# dsp_ice_rev1.net
KiCad netlist of a schematic drawn in EAGLE
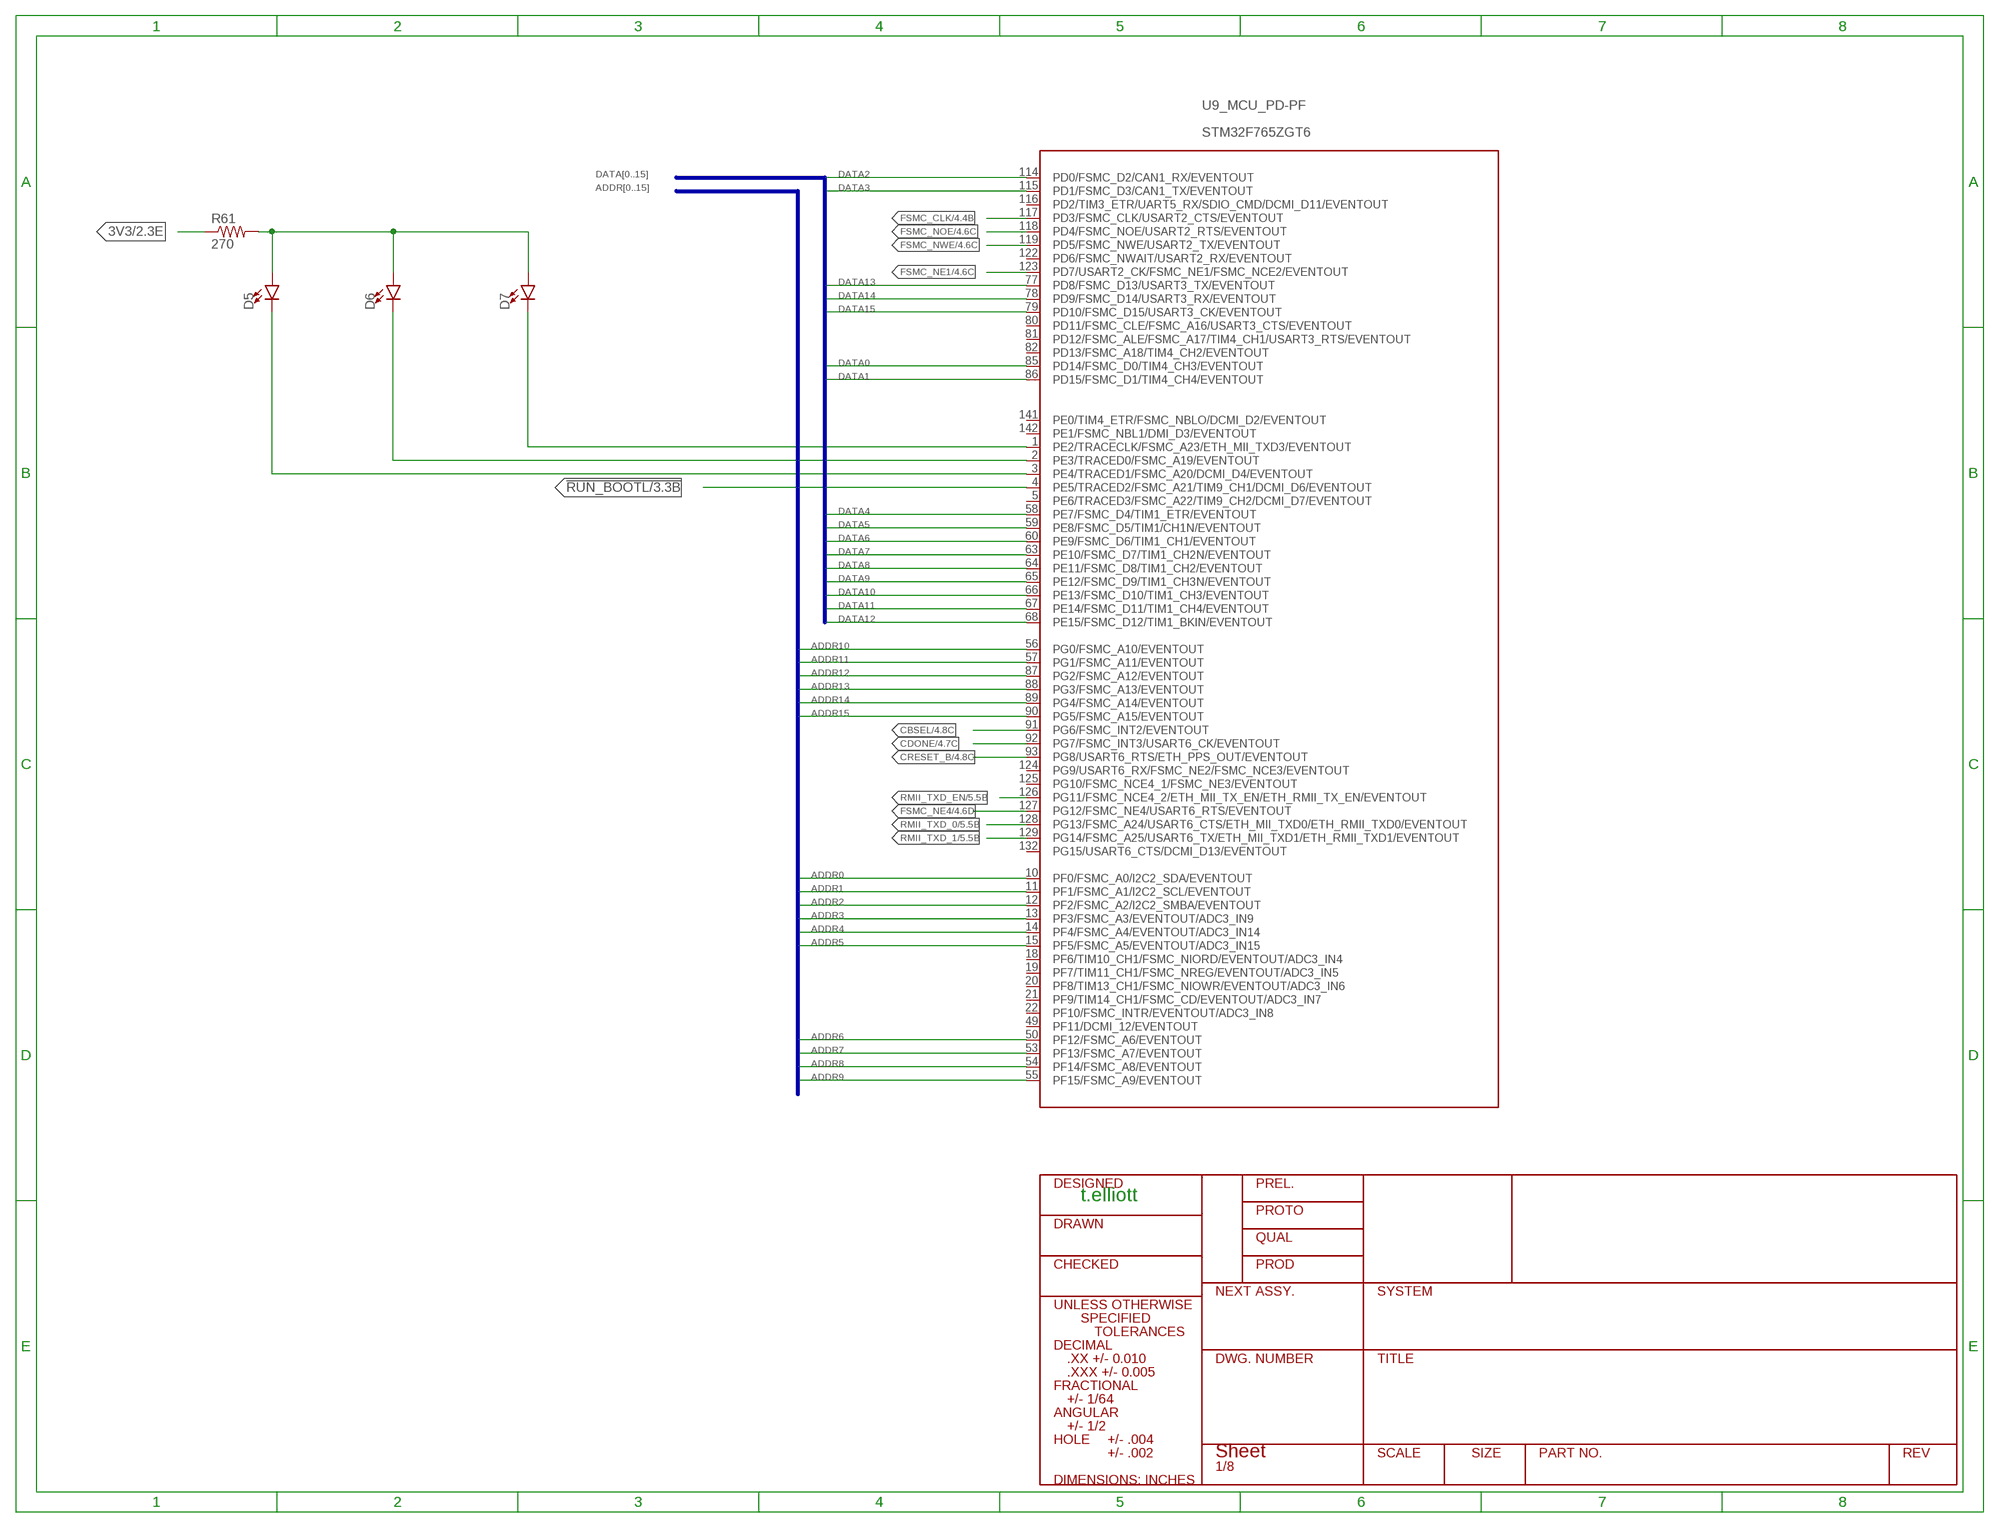
[diagram p0: schematic, sheet 1]
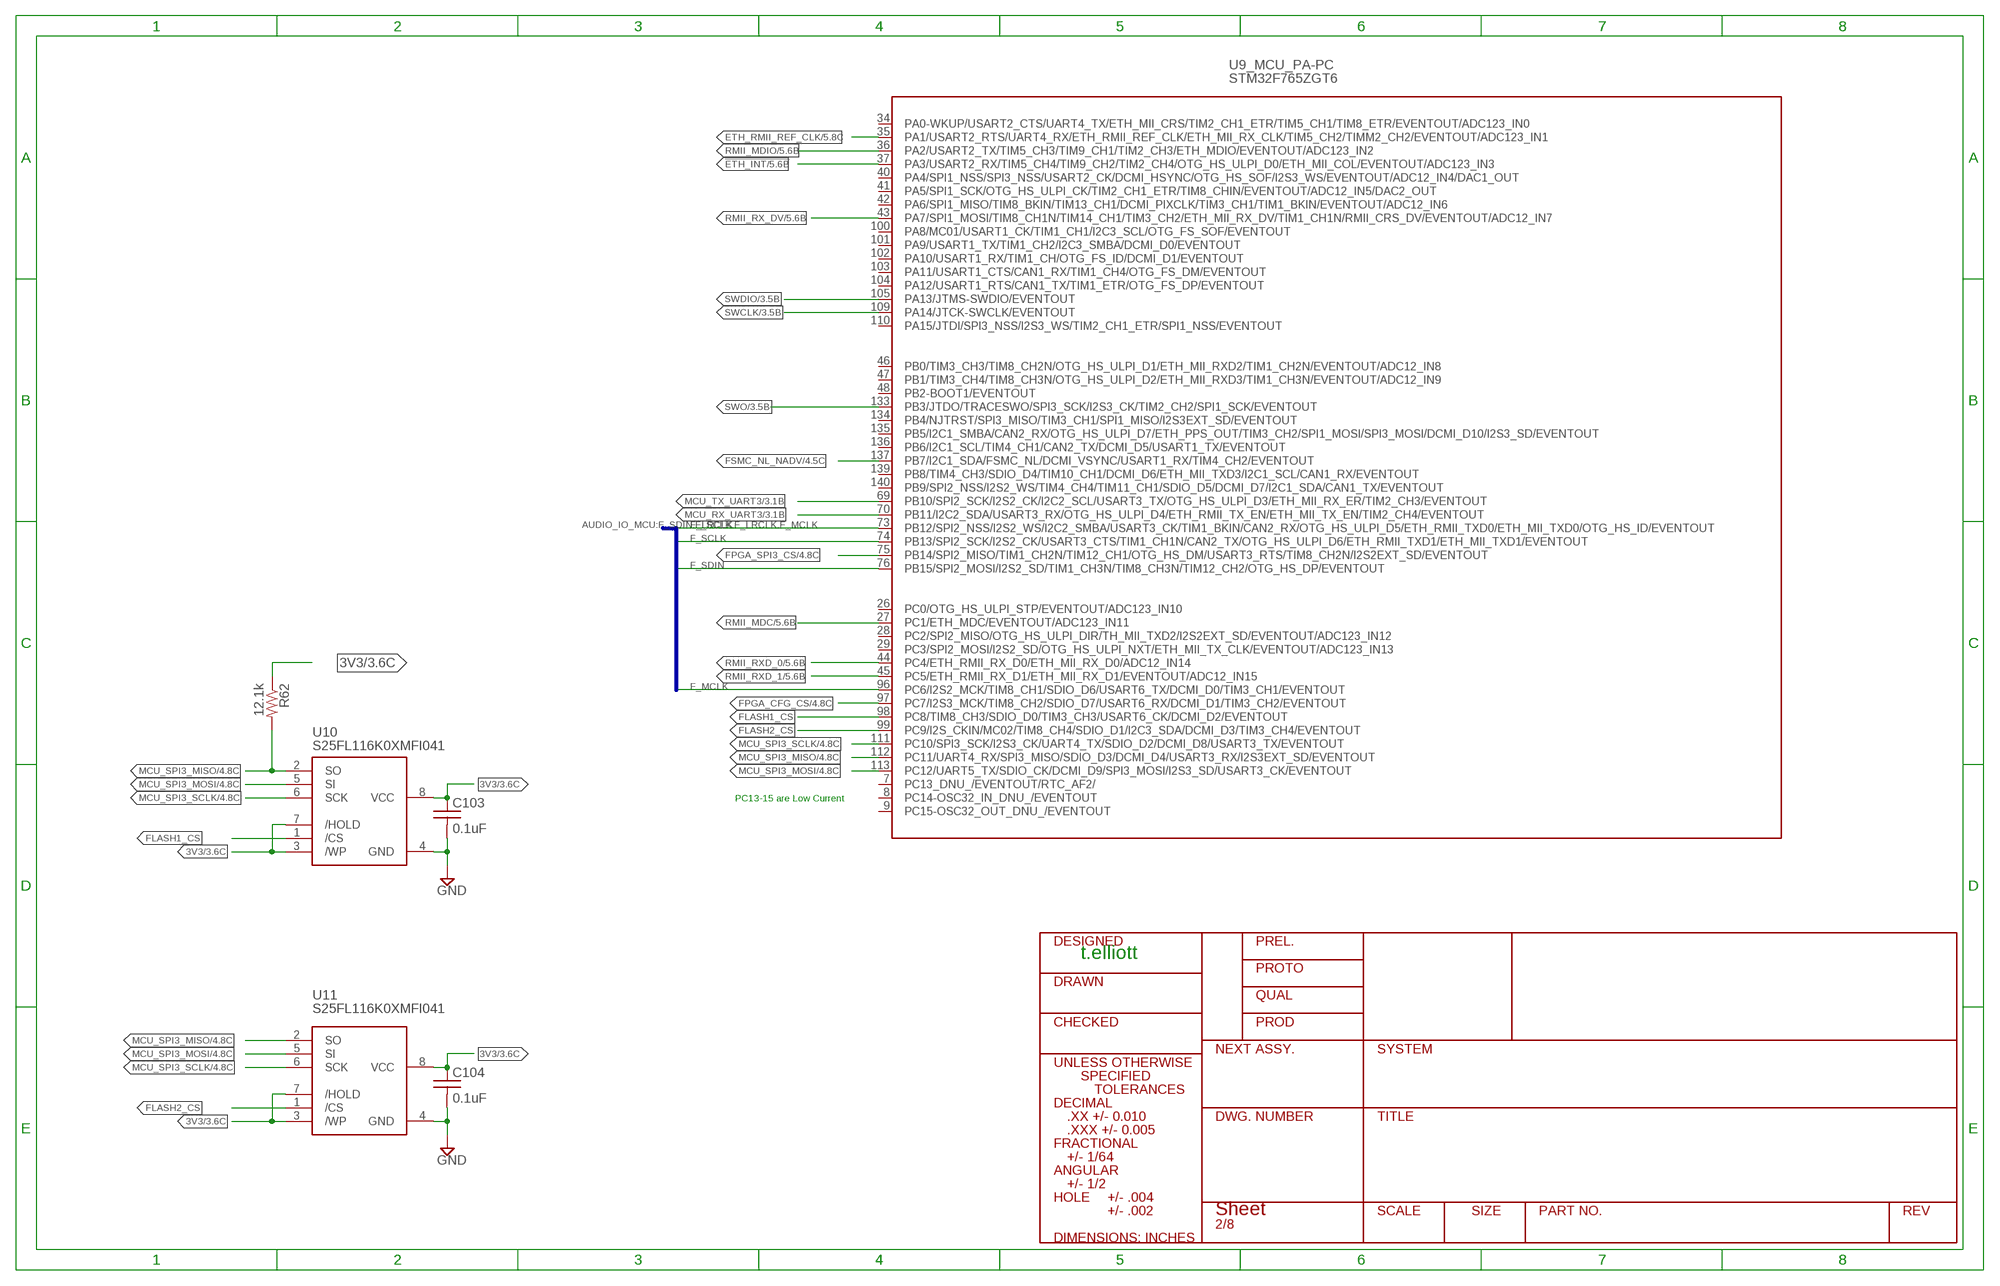
[diagram p1: schematic, sheet 2]
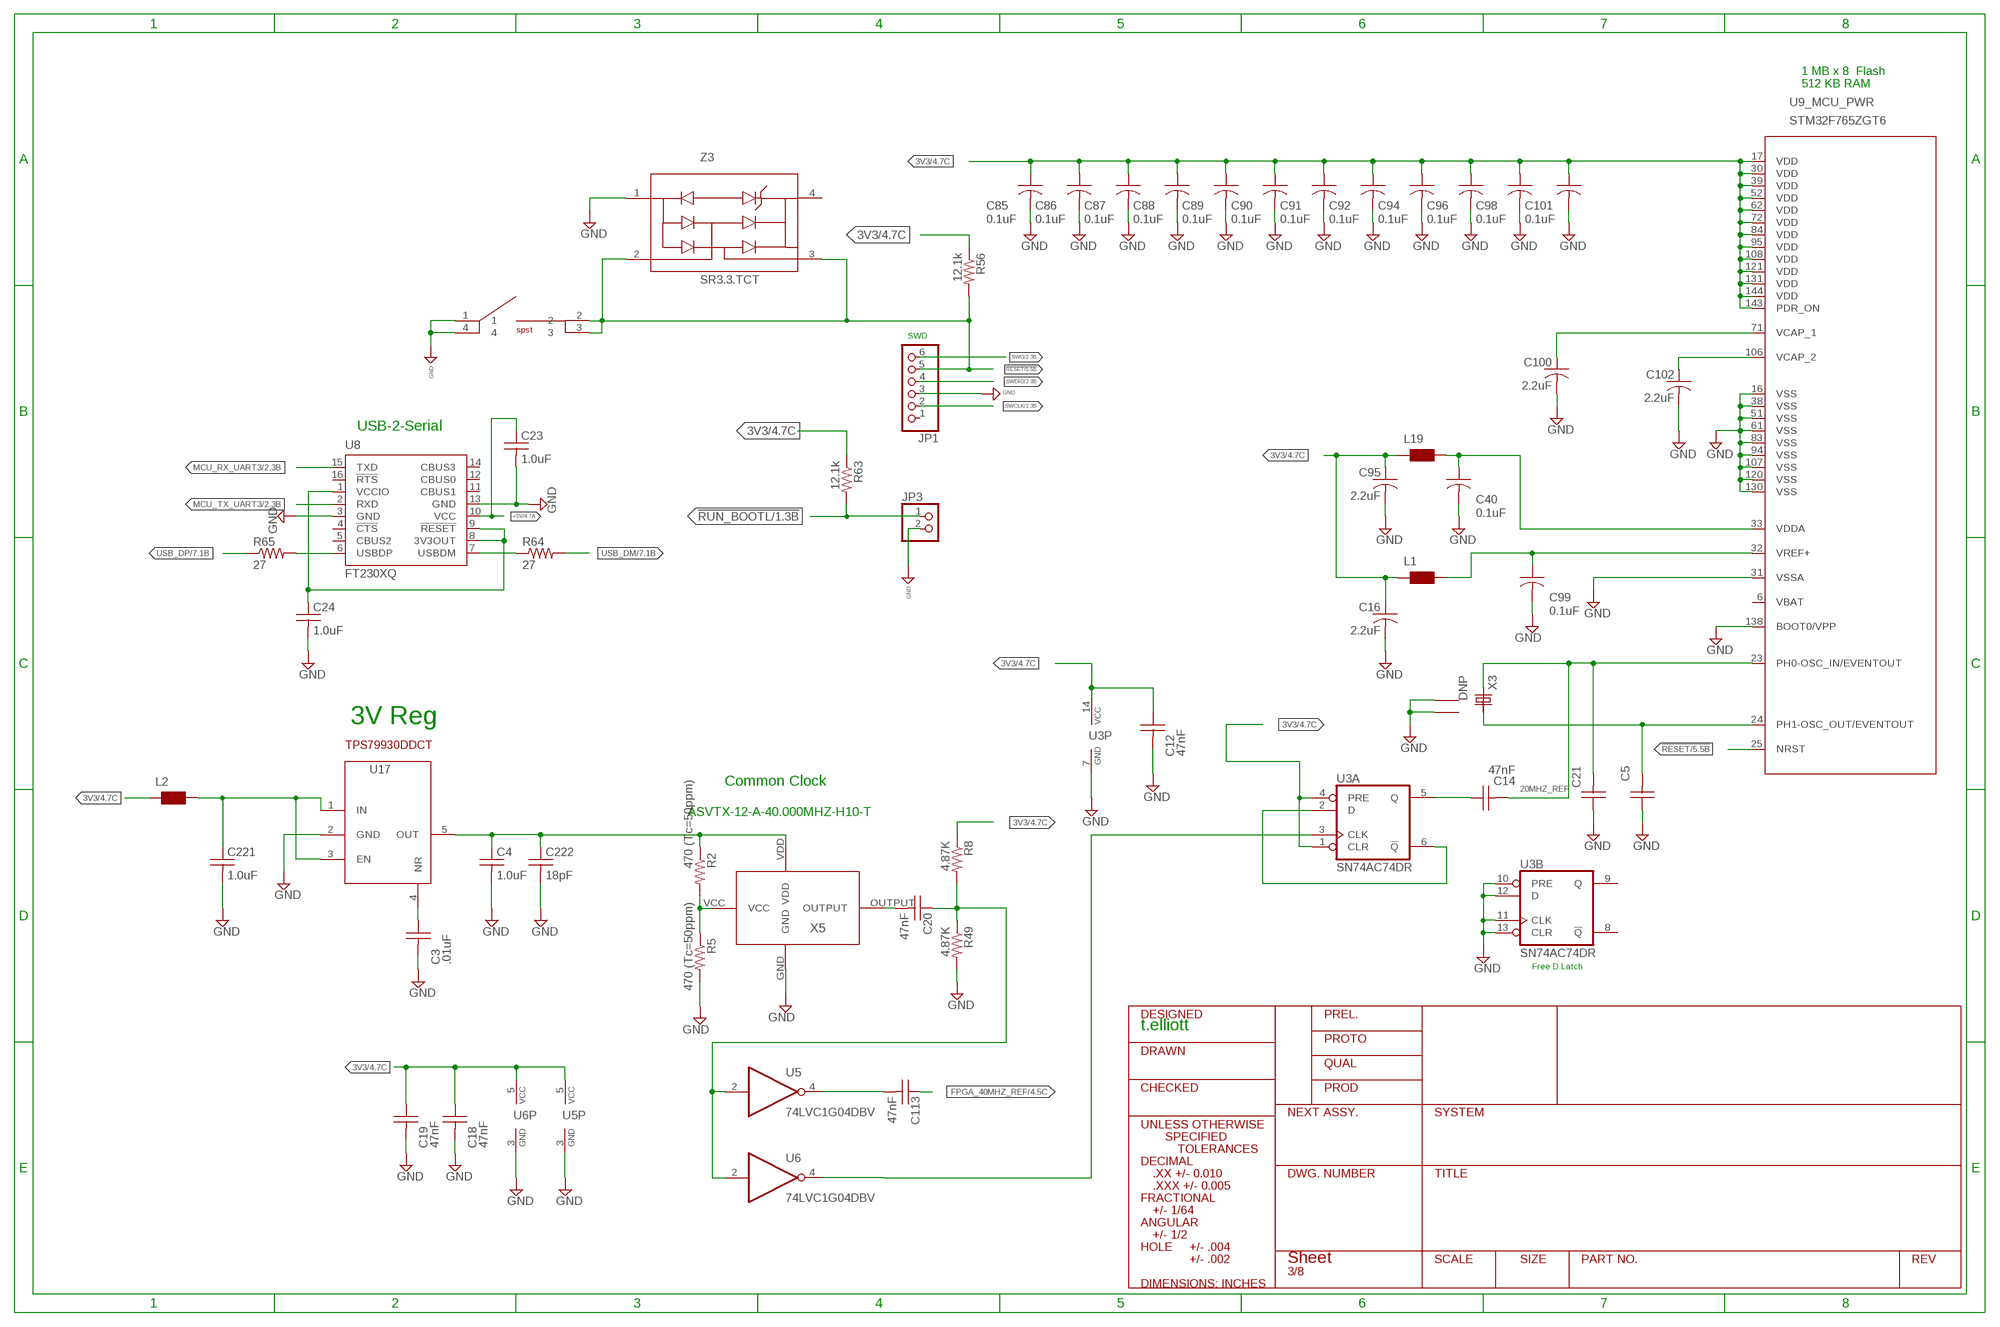
[diagram p2: schematic, sheet 3]
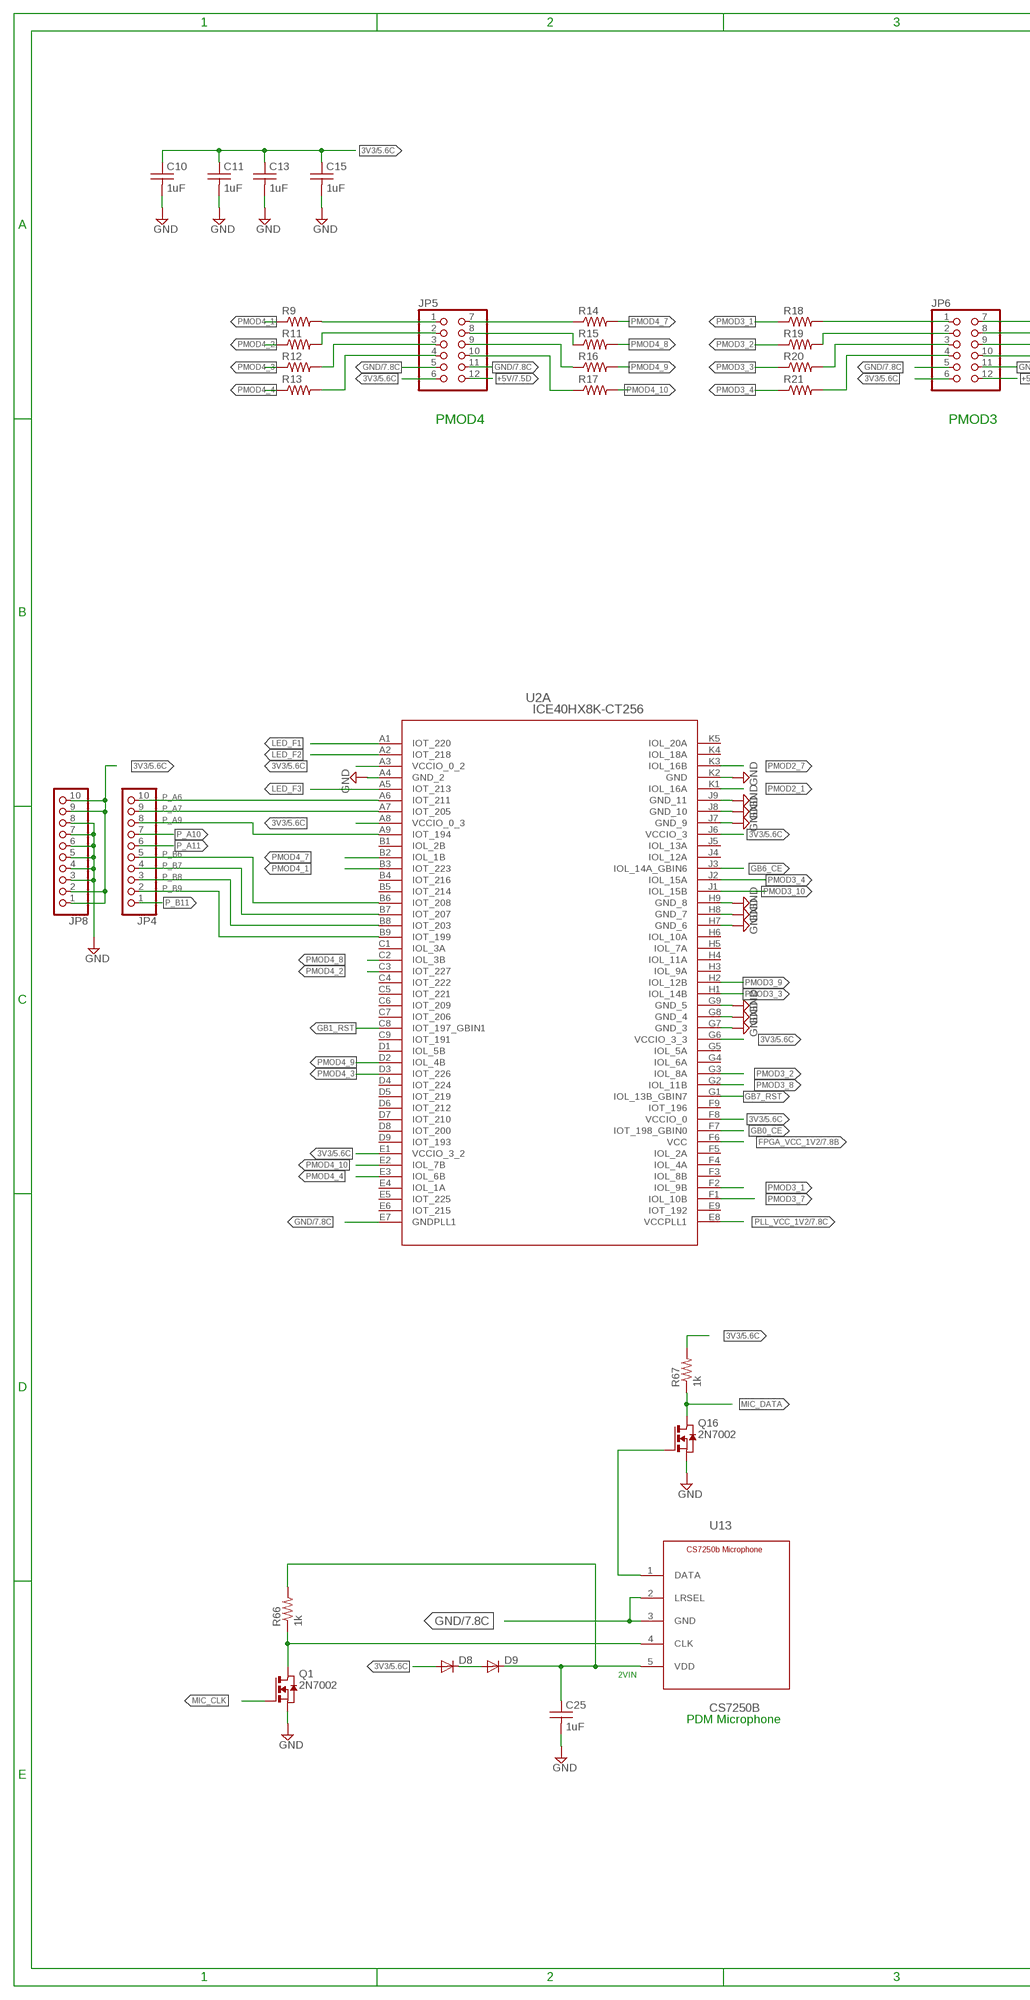
[diagram p3: schematic, sheet 4, part 1 of 2]
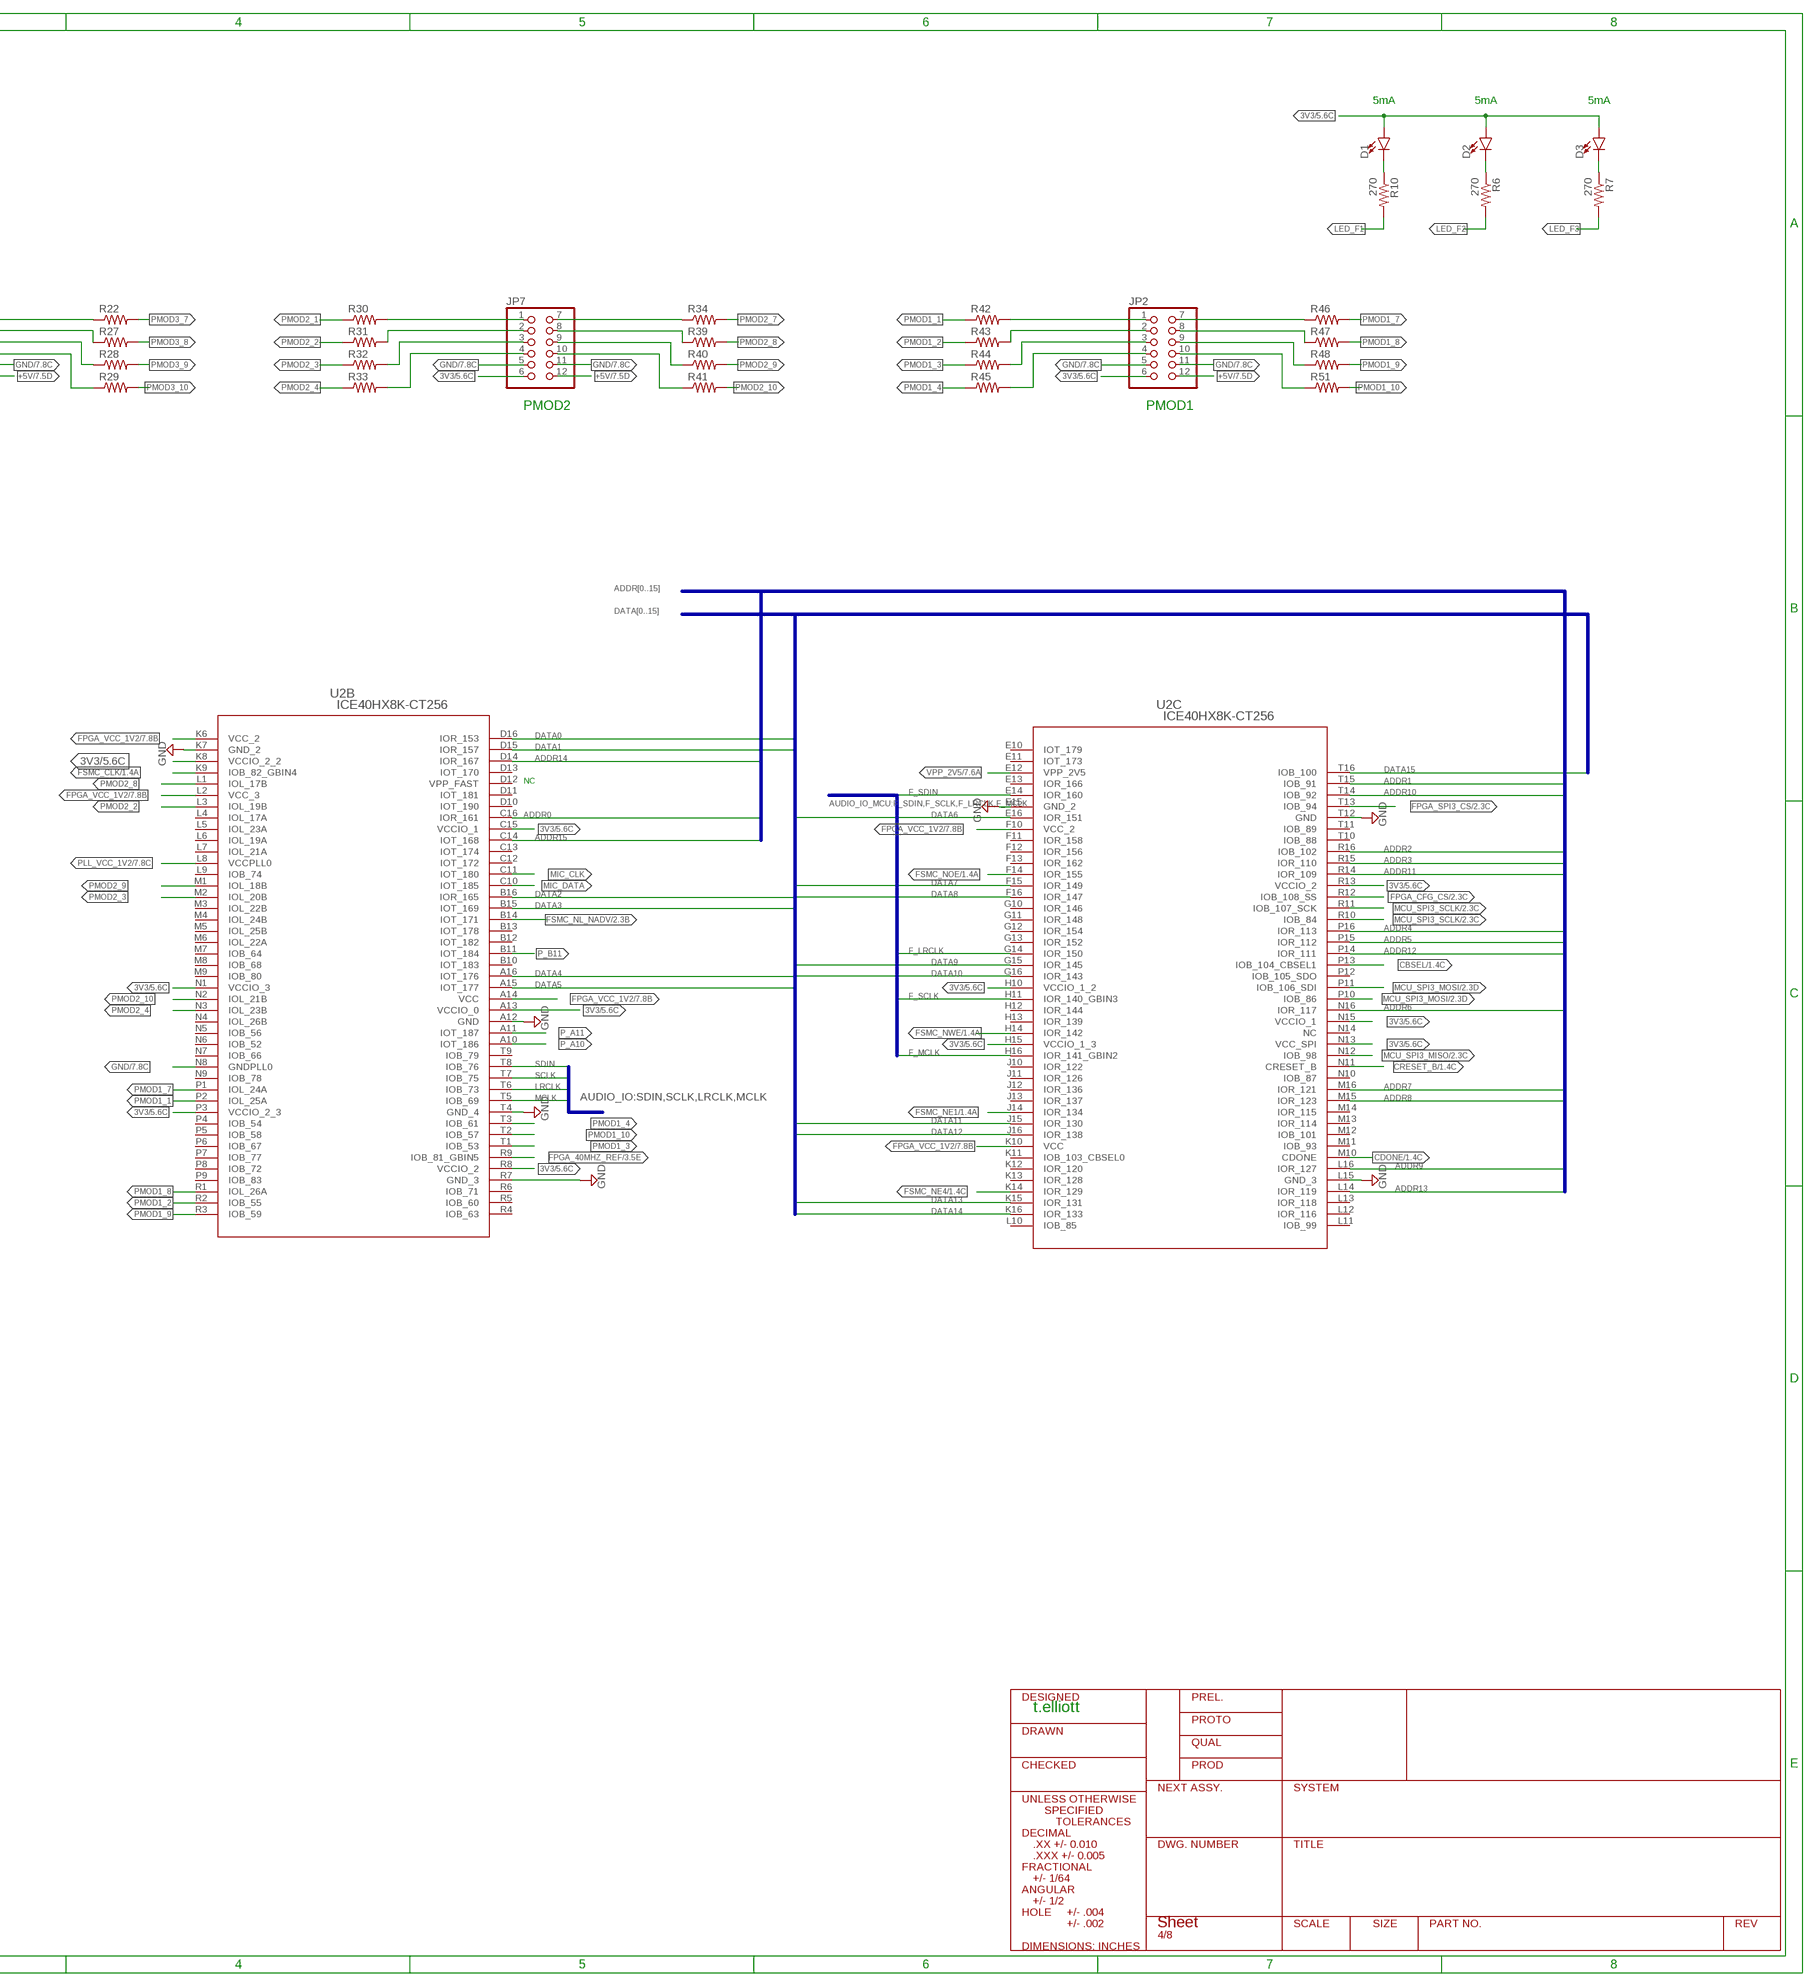
[diagram p4: schematic, sheet 4, part 2 of 2]
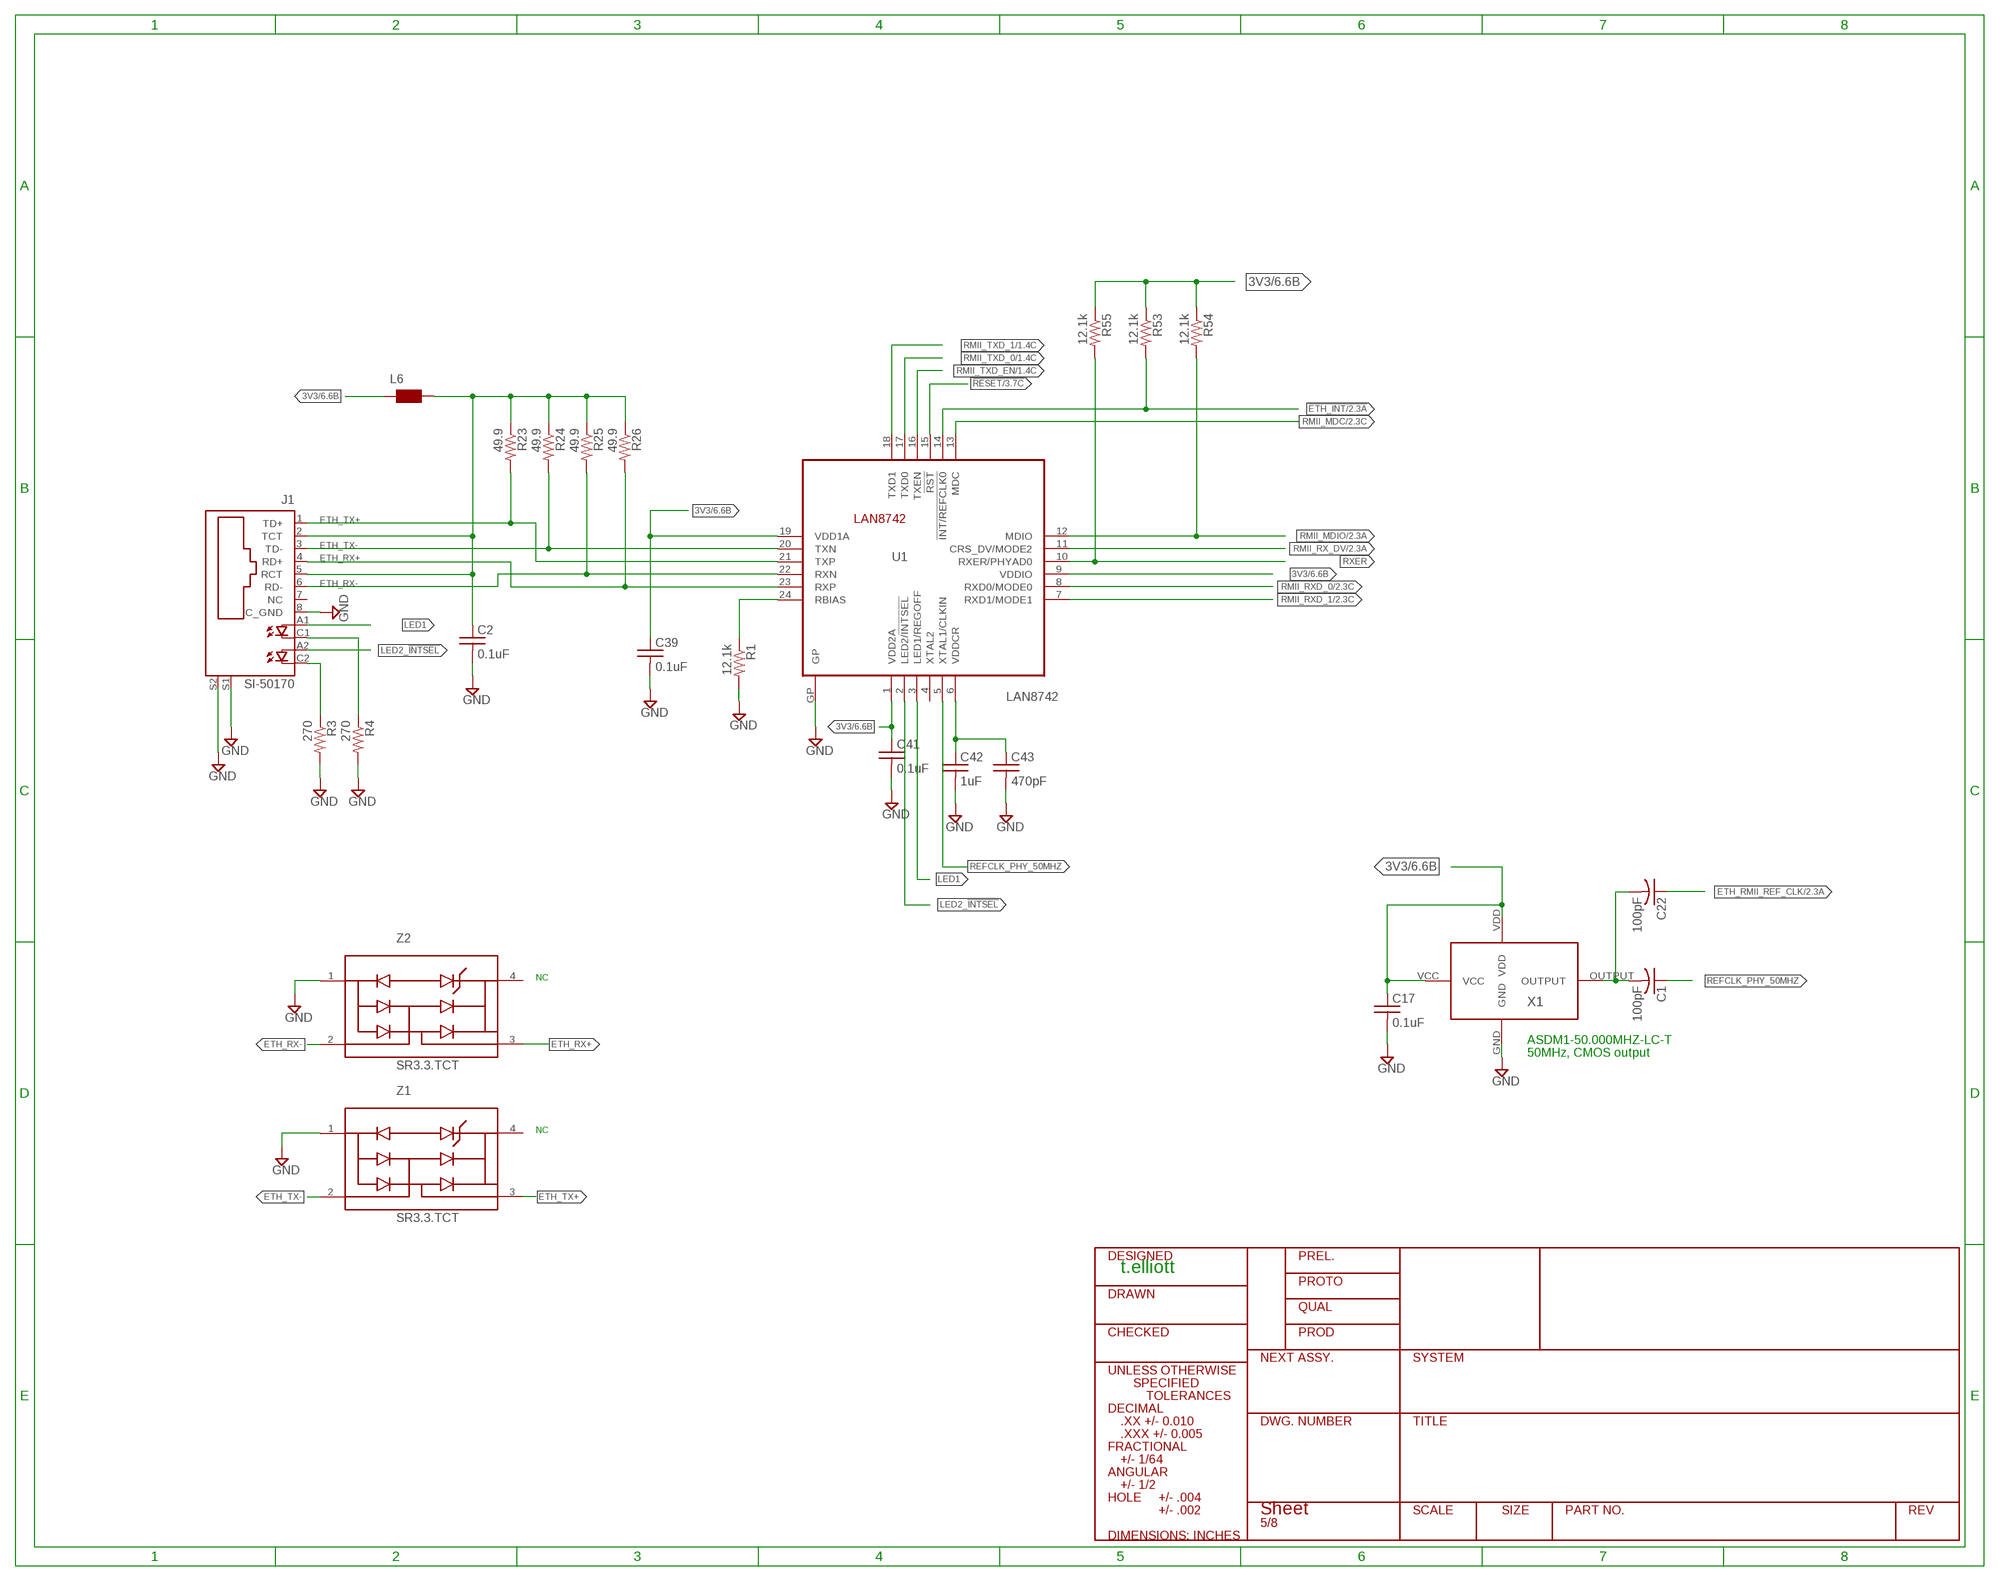
[diagram p5: schematic, sheet 5]
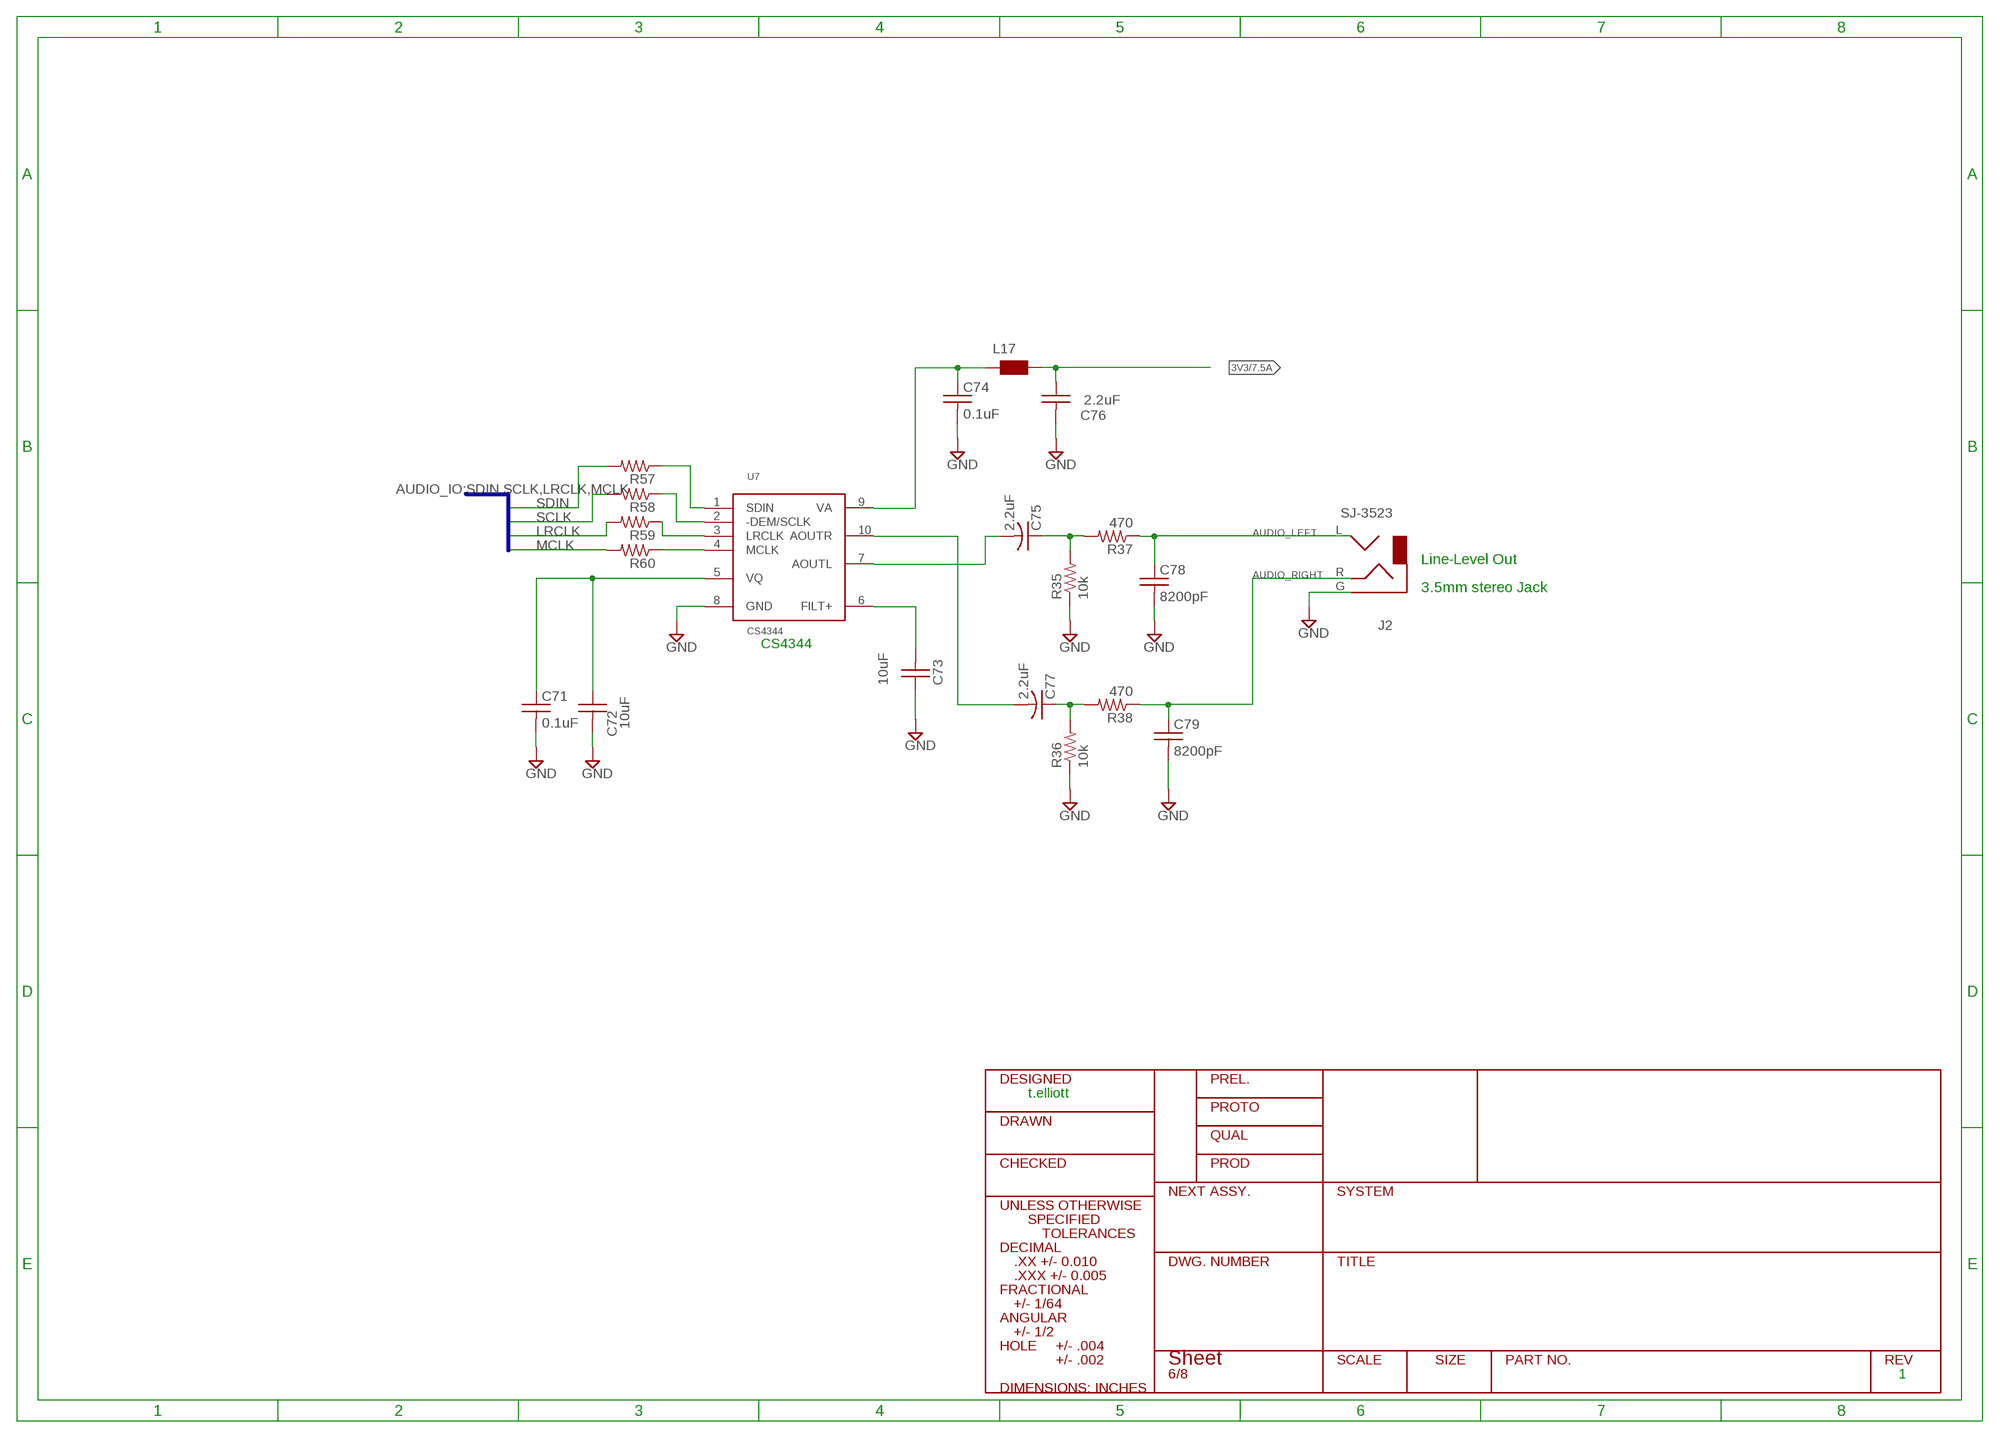
[diagram p6: schematic, sheet 6]
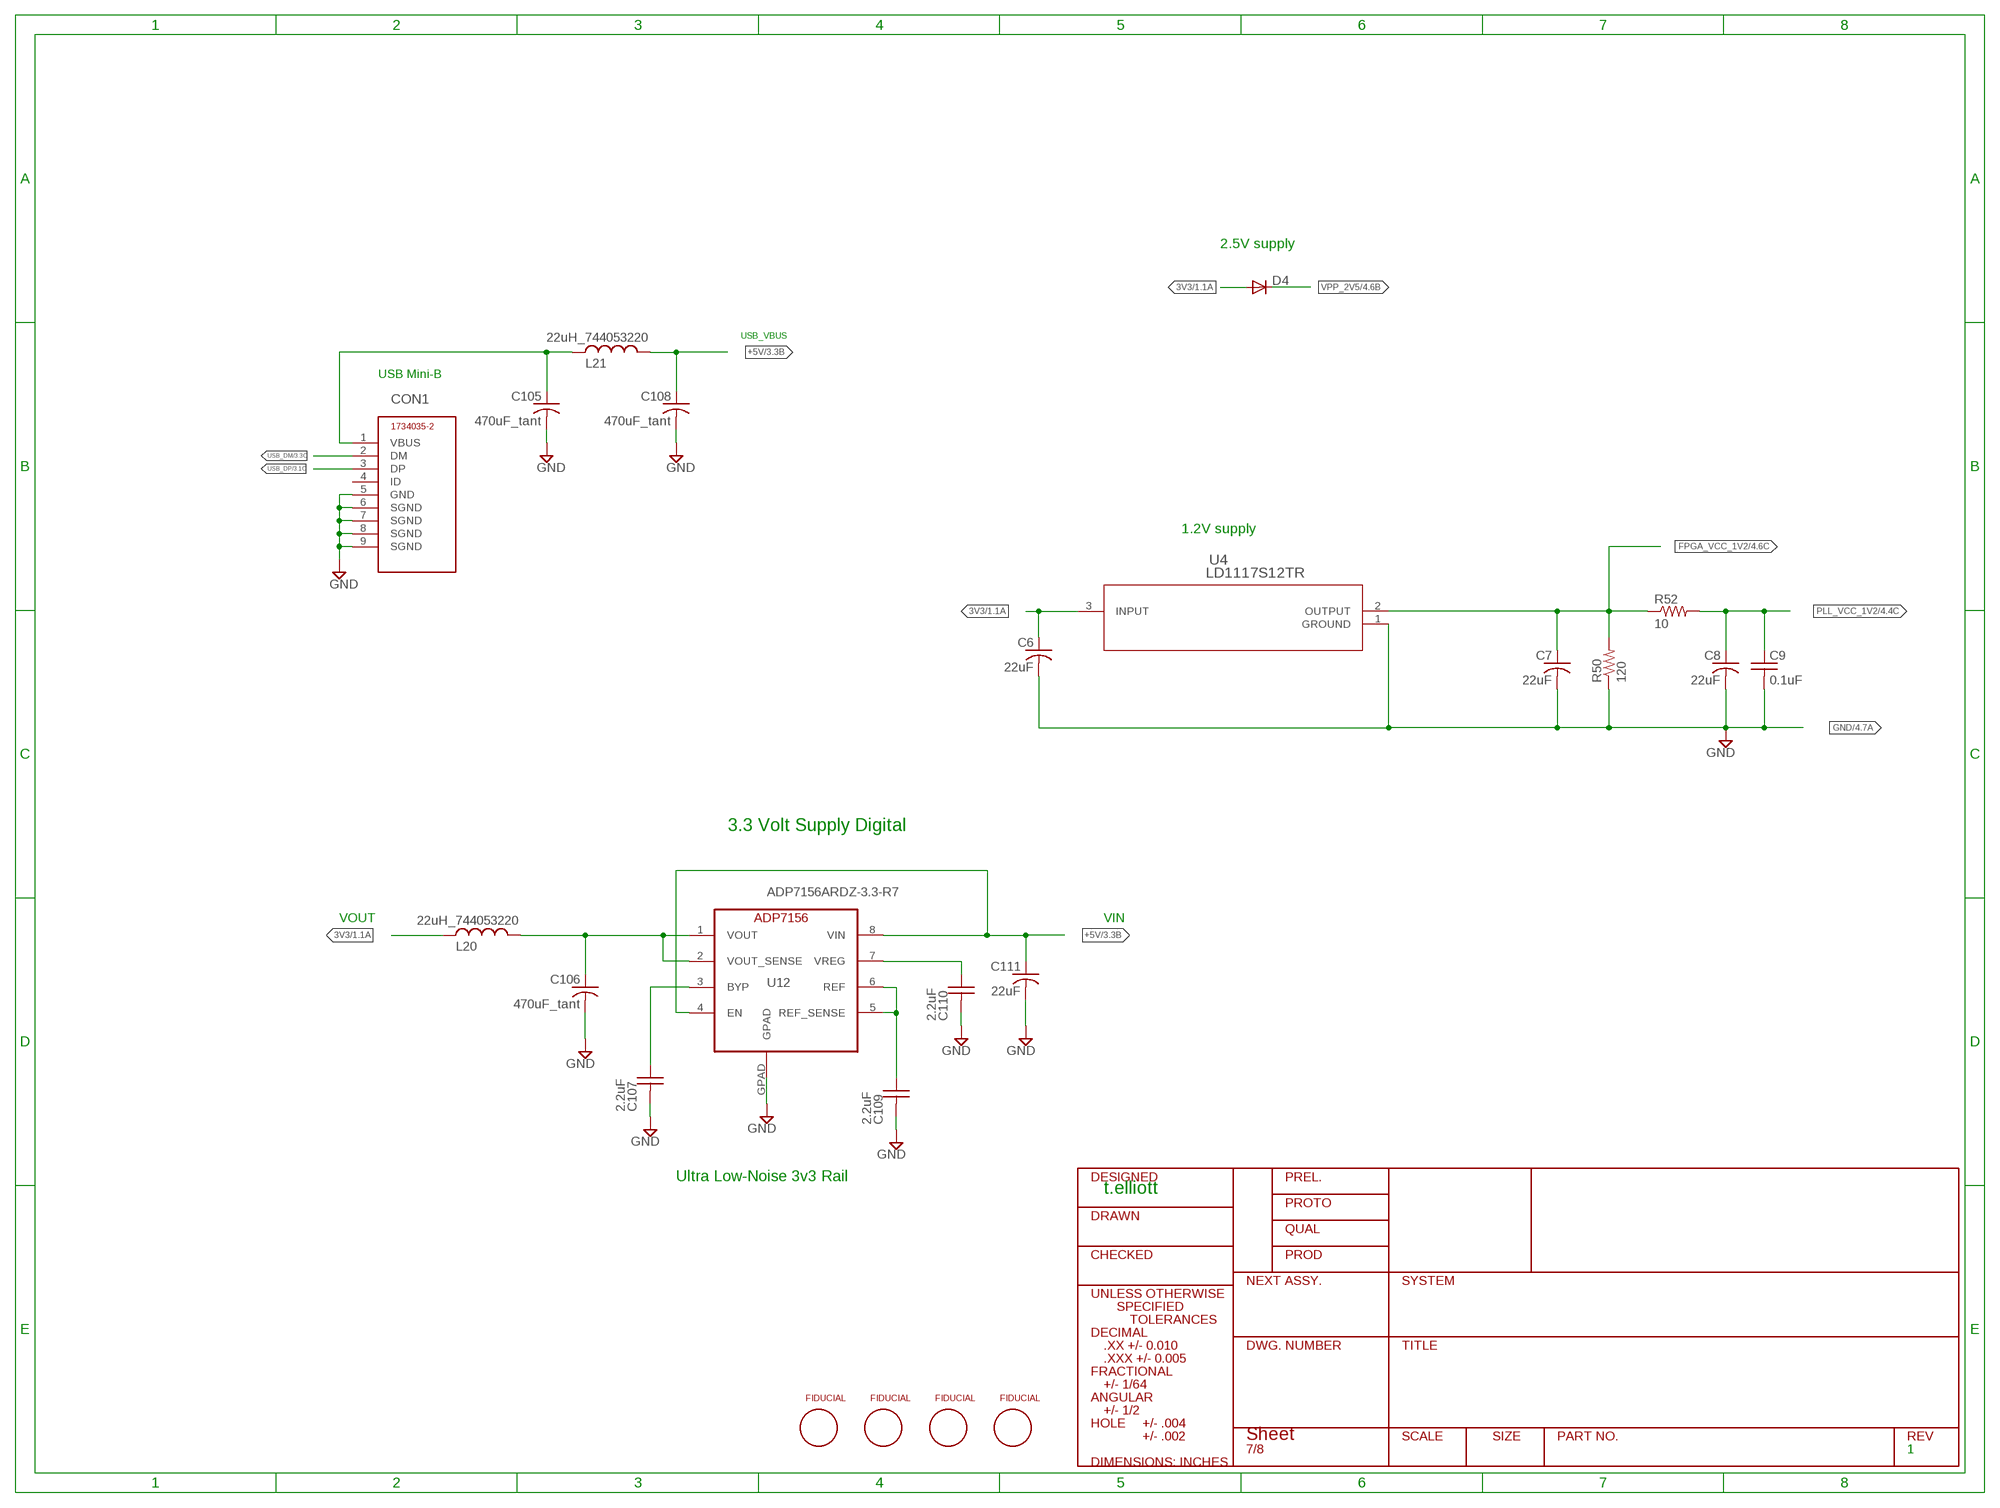
[diagram p7: schematic, sheet 7]
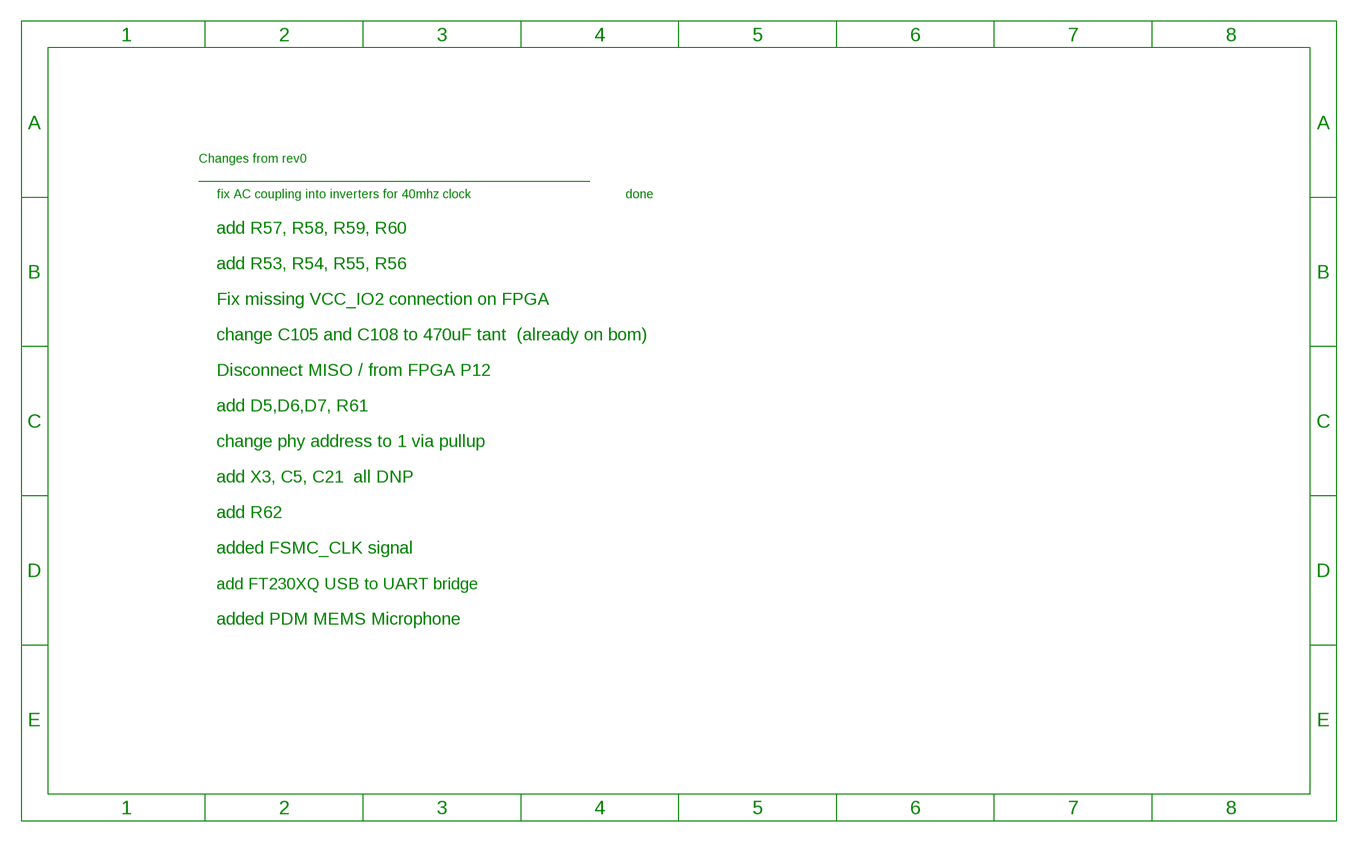
[diagram p8: schematic, sheet 8]

(export (version "E")
  (design (tool "Eeschema 10.0.6"))
  (components
    (comp (ref "C103")
      (value "0.1uF")
      (footprint "eagle-import:C0603")
      (libsource (lib "eagle-import") (part "misclib3_C-USC0603"))
    )
    (comp (ref "C104")
      (value "0.1uF")
      (footprint "eagle-import:C0603")
      (libsource (lib "eagle-import") (part "misclib3_C-USC0603"))
    )
    (comp (ref "R62")
      (value "12.1k")
      (footprint "eagle-import:R0603")
      (libsource (lib "eagle-import") (part "R-US_R0603"))
    )
    (comp (ref "U9")
      (value "STM32F765ZGT6")
      (footprint "eagle-import:STM32F407_144")
      (libsource (lib "eagle-import") (part "STM32F407_144_MG144"))
    )
    (comp (ref "U10")
      (value "S25FL116K0XMFI041")
      (footprint "eagle-import:SO8")
      (libsource (lib "eagle-import") (part "AT25F512ASOIC"))
    )
    (comp (ref "U11")
      (value "S25FL116K0XMFI041")
      (footprint "eagle-import:SO8")
      (libsource (lib "eagle-import") (part "AT25F512ASOIC"))
    )
    (comp (ref "C10")
      (value "1uF")
      (footprint "eagle-import:C0603")
      (libsource (lib "eagle-import") (part "C-USC0603"))
    )
    (comp (ref "C11")
      (value "1uF")
      (footprint "eagle-import:C0603")
      (libsource (lib "eagle-import") (part "C-USC0603"))
    )
    (comp (ref "C13")
      (value "1uF")
      (footprint "eagle-import:C0603")
      (libsource (lib "eagle-import") (part "C-USC0603"))
    )
    (comp (ref "C15")
      (value "1uF")
      (footprint "eagle-import:C0603")
      (libsource (lib "eagle-import") (part "C-USC0603"))
    )
    (comp (ref "C25")
      (value "1uF")
      (footprint "eagle-import:C0603")
      (libsource (lib "eagle-import") (part "C-USC0603"))
    )
    (comp (ref "D1")
      (value "LED1206")
      (footprint "eagle-import:LED-1206")
      (libsource (lib "eagle-import") (part "LED1206"))
    )
    (comp (ref "D2")
      (value "LED1206")
      (footprint "eagle-import:LED-1206")
      (libsource (lib "eagle-import") (part "LED1206"))
    )
    (comp (ref "D3")
      (value "LED1206")
      (footprint "eagle-import:LED-1206")
      (libsource (lib "eagle-import") (part "LED1206"))
    )
    (comp (ref "D8")
      (value "DIODE-MINIMELF")
      (footprint "eagle-import:MINIMELF")
      (libsource (lib "eagle-import") (part "DIODE-MINIMELF"))
    )
    (comp (ref "D9")
      (value "DIODE-MINIMELF")
      (footprint "eagle-import:MINIMELF")
      (libsource (lib "eagle-import") (part "DIODE-MINIMELF"))
    )
    (comp (ref "JP2")
      (value "PINHD-2X6")
      (footprint "eagle-import:2X06")
      (libsource (lib "eagle-import") (part "PINHD-2X6"))
    )
    (comp (ref "JP4")
      (value "PINHD-1X10")
      (footprint "eagle-import:1X10")
      (libsource (lib "eagle-import") (part "PINHD-1X10"))
    )
    (comp (ref "JP5")
      (value "PINHD-2X6")
      (footprint "eagle-import:2X06")
      (libsource (lib "eagle-import") (part "PINHD-2X6"))
    )
    (comp (ref "JP6")
      (value "PINHD-2X6")
      (footprint "eagle-import:2X06")
      (libsource (lib "eagle-import") (part "PINHD-2X6"))
    )
    (comp (ref "JP7")
      (value "PINHD-2X6")
      (footprint "eagle-import:2X06")
      (libsource (lib "eagle-import") (part "PINHD-2X6"))
    )
    (comp (ref "JP8")
      (value "PINHD-1X10")
      (footprint "eagle-import:1X10")
      (libsource (lib "eagle-import") (part "PINHD-1X10"))
    )
    (comp (ref "Q1")
      (value "2N7002")
      (footprint "eagle-import:SOT23_2N7002_PACKAGE")
      (libsource (lib "eagle-import") (part "2N7002"))
    )
    (comp (ref "Q16")
      (value "2N7002")
      (footprint "eagle-import:SOT23_2N7002_PACKAGE")
      (libsource (lib "eagle-import") (part "2N7002"))
    )
    (comp (ref "R6")
      (value "270")
      (footprint "eagle-import:R0603")
      (libsource (lib "eagle-import") (part "R-US_R0603"))
    )
    (comp (ref "R7")
      (value "270")
      (footprint "eagle-import:R0603")
      (libsource (lib "eagle-import") (part "R-US_R0603"))
    )
    (comp (ref "R9")
      (value "10")
      (footprint "eagle-import:R0603")
      (libsource (lib "eagle-import") (part "R-US_R0603"))
    )
    (comp (ref "R10")
      (value "270")
      (footprint "eagle-import:R0603")
      (libsource (lib "eagle-import") (part "R-US_R0603"))
    )
    (comp (ref "R11")
      (value "10")
      (footprint "eagle-import:R0603")
      (libsource (lib "eagle-import") (part "R-US_R0603"))
    )
    (comp (ref "R12")
      (value "10")
      (footprint "eagle-import:R0603")
      (libsource (lib "eagle-import") (part "R-US_R0603"))
    )
    (comp (ref "R13")
      (value "10")
      (footprint "eagle-import:R0603")
      (libsource (lib "eagle-import") (part "R-US_R0603"))
    )
    (comp (ref "R14")
      (value "10")
      (footprint "eagle-import:R0603")
      (libsource (lib "eagle-import") (part "R-US_R0603"))
    )
    (comp (ref "R15")
      (value "10")
      (footprint "eagle-import:R0603")
      (libsource (lib "eagle-import") (part "R-US_R0603"))
    )
    (comp (ref "R16")
      (value "10")
      (footprint "eagle-import:R0603")
      (libsource (lib "eagle-import") (part "R-US_R0603"))
    )
    (comp (ref "R17")
      (value "10")
      (footprint "eagle-import:R0603")
      (libsource (lib "eagle-import") (part "R-US_R0603"))
    )
    (comp (ref "R18")
      (value "10")
      (footprint "eagle-import:R0603")
      (libsource (lib "eagle-import") (part "R-US_R0603"))
    )
    (comp (ref "R19")
      (value "10")
      (footprint "eagle-import:R0603")
      (libsource (lib "eagle-import") (part "R-US_R0603"))
    )
    (comp (ref "R20")
      (value "10")
      (footprint "eagle-import:R0603")
      (libsource (lib "eagle-import") (part "R-US_R0603"))
    )
    (comp (ref "R21")
      (value "10")
      (footprint "eagle-import:R0603")
      (libsource (lib "eagle-import") (part "R-US_R0603"))
    )
    (comp (ref "R22")
      (value "10")
      (footprint "eagle-import:R0603")
      (libsource (lib "eagle-import") (part "R-US_R0603"))
    )
    (comp (ref "R27")
      (value "10")
      (footprint "eagle-import:R0603")
      (libsource (lib "eagle-import") (part "R-US_R0603"))
    )
    (comp (ref "R28")
      (value "10")
      (footprint "eagle-import:R0603")
      (libsource (lib "eagle-import") (part "R-US_R0603"))
    )
    (comp (ref "R29")
      (value "10")
      (footprint "eagle-import:R0603")
      (libsource (lib "eagle-import") (part "R-US_R0603"))
    )
    (comp (ref "R30")
      (value "10")
      (footprint "eagle-import:R0603")
      (libsource (lib "eagle-import") (part "R-US_R0603"))
    )
    (comp (ref "R31")
      (value "10")
      (footprint "eagle-import:R0603")
      (libsource (lib "eagle-import") (part "R-US_R0603"))
    )
    (comp (ref "R32")
      (value "10")
      (footprint "eagle-import:R0603")
      (libsource (lib "eagle-import") (part "R-US_R0603"))
    )
    (comp (ref "R33")
      (value "10")
      (footprint "eagle-import:R0603")
      (libsource (lib "eagle-import") (part "R-US_R0603"))
    )
    (comp (ref "R34")
      (value "10")
      (footprint "eagle-import:R0603")
      (libsource (lib "eagle-import") (part "R-US_R0603"))
    )
    (comp (ref "R39")
      (value "10")
      (footprint "eagle-import:R0603")
      (libsource (lib "eagle-import") (part "R-US_R0603"))
    )
    (comp (ref "R40")
      (value "10")
      (footprint "eagle-import:R0603")
      (libsource (lib "eagle-import") (part "R-US_R0603"))
    )
    (comp (ref "R41")
      (value "10")
      (footprint "eagle-import:R0603")
      (libsource (lib "eagle-import") (part "R-US_R0603"))
    )
    (comp (ref "R42")
      (value "10")
      (footprint "eagle-import:R0603")
      (libsource (lib "eagle-import") (part "R-US_R0603"))
    )
    (comp (ref "R43")
      (value "10")
      (footprint "eagle-import:R0603")
      (libsource (lib "eagle-import") (part "R-US_R0603"))
    )
    (comp (ref "R44")
      (value "10")
      (footprint "eagle-import:R0603")
      (libsource (lib "eagle-import") (part "R-US_R0603"))
    )
    (comp (ref "R45")
      (value "10")
      (footprint "eagle-import:R0603")
      (libsource (lib "eagle-import") (part "R-US_R0603"))
    )
    (comp (ref "R46")
      (value "10")
      (footprint "eagle-import:R0603")
      (libsource (lib "eagle-import") (part "R-US_R0603"))
    )
    (comp (ref "R47")
      (value "10")
      (footprint "eagle-import:R0603")
      (libsource (lib "eagle-import") (part "R-US_R0603"))
    )
    (comp (ref "R48")
      (value "10")
      (footprint "eagle-import:R0603")
      (libsource (lib "eagle-import") (part "R-US_R0603"))
    )
    (comp (ref "R51")
      (value "10")
      (footprint "eagle-import:R0603")
      (libsource (lib "eagle-import") (part "R-US_R0603"))
    )
    (comp (ref "R66")
      (value "1k")
      (footprint "eagle-import:R0603")
      (libsource (lib "eagle-import") (part "R-US_R0603"))
    )
    (comp (ref "R67")
      (value "1k")
      (footprint "eagle-import:R0603")
      (libsource (lib "eagle-import") (part "R-US_R0603"))
    )
    (comp (ref "U2")
      (value "ICE40HX8K-CT256")
      (footprint "eagle-import:CABGA256")
      (fields (field (name "MANUFACTURER_PART_NUMBER") "ICE40HX8KCT256"))
      (libsource (lib "eagle-import") (part "ICE40HX8K-CT256"))
    )
    (comp (ref "U13")
      (value "CS7250B")
      (footprint "eagle-import:CS7250B-CAZR")
      (libsource (lib "eagle-import") (part "CS7250B"))
    )
    (comp (ref "D5")
      (value "LED1206")
      (footprint "eagle-import:LED-1206")
      (libsource (lib "eagle-import") (part "LED1206"))
    )
    (comp (ref "D6")
      (value "LED1206")
      (footprint "eagle-import:LED-1206")
      (libsource (lib "eagle-import") (part "LED1206"))
    )
    (comp (ref "D7")
      (value "LED1206")
      (footprint "eagle-import:LED-1206")
      (libsource (lib "eagle-import") (part "LED1206"))
    )
    (comp (ref "R61")
      (value "270")
      (footprint "eagle-import:R0603")
      (libsource (lib "eagle-import") (part "R-US_R0603"))
    )
    (comp (ref "C71")
      (value "0.1uF")
      (footprint "eagle-import:C0603")
      (libsource (lib "eagle-import") (part "misclib3_C-USC0603"))
    )
    (comp (ref "C72")
      (value "10uF")
      (footprint "eagle-import:C0805")
      (libsource (lib "eagle-import") (part "misclib3_C-USC0805"))
    )
    (comp (ref "C73")
      (value "10uF")
      (footprint "eagle-import:C0805")
      (libsource (lib "eagle-import") (part "misclib3_C-USC0805"))
    )
    (comp (ref "C74")
      (value "0.1uF")
      (footprint "eagle-import:C0603")
      (libsource (lib "eagle-import") (part "misclib3_C-USC0603"))
    )
    (comp (ref "C75")
      (value "2.2uF")
      (footprint "eagle-import:C0805")
      (libsource (lib "eagle-import") (part "resistor_C-USC0805"))
    )
    (comp (ref "C76")
      (value "2.2uF")
      (footprint "eagle-import:C0805")
      (libsource (lib "eagle-import") (part "misclib3_C-USC0805"))
    )
    (comp (ref "C77")
      (value "2.2uF")
      (footprint "eagle-import:C0805")
      (libsource (lib "eagle-import") (part "resistor_C-USC0805"))
    )
    (comp (ref "C78")
      (value "8200pF")
      (footprint "eagle-import:C0603")
      (libsource (lib "eagle-import") (part "misclib3_C-USC0603"))
    )
    (comp (ref "C79")
      (value "8200pF")
      (footprint "eagle-import:C0603")
      (libsource (lib "eagle-import") (part "misclib3_C-USC0603"))
    )
    (comp (ref "J2")
      (value "SJ-3523")
      (footprint "eagle-import:SJ-3523")
      (libsource (lib "eagle-import") (part "CUI_SJ-3523SMT"))
    )
    (comp (ref "L17")
      (value "WE-CBF_0603")
      (footprint "eagle-import:0603")
      (libsource (lib "eagle-import") (part "WE-CBF_0603"))
    )
    (comp (ref "R35")
      (value "10k")
      (footprint "eagle-import:R0402")
      (libsource (lib "eagle-import") (part "misclib3_R-US_R0402"))
    )
    (comp (ref "R36")
      (value "10k")
      (footprint "eagle-import:R0402")
      (libsource (lib "eagle-import") (part "misclib3_R-US_R0402"))
    )
    (comp (ref "R37")
      (value "470")
      (footprint "eagle-import:R0402")
      (libsource (lib "eagle-import") (part "misclib3_R-US_R0402"))
    )
    (comp (ref "R38")
      (value "470")
      (footprint "eagle-import:R0402")
      (libsource (lib "eagle-import") (part "misclib3_R-US_R0402"))
    )
    (comp (ref "R57")
      (value "470")
      (footprint "eagle-import:R0402")
      (libsource (lib "eagle-import") (part "misclib3_R-US_R0402"))
    )
    (comp (ref "R58")
      (value "470")
      (footprint "eagle-import:R0402")
      (libsource (lib "eagle-import") (part "misclib3_R-US_R0402"))
    )
    (comp (ref "R59")
      (value "470")
      (footprint "eagle-import:R0402")
      (libsource (lib "eagle-import") (part "misclib3_R-US_R0402"))
    )
    (comp (ref "R60")
      (value "470")
      (footprint "eagle-import:R0402")
      (libsource (lib "eagle-import") (part "misclib3_R-US_R0402"))
    )
    (comp (ref "U7")
      (value "CS4344")
      (footprint "eagle-import:MSOP10")
      (libsource (lib "eagle-import") (part "CS4344"))
    )
    (comp (ref "C1")
      (value "100pF")
      (footprint "eagle-import:C0603")
      (libsource (lib "eagle-import") (part "rcl_C-USC0603"))
    )
    (comp (ref "C2")
      (value "0.1uF")
      (footprint "eagle-import:C0603")
      (libsource (lib "eagle-import") (part "C-USC0603"))
    )
    (comp (ref "C17")
      (value "0.1uF")
      (footprint "eagle-import:C0603")
      (libsource (lib "eagle-import") (part "C-USC0603"))
    )
    (comp (ref "C22")
      (value "100pF")
      (footprint "eagle-import:C0603")
      (libsource (lib "eagle-import") (part "rcl_C-USC0603"))
    )
    (comp (ref "C39")
      (value "0.1uF")
      (footprint "eagle-import:C0603")
      (libsource (lib "eagle-import") (part "C-USC0603"))
    )
    (comp (ref "C41")
      (value "0.1uF")
      (footprint "eagle-import:C0603")
      (libsource (lib "eagle-import") (part "C-USC0603"))
    )
    (comp (ref "C42")
      (value "1uF")
      (footprint "eagle-import:C0603")
      (libsource (lib "eagle-import") (part "C-USC0603"))
    )
    (comp (ref "C43")
      (value "470pF")
      (footprint "eagle-import:C0603")
      (libsource (lib "eagle-import") (part "C-USC0603"))
    )
    (comp (ref "J1")
      (value "SI-50170")
      (footprint "eagle-import:SI-50170")
      (libsource (lib "eagle-import") (part "SI-50170"))
    )
    (comp (ref "L6")
      (value "WE-CBF_0603")
      (footprint "eagle-import:0603")
      (libsource (lib "eagle-import") (part "WE-CBF_0603"))
    )
    (comp (ref "R1")
      (value "12.1k")
      (footprint "eagle-import:R0603")
      (libsource (lib "eagle-import") (part "R-US_R0603"))
    )
    (comp (ref "R3")
      (value "270")
      (footprint "eagle-import:R0603")
      (libsource (lib "eagle-import") (part "R-US_R0603"))
    )
    (comp (ref "R4")
      (value "270")
      (footprint "eagle-import:R0603")
      (libsource (lib "eagle-import") (part "R-US_R0603"))
    )
    (comp (ref "R23")
      (value "49.9")
      (footprint "eagle-import:R0603")
      (libsource (lib "eagle-import") (part "R-US_R0603"))
    )
    (comp (ref "R24")
      (value "49.9")
      (footprint "eagle-import:R0603")
      (libsource (lib "eagle-import") (part "R-US_R0603"))
    )
    (comp (ref "R25")
      (value "49.9")
      (footprint "eagle-import:R0603")
      (libsource (lib "eagle-import") (part "R-US_R0603"))
    )
    (comp (ref "R26")
      (value "49.9")
      (footprint "eagle-import:R0603")
      (libsource (lib "eagle-import") (part "R-US_R0603"))
    )
    (comp (ref "R53")
      (value "12.1k")
      (footprint "eagle-import:R0603")
      (libsource (lib "eagle-import") (part "R-US_R0603"))
    )
    (comp (ref "R54")
      (value "12.1k")
      (footprint "eagle-import:R0603")
      (libsource (lib "eagle-import") (part "R-US_R0603"))
    )
    (comp (ref "R55")
      (value "12.1k")
      (footprint "eagle-import:R0603")
      (libsource (lib "eagle-import") (part "R-US_R0603"))
    )
    (comp (ref "U1")
      (value "LAN8742")
      (footprint "eagle-import:QFN-24")
      (libsource (lib "eagle-import") (part "LAN8742"))
    )
    (comp (ref "X1")
      (value "ASDM1-50.000MHZ-LC-T")
      (footprint "eagle-import:CRYSTAL_2.5_2MM")
      (libsource (lib "eagle-import") (part "CRYSTAL40MHZ2.5_2MM"))
    )
    (comp (ref "Z1")
      (value "SR3.3.TCT")
      (footprint "eagle-import:SR2.8.TCT_1PRIMARY")
      (libsource (lib "eagle-import") (part "SR2.8_TVS"))
    )
    (comp (ref "Z2")
      (value "SR3.3.TCT")
      (footprint "eagle-import:SR2.8.TCT_1PRIMARY")
      (libsource (lib "eagle-import") (part "SR2.8_TVS"))
    )
    (comp (ref "C6")
      (value "22uF")
      (footprint "eagle-import:1210K")
      (libsource (lib "eagle-import") (part "CAPACITOR1210K"))
    )
    (comp (ref "C7")
      (value "22uF")
      (footprint "eagle-import:1210K")
      (libsource (lib "eagle-import") (part "CAPACITOR1210K"))
    )
    (comp (ref "C8")
      (value "22uF")
      (footprint "eagle-import:1210K")
      (libsource (lib "eagle-import") (part "CAPACITOR1210K"))
    )
    (comp (ref "C9")
      (value "0.1uF")
      (footprint "eagle-import:C0603")
      (libsource (lib "eagle-import") (part "misclib3_C-USC0603"))
    )
    (comp (ref "C105")
      (value "470uF_tant")
      (footprint "eagle-import:1210K")
      (libsource (lib "eagle-import") (part "CAPACITOR1210K"))
    )
    (comp (ref "C106")
      (value "470uF_tant")
      (footprint "eagle-import:1210K")
      (libsource (lib "eagle-import") (part "CAPACITOR1210K"))
    )
    (comp (ref "C107")
      (value "2.2uF")
      (footprint "eagle-import:C0805")
      (libsource (lib "eagle-import") (part "misclib3_C-USC0805"))
    )
    (comp (ref "C108")
      (value "470uF_tant")
      (footprint "eagle-import:1210K")
      (libsource (lib "eagle-import") (part "CAPACITOR1210K"))
    )
    (comp (ref "C109")
      (value "2.2uF")
      (footprint "eagle-import:C0805")
      (libsource (lib "eagle-import") (part "misclib3_C-USC0805"))
    )
    (comp (ref "C110")
      (value "2.2uF")
      (footprint "eagle-import:C0805")
      (libsource (lib "eagle-import") (part "misclib3_C-USC0805"))
    )
    (comp (ref "C111")
      (value "22uF")
      (footprint "eagle-import:1210K")
      (libsource (lib "eagle-import") (part "CAPACITOR1210K"))
    )
    (comp (ref "CON1")
      (value "1734035-2")
      (footprint "eagle-import:1734035-2")
      (libsource (lib "eagle-import") (part "1734035-2"))
    )
    (comp (ref "D4")
      (value "DIODE-MINIMELF")
      (footprint "eagle-import:MINIMELF")
      (libsource (lib "eagle-import") (part "DIODE-MINIMELF"))
    )
    (comp (ref "FID1")
      (value "FIDUCIALSMD")
      (footprint "eagle-import:FIDUCIAL")
      (libsource (lib "eagle-import") (part "FIDUCIALSMD"))
    )
    (comp (ref "FID2")
      (value "FIDUCIALSMD")
      (footprint "eagle-import:FIDUCIAL")
      (libsource (lib "eagle-import") (part "FIDUCIALSMD"))
    )
    (comp (ref "FID3")
      (value "FIDUCIALSMD")
      (footprint "eagle-import:FIDUCIAL")
      (libsource (lib "eagle-import") (part "FIDUCIALSMD"))
    )
    (comp (ref "FID4")
      (value "FIDUCIALSMD")
      (footprint "eagle-import:FIDUCIAL")
      (libsource (lib "eagle-import") (part "FIDUCIALSMD"))
    )
    (comp (ref "L20")
      (value "22uH_744053220")
      (footprint "eagle-import:POWER-CHOKE_WE-TPC")
      (libsource (lib "eagle-import") (part "L-USWE-TPC"))
    )
    (comp (ref "L21")
      (value "22uH_744053220")
      (footprint "eagle-import:POWER-CHOKE_WE-TPC")
      (libsource (lib "eagle-import") (part "L-USWE-TPC"))
    )
    (comp (ref "R50")
      (value "120")
      (footprint "eagle-import:R0603")
      (libsource (lib "eagle-import") (part "R-US_R0603"))
    )
    (comp (ref "R52")
      (value "10")
      (footprint "eagle-import:R0603")
      (libsource (lib "eagle-import") (part "R-US_R0603"))
    )
    (comp (ref "U4")
      (value "LD1117S12TR")
      (footprint "eagle-import:SOT-223")
      (libsource (lib "eagle-import") (part "LD1117S12TR"))
    )
    (comp (ref "U12")
      (value "ADP7156ARDZ-3.3-R7")
      (footprint "eagle-import:SO8")
      (libsource (lib "eagle-import") (part "ADP7156SO8"))
    )
    (comp (ref "C3")
      (value ".01uF")
      (footprint "eagle-import:C0402")
      (libsource (lib "eagle-import") (part "C-USC0402"))
    )
    (comp (ref "C4")
      (value "1.0uF")
      (footprint "eagle-import:C0402")
      (libsource (lib "eagle-import") (part "C-USC0402"))
    )
    (comp (ref "C5")
      (value "C-USC0402")
      (footprint "eagle-import:C0402")
      (libsource (lib "eagle-import") (part "C-USC0402"))
    )
    (comp (ref "C12")
      (value "47nF")
      (footprint "eagle-import:C0402")
      (libsource (lib "eagle-import") (part "C-USC0402"))
    )
    (comp (ref "C14")
      (value "47nF")
      (footprint "eagle-import:C0402")
      (libsource (lib "eagle-import") (part "C-USC0402"))
    )
    (comp (ref "C16")
      (value "2.2uF")
      (footprint "eagle-import:C0805")
      (libsource (lib "eagle-import") (part "resistor_C-USC0805"))
    )
    (comp (ref "C18")
      (value "47nF")
      (footprint "eagle-import:C0402")
      (libsource (lib "eagle-import") (part "C-USC0402"))
    )
    (comp (ref "C19")
      (value "47nF")
      (footprint "eagle-import:C0402")
      (libsource (lib "eagle-import") (part "C-USC0402"))
    )
    (comp (ref "C20")
      (value "47nF")
      (footprint "eagle-import:C0402")
      (libsource (lib "eagle-import") (part "C-USC0402"))
    )
    (comp (ref "C21")
      (value "C-USC0402")
      (footprint "eagle-import:C0402")
      (libsource (lib "eagle-import") (part "C-USC0402"))
    )
    (comp (ref "C23")
      (value "1.0uF")
      (footprint "eagle-import:C0402")
      (libsource (lib "eagle-import") (part "C-USC0402"))
    )
    (comp (ref "C24")
      (value "1.0uF")
      (footprint "eagle-import:C0402")
      (libsource (lib "eagle-import") (part "C-USC0402"))
    )
    (comp (ref "C40")
      (value "0.1uF")
      (footprint "eagle-import:0402")
      (libsource (lib "eagle-import") (part "CAPACITOR0402"))
    )
    (comp (ref "C85")
      (value "0.1uF")
      (footprint "eagle-import:0402")
      (libsource (lib "eagle-import") (part "CAPACITOR0402"))
    )
    (comp (ref "C86")
      (value "0.1uF")
      (footprint "eagle-import:0402")
      (libsource (lib "eagle-import") (part "CAPACITOR0402"))
    )
    (comp (ref "C87")
      (value "0.1uF")
      (footprint "eagle-import:0402")
      (libsource (lib "eagle-import") (part "CAPACITOR0402"))
    )
    (comp (ref "C88")
      (value "0.1uF")
      (footprint "eagle-import:0402")
      (libsource (lib "eagle-import") (part "CAPACITOR0402"))
    )
    (comp (ref "C89")
      (value "0.1uF")
      (footprint "eagle-import:0402")
      (libsource (lib "eagle-import") (part "CAPACITOR0402"))
    )
    (comp (ref "C90")
      (value "0.1uF")
      (footprint "eagle-import:0402")
      (libsource (lib "eagle-import") (part "CAPACITOR0402"))
    )
    (comp (ref "C91")
      (value "0.1uF")
      (footprint "eagle-import:0402")
      (libsource (lib "eagle-import") (part "CAPACITOR0402"))
    )
    (comp (ref "C92")
      (value "0.1uF")
      (footprint "eagle-import:0402")
      (libsource (lib "eagle-import") (part "CAPACITOR0402"))
    )
    (comp (ref "C94")
      (value "0.1uF")
      (footprint "eagle-import:0402")
      (libsource (lib "eagle-import") (part "CAPACITOR0402"))
    )
    (comp (ref "C95")
      (value "2.2uF")
      (footprint "eagle-import:C0805")
      (libsource (lib "eagle-import") (part "resistor_C-USC0805"))
    )
    (comp (ref "C96")
      (value "0.1uF")
      (footprint "eagle-import:0402")
      (libsource (lib "eagle-import") (part "CAPACITOR0402"))
    )
    (comp (ref "C98")
      (value "0.1uF")
      (footprint "eagle-import:0402")
      (libsource (lib "eagle-import") (part "CAPACITOR0402"))
    )
    (comp (ref "C99")
      (value "0.1uF")
      (footprint "eagle-import:0402")
      (libsource (lib "eagle-import") (part "CAPACITOR0402"))
    )
    (comp (ref "C100")
      (value "2.2uF")
      (footprint "eagle-import:C0805")
      (libsource (lib "eagle-import") (part "resistor_C-USC0805"))
    )
    (comp (ref "C101")
      (value "0.1uF")
      (footprint "eagle-import:0402")
      (libsource (lib "eagle-import") (part "CAPACITOR0402"))
    )
    (comp (ref "C102")
      (value "2.2uF")
      (footprint "eagle-import:C0805")
      (libsource (lib "eagle-import") (part "resistor_C-USC0805"))
    )
    (comp (ref "C113")
      (value "47nF")
      (footprint "eagle-import:C0402")
      (libsource (lib "eagle-import") (part "C-USC0402"))
    )
    (comp (ref "C221")
      (value "1.0uF")
      (footprint "eagle-import:C0402")
      (libsource (lib "eagle-import") (part "C-USC0402"))
    )
    (comp (ref "C222")
      (value "18pF")
      (footprint "eagle-import:C0402")
      (libsource (lib "eagle-import") (part "C-USC0402"))
    )
    (comp (ref "JP1")
      (value "PINHD-1X6")
      (footprint "eagle-import:1X06")
      (libsource (lib "eagle-import") (part "PINHD-1X6"))
    )
    (comp (ref "JP3")
      (value "PINHD-1X2")
      (footprint "eagle-import:1X02")
      (libsource (lib "eagle-import") (part "PINHD-1X2"))
    )
    (comp (ref "L1")
      (value "WE-CBF_0603")
      (footprint "eagle-import:0603")
      (libsource (lib "eagle-import") (part "WE-CBF_0603"))
    )
    (comp (ref "L2")
      (value "WE-CBF_0402")
      (footprint "eagle-import:0402")
      (libsource (lib "eagle-import") (part "WE-CBF_0402"))
    )
    (comp (ref "L19")
      (value "WE-CBF_0603")
      (footprint "eagle-import:0603")
      (libsource (lib "eagle-import") (part "WE-CBF_0603"))
    )
    (comp (ref "R2")
      (value "470 (Tc=50ppm)")
      (footprint "eagle-import:R0402")
      (libsource (lib "eagle-import") (part "R-US_R0402"))
    )
    (comp (ref "R5")
      (value "470 (Tc=50ppm)")
      (footprint "eagle-import:R0402")
      (libsource (lib "eagle-import") (part "R-US_R0402"))
    )
    (comp (ref "R8")
      (value "4.87K")
      (footprint "eagle-import:R0603")
      (libsource (lib "eagle-import") (part "R-US_R0603"))
    )
    (comp (ref "R49")
      (value "4.87K")
      (footprint "eagle-import:R0603")
      (libsource (lib "eagle-import") (part "R-US_R0603"))
    )
    (comp (ref "R56")
      (value "12.1k")
      (footprint "eagle-import:R0603")
      (libsource (lib "eagle-import") (part "R-US_R0603"))
    )
    (comp (ref "R63")
      (value "12.1k")
      (footprint "eagle-import:R0603")
      (libsource (lib "eagle-import") (part "R-US_R0603"))
    )
    (comp (ref "R64")
      (value "27")
      (footprint "eagle-import:R0603")
      (libsource (lib "eagle-import") (part "R-US_R0603"))
    )
    (comp (ref "R65")
      (value "27")
      (footprint "eagle-import:R0603")
      (libsource (lib "eagle-import") (part "R-US_R0603"))
    )
    (comp (ref "SW3")
      (value "HOKURIKU_KSM06_6X6MM_SWITCH1")
      (footprint "eagle-import:TACTILE_6X6MM")
      (libsource (lib "eagle-import") (part "HOKURIKU_KSM06_6X6MM_SWITCH1"))
    )
    (comp (ref "U3")
      (value "SN74AC74DR")
      (footprint "eagle-import:SO14")
      (libsource (lib "eagle-import") (part "7474DHC"))
    )
    (comp (ref "U5")
      (value "74LVC1G04DBV")
      (footprint "eagle-import:SOT23-5")
      (libsource (lib "eagle-import") (part "741G04DBVLVC"))
    )
    (comp (ref "U6")
      (value "74LVC1G04DBV")
      (footprint "eagle-import:SOT23-5")
      (libsource (lib "eagle-import") (part "741G04DBVLVC"))
    )
    (comp (ref "U8")
      (value "FT230XQ")
      (footprint "eagle-import:QFN16")
      (libsource (lib "eagle-import") (part "FT230XQ"))
    )
    (comp (ref "U17")
      (value "TPS799X")
      (footprint "eagle-import:SOT23-6")
      (libsource (lib "eagle-import") (part "TPS799X"))
    )
    (comp (ref "X3")
      (value "DNP")
      (footprint "eagle-import:ECS-250-20-30B-DU_CRYSTAL")
      (libsource (lib "eagle-import") (part "ECS-250-20-30B-DUDU"))
    )
    (comp (ref "X5")
      (value "ASVTX-12-A-40.000MHZ-H10-T")
      (footprint "eagle-import:CRYSTAL_2.5_2MM")
      (libsource (lib "eagle-import") (part "CRYSTAL40MHZ2.5_2MM"))
    )
    (comp (ref "Z3")
      (value "SR3.3.TCT")
      (footprint "eagle-import:SR2.8.TCT_1PRIMARY")
      (libsource (lib "eagle-import") (part "SR2.8_TVS"))
    )
  )
  (nets
    (net (code "5") (name "+5V") (class "Default")
      (node (ref "C108") (pin "A") (pinfunction "A_A") (pintype "passive"))
      (node (ref "C111") (pin "A") (pinfunction "A_A") (pintype "passive"))
      (node (ref "C23") (pin "1") (pinfunction "1_1") (pintype "passive"))
      (node (ref "JP2") (pin "12") (pinfunction "12_12") (pintype "passive"))
      (node (ref "JP5") (pin "12") (pinfunction "12_12") (pintype "passive"))
      (node (ref "JP6") (pin "12") (pinfunction "12_12") (pintype "passive"))
      (node (ref "JP7") (pin "12") (pinfunction "12_12") (pintype "passive"))
      (node (ref "L21") (pin "1") (pinfunction "1_1") (pintype "passive"))
      (node (ref "U12") (pin "4") (pinfunction "EN_4") (pintype "passive"))
      (node (ref "U12") (pin "8") (pinfunction "VIN_8") (pintype "passive"))
      (node (ref "U8") (pin "10") (pinfunction "VCC_10") (pintype "power_in"))
    )
    (net (code "14") (name "3V3") (class "Default")
      (node (ref "C10") (pin "1") (pinfunction "1_1") (pintype "passive"))
      (node (ref "C101") (pin "1") (pinfunction "A_1") (pintype "passive"))
      (node (ref "C103") (pin "1") (pinfunction "1_1") (pintype "passive"))
      (node (ref "C104") (pin "1") (pinfunction "1_1") (pintype "passive"))
      (node (ref "C11") (pin "1") (pinfunction "1_1") (pintype "passive"))
      (node (ref "C12") (pin "1") (pinfunction "1_1") (pintype "passive"))
      (node (ref "C13") (pin "1") (pinfunction "1_1") (pintype "passive"))
      (node (ref "C15") (pin "1") (pinfunction "1_1") (pintype "passive"))
      (node (ref "C16") (pin "1") (pinfunction "1_1") (pintype "passive"))
      (node (ref "C17") (pin "1") (pinfunction "1_1") (pintype "passive"))
      (node (ref "C18") (pin "1") (pinfunction "1_1") (pintype "passive"))
      (node (ref "C19") (pin "1") (pinfunction "1_1") (pintype "passive"))
      (node (ref "C39") (pin "1") (pinfunction "1_1") (pintype "passive"))
      (node (ref "C41") (pin "1") (pinfunction "1_1") (pintype "passive"))
      (node (ref "C6") (pin "A") (pinfunction "A_A") (pintype "passive"))
      (node (ref "C76") (pin "1") (pinfunction "1_1") (pintype "passive"))
      (node (ref "C85") (pin "1") (pinfunction "A_1") (pintype "passive"))
      (node (ref "C86") (pin "1") (pinfunction "A_1") (pintype "passive"))
      (node (ref "C87") (pin "1") (pinfunction "A_1") (pintype "passive"))
      (node (ref "C88") (pin "1") (pinfunction "A_1") (pintype "passive"))
      (node (ref "C89") (pin "1") (pinfunction "A_1") (pintype "passive"))
      (node (ref "C90") (pin "1") (pinfunction "A_1") (pintype "passive"))
      (node (ref "C91") (pin "1") (pinfunction "A_1") (pintype "passive"))
      (node (ref "C92") (pin "1") (pinfunction "A_1") (pintype "passive"))
      (node (ref "C94") (pin "1") (pinfunction "A_1") (pintype "passive"))
      (node (ref "C95") (pin "1") (pinfunction "1_1") (pintype "passive"))
      (node (ref "C96") (pin "1") (pinfunction "A_1") (pintype "passive"))
      (node (ref "C98") (pin "1") (pinfunction "A_1") (pintype "passive"))
      (node (ref "D1") (pin "A") (pinfunction "A_A") (pintype "passive"))
      (node (ref "D2") (pin "A") (pinfunction "A_A") (pintype "passive"))
      (node (ref "D3") (pin "A") (pinfunction "A_A") (pintype "passive"))
      (node (ref "D4") (pin "A") (pinfunction "A_A") (pintype "passive"))
      (node (ref "D8") (pin "A") (pinfunction "A_A") (pintype "passive"))
      (node (ref "JP2") (pin "6") (pinfunction "11_6") (pintype "passive"))
      (node (ref "JP5") (pin "6") (pinfunction "11_6") (pintype "passive"))
      (node (ref "JP6") (pin "6") (pinfunction "11_6") (pintype "passive"))
      (node (ref "JP7") (pin "6") (pinfunction "11_6") (pintype "passive"))
      (node (ref "JP8") (pin "1") (pinfunction "1_1") (pintype "passive"))
      (node (ref "JP8") (pin "10") (pinfunction "10_10") (pintype "passive"))
      (node (ref "JP8") (pin "2") (pinfunction "2_2") (pintype "passive"))
      (node (ref "JP8") (pin "9") (pinfunction "9_9") (pintype "passive"))
      (node (ref "L1") (pin "1") (pinfunction "1_1") (pintype "passive"))
      (node (ref "L17") (pin "2") (pinfunction "2_2") (pintype "passive"))
      (node (ref "L19") (pin "1") (pinfunction "1_1") (pintype "passive"))
      (node (ref "L2") (pin "1") (pinfunction "1_1") (pintype "passive"))
      (node (ref "L20") (pin "2") (pinfunction "2_2") (pintype "passive"))
      (node (ref "L6") (pin "1") (pinfunction "1_1") (pintype "passive"))
      (node (ref "R53") (pin "1") (pinfunction "1_1") (pintype "passive"))
      (node (ref "R54") (pin "1") (pinfunction "1_1") (pintype "passive"))
      (node (ref "R55") (pin "1") (pinfunction "1_1") (pintype "passive"))
      (node (ref "R56") (pin "1") (pinfunction "1_1") (pintype "passive"))
      (node (ref "R61") (pin "1") (pinfunction "1_1") (pintype "passive"))
      (node (ref "R62") (pin "1") (pinfunction "1_1") (pintype "passive"))
      (node (ref "R63") (pin "1") (pinfunction "1_1") (pintype "passive"))
      (node (ref "R67") (pin "2") (pinfunction "2_2") (pintype "passive"))
      (node (ref "R8") (pin "1") (pinfunction "1_1") (pintype "passive"))
      (node (ref "U1") (pin "1") (pinfunction "VDD2A_1") (pintype "passive"))
      (node (ref "U1") (pin "19") (pinfunction "VDD1A_19") (pintype "passive"))
      (node (ref "U1") (pin "9") (pinfunction "VDDIO_9") (pintype "passive"))
      (node (ref "U10") (pin "3") (pinfunction "/WP_3") (pintype "input"))
      (node (ref "U10") (pin "7") (pinfunction "/HOLD_7") (pintype "input"))
      (node (ref "U10") (pin "8") (pinfunction "VCC_8") (pintype "power_in"))
      (node (ref "U11") (pin "3") (pinfunction "/WP_3") (pintype "input"))
      (node (ref "U11") (pin "7") (pinfunction "/HOLD_7") (pintype "input"))
      (node (ref "U11") (pin "8") (pinfunction "VCC_8") (pintype "power_in"))
      (node (ref "U2") (pin "A13") (pinfunction "VCCIO_0_A13") (pintype "power_in"))
      (node (ref "U2") (pin "A3") (pinfunction "VCCIO_0_2_A3") (pintype "power_in"))
      (node (ref "U2") (pin "A8") (pinfunction "VCCIO_0_3_A8") (pintype "power_in"))
      (node (ref "U2") (pin "C15") (pinfunction "VCCIO_1_C15") (pintype "power_in"))
      (node (ref "U2") (pin "E1") (pinfunction "VCCIO_3_2_E1") (pintype "power_in"))
      (node (ref "U2") (pin "F8") (pinfunction "VCCIO_0_F8") (pintype "power_in"))
      (node (ref "U2") (pin "G6") (pinfunction "VCCIO_3_3_G6") (pintype "power_in"))
      (node (ref "U2") (pin "H10") (pinfunction "VCCIO_1_2_H10") (pintype "power_in"))
      (node (ref "U2") (pin "H15") (pinfunction "VCCIO_1_3_H15") (pintype "power_in"))
      (node (ref "U2") (pin "J6") (pinfunction "VCCIO_3_J6") (pintype "power_in"))
      (node (ref "U2") (pin "K8") (pinfunction "VCCIO_2_2_K8") (pintype "power_in"))
      (node (ref "U2") (pin "N1") (pinfunction "VCCIO_3_N1") (pintype "power_in"))
      (node (ref "U2") (pin "N13") (pinfunction "VCC_SPI_N13") (pintype "power_in"))
      (node (ref "U2") (pin "N15") (pinfunction "VCCIO_1_N15") (pintype "power_in"))
      (node (ref "U2") (pin "P3") (pinfunction "VCCIO_2_3_P3") (pintype "power_in"))
      (node (ref "U2") (pin "R13") (pinfunction "VCCIO_2_R13") (pintype "power_in"))
      (node (ref "U2") (pin "R8") (pinfunction "VCCIO_2_R8") (pintype "power_in"))
      (node (ref "U3") (pin "1") (pinfunction "CLR_1") (pintype "input"))
      (node (ref "U3") (pin "14") (pinfunction "VCC_14") (pintype "power_in"))
      (node (ref "U3") (pin "4") (pinfunction "PRE_4") (pintype "input"))
      (node (ref "U4") (pin "3") (pinfunction "INPUT_3") (pintype "passive"))
      (node (ref "U5") (pin "5") (pinfunction "VCC_5") (pintype "power_in"))
      (node (ref "U6") (pin "5") (pinfunction "VCC_5") (pintype "power_in"))
      (node (ref "U9") (pin "108") (pinfunction "VDD_108") (pintype "passive"))
      (node (ref "U9") (pin "121") (pinfunction "VDD_121") (pintype "passive"))
      (node (ref "U9") (pin "131") (pinfunction "VDD_131") (pintype "passive"))
      (node (ref "U9") (pin "143") (pinfunction "PDR_ON_143") (pintype "passive"))
      (node (ref "U9") (pin "144") (pinfunction "VDD_144") (pintype "passive"))
      (node (ref "U9") (pin "17") (pinfunction "VDD_17") (pintype "passive"))
      (node (ref "U9") (pin "30") (pinfunction "VDD_30") (pintype "passive"))
      (node (ref "U9") (pin "39") (pinfunction "VDD_39") (pintype "passive"))
      (node (ref "U9") (pin "52") (pinfunction "VDD_52") (pintype "passive"))
      (node (ref "U9") (pin "62") (pinfunction "VDD_62") (pintype "passive"))
      (node (ref "U9") (pin "72") (pinfunction "VDD_72") (pintype "passive"))
      (node (ref "U9") (pin "84") (pinfunction "VDD_84") (pintype "passive"))
      (node (ref "U9") (pin "95") (pinfunction "VDD_95") (pintype "passive"))
      (node (ref "X1") (pin "VCC") (pinfunction "VCC_VCC") (pintype "passive"))
      (node (ref "X1") (pin "VDD") (pinfunction "VDD_VDD") (pintype "passive"))
    )
    (net (code "15") (name "20MHZ_REF") (class "Default")
      (node (ref "C14") (pin "2") (pinfunction "2_2") (pintype "passive"))
      (node (ref "C21") (pin "2") (pinfunction "2_2") (pintype "passive"))
      (node (ref "U9") (pin "23") (pinfunction "PH0-OSC_IN/EVENTOUT_23") (pintype "passive"))
      (node (ref "X3") (pin "1") (pinfunction "P$1_1") (pintype "passive"))
    )
    (net (code "16") (name "ADDR0") (class "Default")
      (node (ref "U2") (pin "C16") (pinfunction "IOR_161_C16") (pintype "bidirectional"))
      (node (ref "U9") (pin "10") (pinfunction "PF0/FSMC_A0/I2C2_SDA/EVENTOUT_10") (pintype "passive"))
    )
    (net (code "17") (name "ADDR1") (class "Default")
      (node (ref "U2") (pin "T15") (pinfunction "IOB_91_T15") (pintype "bidirectional"))
      (node (ref "U9") (pin "11") (pinfunction "PF1/FSMC_A1/I2C2_SCL/EVENTOUT_11") (pintype "passive"))
    )
    (net (code "18") (name "ADDR2") (class "Default")
      (node (ref "U2") (pin "R16") (pinfunction "IOB_102_R16") (pintype "bidirectional"))
      (node (ref "U9") (pin "12") (pinfunction "PF2/FSMC_A2/I2C2_SMBA/EVENTOUT_12") (pintype "passive"))
    )
    (net (code "19") (name "ADDR3") (class "Default")
      (node (ref "U2") (pin "R15") (pinfunction "IOR_110_R15") (pintype "bidirectional"))
      (node (ref "U9") (pin "13") (pinfunction "PF3/FSMC_A3/EVENTOUT/ADC3_IN9_13") (pintype "passive"))
    )
    (net (code "20") (name "ADDR4") (class "Default")
      (node (ref "U2") (pin "P16") (pinfunction "IOR_113_P16") (pintype "bidirectional"))
      (node (ref "U9") (pin "14") (pinfunction "PF4/FSMC_A4/EVENTOUT/ADC3_IN14_14") (pintype "passive"))
    )
    (net (code "21") (name "ADDR5") (class "Default")
      (node (ref "U2") (pin "P15") (pinfunction "IOR_112_P15") (pintype "bidirectional"))
      (node (ref "U9") (pin "15") (pinfunction "PF5/FSMC_A5/EVENTOUT/ADC3_IN15_15") (pintype "passive"))
    )
    (net (code "22") (name "ADDR6") (class "Default")
      (node (ref "U2") (pin "N16") (pinfunction "IOR_117_N16") (pintype "bidirectional"))
      (node (ref "U9") (pin "50") (pinfunction "PF12/FSMC_A6/EVENTOUT_50") (pintype "passive"))
    )
    (net (code "23") (name "ADDR7") (class "Default")
      (node (ref "U2") (pin "M16") (pinfunction "IOR_121_M16") (pintype "bidirectional"))
      (node (ref "U9") (pin "53") (pinfunction "PF13/FSMC_A7/EVENTOUT_53") (pintype "passive"))
    )
    (net (code "24") (name "ADDR8") (class "Default")
      (node (ref "U2") (pin "M15") (pinfunction "IOR_123_M15") (pintype "bidirectional"))
      (node (ref "U9") (pin "54") (pinfunction "PF14/FSMC_A8/EVENTOUT_54") (pintype "passive"))
    )
    (net (code "25") (name "ADDR9") (class "Default")
      (node (ref "U2") (pin "L16") (pinfunction "IOR_127_L16") (pintype "bidirectional"))
      (node (ref "U9") (pin "55") (pinfunction "PF15/FSMC_A9/EVENTOUT_55") (pintype "passive"))
    )
    (net (code "26") (name "ADDR10") (class "Default")
      (node (ref "U2") (pin "T14") (pinfunction "IOB_92_T14") (pintype "bidirectional"))
      (node (ref "U9") (pin "56") (pinfunction "PG0/FSMC_A10/EVENTOUT_56") (pintype "passive"))
    )
    (net (code "27") (name "ADDR11") (class "Default")
      (node (ref "U2") (pin "R14") (pinfunction "IOR_109_R14") (pintype "bidirectional"))
      (node (ref "U9") (pin "57") (pinfunction "PG1/FSMC_A11/EVENTOUT_57") (pintype "passive"))
    )
    (net (code "28") (name "ADDR12") (class "Default")
      (node (ref "U2") (pin "P14") (pinfunction "IOR_111_P14") (pintype "bidirectional"))
      (node (ref "U9") (pin "87") (pinfunction "PG2/FSMC_A12/EVENTOUT_87") (pintype "passive"))
    )
    (net (code "29") (name "ADDR13") (class "Default")
      (node (ref "U2") (pin "L14") (pinfunction "IOR_119_L14") (pintype "bidirectional"))
      (node (ref "U9") (pin "88") (pinfunction "PG3/FSMC_A13/EVENTOUT_88") (pintype "passive"))
    )
    (net (code "30") (name "ADDR14") (class "Default")
      (node (ref "U2") (pin "D14") (pinfunction "IOR_167_D14") (pintype "bidirectional"))
      (node (ref "U9") (pin "89") (pinfunction "PG4/FSMC_A14/EVENTOUT_89") (pintype "passive"))
    )
    (net (code "31") (name "ADDR15") (class "Default")
      (node (ref "U2") (pin "C14") (pinfunction "IOT_168_C14") (pintype "bidirectional"))
      (node (ref "U9") (pin "90") (pinfunction "PG5/FSMC_A15/EVENTOUT_90") (pintype "passive"))
    )
    (net (code "32") (name "AUDIO_LEFT") (class "Default")
      (node (ref "C79") (pin "1") (pinfunction "1_1") (pintype "passive"))
      (node (ref "J2") (pin "R") (pinfunction "R_R") (pintype "passive"))
      (node (ref "R38") (pin "1") (pinfunction "1_1") (pintype "passive"))
    )
    (net (code "33") (name "AUDIO_RIGHT") (class "Default")
      (node (ref "C78") (pin "1") (pinfunction "1_1") (pintype "passive"))
      (node (ref "J2") (pin "L") (pinfunction "L_L") (pintype "passive"))
      (node (ref "R37") (pin "1") (pinfunction "1_1") (pintype "passive"))
    )
    (net (code "34") (name "CBSEL") (class "Default")
      (node (ref "U2") (pin "P13") (pinfunction "IOB_104_CBSEL1_P13") (pintype "bidirectional"))
      (node (ref "U9") (pin "91") (pinfunction "PG6/FSMC_INT2/EVENTOUT_91") (pintype "passive"))
    )
    (net (code "35") (name "CDONE") (class "Default")
      (node (ref "U2") (pin "M10") (pinfunction "CDONE_M10") (pintype "passive"))
      (node (ref "U9") (pin "92") (pinfunction "PG7/FSMC_INT3/USART6_CK/EVENTOUT_92") (pintype "passive"))
    )
    (net (code "36") (name "CRESET_B") (class "Default")
      (node (ref "U2") (pin "N11") (pinfunction "CRESET_B_N11") (pintype "passive"))
      (node (ref "U9") (pin "93") (pinfunction "PG8/USART6_RTS/ETH_PPS_OUT/EVENTOUT_93") (pintype "passive"))
    )
    (net (code "37") (name "DATA0") (class "Default")
      (node (ref "U2") (pin "D16") (pinfunction "IOR_153_D16") (pintype "bidirectional"))
      (node (ref "U9") (pin "85") (pinfunction "PD14/FSMC_D0/TIM4_CH3/EVENTOUT_85") (pintype "passive"))
    )
    (net (code "38") (name "DATA1") (class "Default")
      (node (ref "U2") (pin "D15") (pinfunction "IOR_157_D15") (pintype "bidirectional"))
      (node (ref "U9") (pin "86") (pinfunction "PD15/FSMC_D1/TIM4_CH4/EVENTOUT_86") (pintype "passive"))
    )
    (net (code "39") (name "DATA2") (class "Default")
      (node (ref "U2") (pin "B16") (pinfunction "IOR_165_B16") (pintype "bidirectional"))
      (node (ref "U9") (pin "114") (pinfunction "PD0/FSMC_D2/CAN1_RX/EVENTOUT_114") (pintype "passive"))
    )
    (net (code "40") (name "DATA3") (class "Default")
      (node (ref "U2") (pin "B15") (pinfunction "IOT_169_B15") (pintype "bidirectional"))
      (node (ref "U9") (pin "115") (pinfunction "PD1/FSMC_D3/CAN1_TX/EVENTOUT_115") (pintype "passive"))
    )
    (net (code "41") (name "DATA4") (class "Default")
      (node (ref "U2") (pin "A16") (pinfunction "IOT_176_A16") (pintype "bidirectional"))
      (node (ref "U9") (pin "58") (pinfunction "PE7/FSMC_D4/TIM1_ETR/EVENTOUT_58") (pintype "passive"))
    )
    (net (code "42") (name "DATA5") (class "Default")
      (node (ref "U2") (pin "A15") (pinfunction "IOT_177_A15") (pintype "bidirectional"))
      (node (ref "U9") (pin "59") (pinfunction "PE8/FSMC_D5/TIM1/CH1N/EVENTOUT_59") (pintype "passive"))
    )
    (net (code "43") (name "DATA6") (class "Default")
      (node (ref "U2") (pin "E16") (pinfunction "IOR_151_E16") (pintype "bidirectional"))
      (node (ref "U9") (pin "60") (pinfunction "PE9/FSMC_D6/TIM1_CH1/EVENTOUT_60") (pintype "passive"))
    )
    (net (code "44") (name "DATA7") (class "Default")
      (node (ref "U2") (pin "F15") (pinfunction "IOR_149_F15") (pintype "bidirectional"))
      (node (ref "U9") (pin "63") (pinfunction "PE10/FSMC_D7/TIM1_CH2N/EVENTOUT_63") (pintype "passive"))
    )
    (net (code "45") (name "DATA8") (class "Default")
      (node (ref "U2") (pin "F16") (pinfunction "IOR_147_F16") (pintype "bidirectional"))
      (node (ref "U9") (pin "64") (pinfunction "PE11/FSMC_D8/TIM1_CH2/EVENTOUT_64") (pintype "passive"))
    )
    (net (code "46") (name "DATA9") (class "Default")
      (node (ref "U2") (pin "G15") (pinfunction "IOR_145_G15") (pintype "bidirectional"))
      (node (ref "U9") (pin "65") (pinfunction "PE12/FSMC_D9/TIM1_CH3N/EVENTOUT_65") (pintype "passive"))
    )
    (net (code "47") (name "DATA10") (class "Default")
      (node (ref "U2") (pin "G16") (pinfunction "IOR_143_G16") (pintype "bidirectional"))
      (node (ref "U9") (pin "66") (pinfunction "PE13/FSMC_D10/TIM1_CH3/EVENTOUT_66") (pintype "passive"))
    )
    (net (code "48") (name "DATA11") (class "Default")
      (node (ref "U2") (pin "J15") (pinfunction "IOR_130_J15") (pintype "bidirectional"))
      (node (ref "U9") (pin "67") (pinfunction "PE14/FSMC_D11/TIM1_CH4/EVENTOUT_67") (pintype "passive"))
    )
    (net (code "49") (name "DATA12") (class "Default")
      (node (ref "U2") (pin "J16") (pinfunction "IOR_138_J16") (pintype "bidirectional"))
      (node (ref "U9") (pin "68") (pinfunction "PE15/FSMC_D12/TIM1_BKIN/EVENTOUT_68") (pintype "passive"))
    )
    (net (code "50") (name "DATA13") (class "Default")
      (node (ref "U2") (pin "K15") (pinfunction "IOR_131_K15") (pintype "bidirectional"))
      (node (ref "U9") (pin "77") (pinfunction "PD8/FSMC_D13/USART3_TX/EVENTOUT_77") (pintype "passive"))
    )
    (net (code "51") (name "DATA14") (class "Default")
      (node (ref "U2") (pin "K16") (pinfunction "IOR_133_K16") (pintype "bidirectional"))
      (node (ref "U9") (pin "78") (pinfunction "PD9/FSMC_D14/USART3_RX/EVENTOUT_78") (pintype "passive"))
    )
    (net (code "52") (name "DATA15") (class "Default")
      (node (ref "U2") (pin "T16") (pinfunction "IOB_100_T16") (pintype "bidirectional"))
      (node (ref "U9") (pin "79") (pinfunction "PD10/FSMC_D15/USART3_CK/EVENTOUT_79") (pintype "passive"))
    )
    (net (code "53") (name "ETH_RMII_REF_CLK") (class "Default")
      (node (ref "C22") (pin "1") (pinfunction "1_1") (pintype "passive"))
      (node (ref "U9") (pin "35") (pinfunction "PA1/USART2_RTS/UART4_RX/ETH_RMII_REF_CLK/ETH_MII_RX_CLK/TIM5_CH2/TIMM2_CH2/EVENTOUT/ADC123_IN1_35") (pintype "passive"))
    )
    (net (code "54") (name "ETH_RX+") (class "Default")
      (node (ref "J1") (pin "4") (pinfunction "RD+_4") (pintype "passive"))
      (node (ref "R26") (pin "2") (pinfunction "2_2") (pintype "passive"))
      (node (ref "U1") (pin "23") (pinfunction "RXP_23") (pintype "passive"))
      (node (ref "Z2") (pin "3") (pinfunction "I/O_3") (pintype "passive"))
    )
    (net (code "55") (name "ETH_RX-") (class "Default")
      (node (ref "J1") (pin "6") (pinfunction "RD-_6") (pintype "passive"))
      (node (ref "R25") (pin "2") (pinfunction "2_2") (pintype "passive"))
      (node (ref "U1") (pin "22") (pinfunction "RXN_22") (pintype "passive"))
      (node (ref "Z2") (pin "2") (pinfunction "I/O_2") (pintype "passive"))
    )
    (net (code "56") (name "ETH_TX+") (class "Default")
      (node (ref "J1") (pin "1") (pinfunction "TD+_1") (pintype "passive"))
      (node (ref "R23") (pin "2") (pinfunction "2_2") (pintype "passive"))
      (node (ref "U1") (pin "21") (pinfunction "TXP_21") (pintype "passive"))
      (node (ref "Z1") (pin "3") (pinfunction "I/O_3") (pintype "passive"))
    )
    (net (code "57") (name "ETH_TX-") (class "Default")
      (node (ref "J1") (pin "3") (pinfunction "TD-_3") (pintype "passive"))
      (node (ref "R24") (pin "2") (pinfunction "2_2") (pintype "passive"))
      (node (ref "U1") (pin "20") (pinfunction "TXN_20") (pintype "passive"))
      (node (ref "Z1") (pin "2") (pinfunction "I/O_2") (pintype "passive"))
    )
    (net (code "58") (name "FLASH1_CS") (class "Default")
      (node (ref "U10") (pin "1") (pinfunction "/CS_1") (pintype "input"))
      (node (ref "U9") (pin "98") (pinfunction "PC8/TIM8_CH3/SDIO_D0/TIM3_CH3/USART6_CK/DCMI_D2/EVENTOUT_98") (pintype "passive"))
    )
    (net (code "59") (name "FLASH2_CS") (class "Default")
      (node (ref "U11") (pin "1") (pinfunction "/CS_1") (pintype "input"))
      (node (ref "U9") (pin "99") (pinfunction "PC9/I2S_CKIN/MC02/TIM8_CH4/SDIO_D1/I2C3_SDA/DCMI_D3/TIM3_CH4/EVENTOUT_99") (pintype "passive"))
    )
    (net (code "60") (name "FPGA_40MHZ_REF") (class "Default")
      (node (ref "C113") (pin "1") (pinfunction "1_1") (pintype "passive"))
      (node (ref "U2") (pin "R9") (pinfunction "IOB_81_GBIN5_R9") (pintype "bidirectional"))
    )
    (net (code "61") (name "FPGA_CFG_CS") (class "Default")
      (node (ref "U2") (pin "R12") (pinfunction "IOB_108_SS_R12") (pintype "bidirectional"))
      (node (ref "U9") (pin "97") (pinfunction "PC7/I2S3_MCK/TIM8_CH2/SDIO_D7/USART6_RX/DCMI_D1/TIM3_CH2/EVENTOUT_97") (pintype "passive"))
    )
    (net (code "62") (name "FPGA_SPI3_CS") (class "Default")
      (node (ref "U2") (pin "T13") (pinfunction "IOB_94_T13") (pintype "bidirectional"))
      (node (ref "U9") (pin "75") (pinfunction "PB14/SPI2_MISO/TIM1_CH2N/TIM12_CH1/OTG_HS_DM/USART3_RTS/TIM8_CH2N/I2S2EXT_SD/EVENTOUT_75") (pintype "passive"))
    )
    (net (code "63") (name "FPGA_VCC_1V2") (class "Default")
      (node (ref "C7") (pin "A") (pinfunction "A_A") (pintype "passive"))
      (node (ref "R50") (pin "2") (pinfunction "2_2") (pintype "passive"))
      (node (ref "R52") (pin "1") (pinfunction "1_1") (pintype "passive"))
      (node (ref "U2") (pin "A14") (pinfunction "VCC_A14") (pintype "power_in"))
      (node (ref "U2") (pin "F10") (pinfunction "VCC_2_F10") (pintype "power_in"))
      (node (ref "U2") (pin "F6") (pinfunction "VCC_F6") (pintype "power_in"))
      (node (ref "U2") (pin "K10") (pinfunction "VCC_K10") (pintype "power_in"))
      (node (ref "U2") (pin "K6") (pinfunction "VCC_2_K6") (pintype "power_in"))
      (node (ref "U2") (pin "L2") (pinfunction "VCC_3_L2") (pintype "power_in"))
      (node (ref "U4") (pin "2") (pinfunction "OUTPUT_2") (pintype "passive"))
    )
    (net (code "64") (name "FSMC_CLK") (class "Default")
      (node (ref "U2") (pin "K9") (pinfunction "IOB_82_GBIN4_K9") (pintype "bidirectional"))
      (node (ref "U9") (pin "117") (pinfunction "PD3/FSMC_CLK/USART2_CTS/EVENTOUT_117") (pintype "passive"))
    )
    (net (code "65") (name "FSMC_NE1") (class "Default")
      (node (ref "U2") (pin "J14") (pinfunction "IOR_134_J14") (pintype "bidirectional"))
      (node (ref "U9") (pin "123") (pinfunction "PD7/USART2_CK/FSMC_NE1/FSMC_NCE2/EVENTOUT_123") (pintype "passive"))
    )
    (net (code "66") (name "FSMC_NE4") (class "Default")
      (node (ref "U2") (pin "K14") (pinfunction "IOR_129_K14") (pintype "bidirectional"))
      (node (ref "U9") (pin "127") (pinfunction "PG12/FSMC_NE4/USART6_RTS/EVENTOUT_127") (pintype "passive"))
    )
    (net (code "67") (name "FSMC_NL_NADV") (class "Default")
      (node (ref "U2") (pin "B14") (pinfunction "IOT_171_B14") (pintype "bidirectional"))
      (node (ref "U9") (pin "137") (pinfunction "PB7/I2C1_SDA/FSMC_NL/DCMI_VSYNC/USART1_RX/TIM4_CH2/EVENTOUT_137") (pintype "passive"))
    )
    (net (code "68") (name "FSMC_NOE") (class "Default")
      (node (ref "U2") (pin "F14") (pinfunction "IOR_155_F14") (pintype "bidirectional"))
      (node (ref "U9") (pin "118") (pinfunction "PD4/FSMC_NOE/USART2_RTS/EVENTOUT_118") (pintype "passive"))
    )
    (net (code "69") (name "FSMC_NWE") (class "Default")
      (node (ref "U2") (pin "H14") (pinfunction "IOR_142_H14") (pintype "bidirectional"))
      (node (ref "U9") (pin "119") (pinfunction "PD5/FSMC_NWE/USART2_TX/EVENTOUT_119") (pintype "passive"))
    )
    (net (code "70") (name "F_LRCLK") (class "Default")
      (node (ref "U2") (pin "G14") (pinfunction "IOR_150_G14") (pintype "bidirectional"))
      (node (ref "U9") (pin "73") (pinfunction "PB12/SPI2_NSS/I2S2_WS/I2C2_SMBA/USART3_CK/TIM1_BKIN/CAN2_RX/OTG_HS_ULPI_D5/ETH_RMII_TXD0/ETH_MII_TXD0/OTG_HS_ID/EVENTOUT_73") (pintype "passive"))
    )
    (net (code "71") (name "F_MCLK") (class "Default")
      (node (ref "U2") (pin "H16") (pinfunction "IOR_141_GBIN2_H16") (pintype "bidirectional"))
      (node (ref "U9") (pin "96") (pinfunction "PC6/I2S2_MCK/TIM8_CH1/SDIO_D6/USART6_TX/DCMI_D0/TIM3_CH1/EVENTOUT_96") (pintype "passive"))
    )
    (net (code "72") (name "F_SCLK") (class "Default")
      (node (ref "U2") (pin "H11") (pinfunction "IOR_140_GBIN3_H11") (pintype "bidirectional"))
      (node (ref "U9") (pin "74") (pinfunction "PB13/SPI2_SCK/I2S2_CK/USART3_CTS/TIM1_CH1N/CAN2_TX/OTG_HS_ULPI_D6/ETH_RMII_TXD1/ETH_MII_TXD1/EVENTOUT_74") (pintype "passive"))
    )
    (net (code "73") (name "F_SDIN") (class "Default")
      (node (ref "U2") (pin "E14") (pinfunction "IOR_160_E14") (pintype "bidirectional"))
      (node (ref "U9") (pin "76") (pinfunction "PB15/SPI2_MOSI/I2S2_SD/TIM1_CH3N/TIM8_CH3N/TIM12_CH2/OTG_HS_DP/EVENTOUT_76") (pintype "passive"))
    )
    (net (code "74") (name "GB0_CE") (class "Default")
      (node (ref "U2") (pin "F7") (pinfunction "IOT_198_GBIN0_F7") (pintype "bidirectional"))
    )
    (net (code "75") (name "GB1_RST") (class "Default")
      (node (ref "U2") (pin "C8") (pinfunction "IOT_197_GBIN1_C8") (pintype "bidirectional"))
    )
    (net (code "76") (name "GB6_CE") (class "Default")
      (node (ref "U2") (pin "J3") (pinfunction "IOL_14A_GBIN6_J3") (pintype "bidirectional"))
    )
    (net (code "77") (name "GB7_RST") (class "Default")
      (node (ref "U2") (pin "G1") (pinfunction "IOL_13B_GBIN7_G1") (pintype "bidirectional"))
    )
    (net (code "78") (name "GND") (class "Default")
      (node (ref "C10") (pin "2") (pinfunction "2_2") (pintype "passive"))
      (node (ref "C100") (pin "2") (pinfunction "2_2") (pintype "passive"))
      (node (ref "C101") (pin "2") (pinfunction "C_2") (pintype "passive"))
      (node (ref "C102") (pin "2") (pinfunction "2_2") (pintype "passive"))
      (node (ref "C103") (pin "2") (pinfunction "2_2") (pintype "passive"))
      (node (ref "C104") (pin "2") (pinfunction "2_2") (pintype "passive"))
      (node (ref "C105") (pin "C") (pinfunction "C_C") (pintype "passive"))
      (node (ref "C106") (pin "C") (pinfunction "C_C") (pintype "passive"))
      (node (ref "C107") (pin "2") (pinfunction "2_2") (pintype "passive"))
      (node (ref "C108") (pin "C") (pinfunction "C_C") (pintype "passive"))
      (node (ref "C109") (pin "2") (pinfunction "2_2") (pintype "passive"))
      (node (ref "C11") (pin "2") (pinfunction "2_2") (pintype "passive"))
      (node (ref "C110") (pin "2") (pinfunction "2_2") (pintype "passive"))
      (node (ref "C111") (pin "C") (pinfunction "C_C") (pintype "passive"))
      (node (ref "C12") (pin "2") (pinfunction "2_2") (pintype "passive"))
      (node (ref "C13") (pin "2") (pinfunction "2_2") (pintype "passive"))
      (node (ref "C15") (pin "2") (pinfunction "2_2") (pintype "passive"))
      (node (ref "C16") (pin "2") (pinfunction "2_2") (pintype "passive"))
      (node (ref "C17") (pin "2") (pinfunction "2_2") (pintype "passive"))
      (node (ref "C18") (pin "2") (pinfunction "2_2") (pintype "passive"))
      (node (ref "C19") (pin "2") (pinfunction "2_2") (pintype "passive"))
      (node (ref "C2") (pin "2") (pinfunction "2_2") (pintype "passive"))
      (node (ref "C21") (pin "1") (pinfunction "1_1") (pintype "passive"))
      (node (ref "C221") (pin "2") (pinfunction "2_2") (pintype "passive"))
      (node (ref "C222") (pin "2") (pinfunction "2_2") (pintype "passive"))
      (node (ref "C23") (pin "2") (pinfunction "2_2") (pintype "passive"))
      (node (ref "C24") (pin "2") (pinfunction "2_2") (pintype "passive"))
      (node (ref "C25") (pin "2") (pinfunction "2_2") (pintype "passive"))
      (node (ref "C3") (pin "2") (pinfunction "2_2") (pintype "passive"))
      (node (ref "C39") (pin "2") (pinfunction "2_2") (pintype "passive"))
      (node (ref "C4") (pin "2") (pinfunction "2_2") (pintype "passive"))
      (node (ref "C40") (pin "2") (pinfunction "C_2") (pintype "passive"))
      (node (ref "C41") (pin "2") (pinfunction "2_2") (pintype "passive"))
      (node (ref "C42") (pin "2") (pinfunction "2_2") (pintype "passive"))
      (node (ref "C43") (pin "2") (pinfunction "2_2") (pintype "passive"))
      (node (ref "C5") (pin "1") (pinfunction "1_1") (pintype "passive"))
      (node (ref "C6") (pin "C") (pinfunction "C_C") (pintype "passive"))
      (node (ref "C7") (pin "C") (pinfunction "C_C") (pintype "passive"))
      (node (ref "C71") (pin "2") (pinfunction "2_2") (pintype "passive"))
      (node (ref "C72") (pin "2") (pinfunction "2_2") (pintype "passive"))
      (node (ref "C73") (pin "1") (pinfunction "1_1") (pintype "passive"))
      (node (ref "C74") (pin "2") (pinfunction "2_2") (pintype "passive"))
      (node (ref "C76") (pin "2") (pinfunction "2_2") (pintype "passive"))
      (node (ref "C78") (pin "2") (pinfunction "2_2") (pintype "passive"))
      (node (ref "C79") (pin "2") (pinfunction "2_2") (pintype "passive"))
      (node (ref "C8") (pin "C") (pinfunction "C_C") (pintype "passive"))
      (node (ref "C85") (pin "2") (pinfunction "C_2") (pintype "passive"))
      (node (ref "C86") (pin "2") (pinfunction "C_2") (pintype "passive"))
      (node (ref "C87") (pin "2") (pinfunction "C_2") (pintype "passive"))
      (node (ref "C88") (pin "2") (pinfunction "C_2") (pintype "passive"))
      (node (ref "C89") (pin "2") (pinfunction "C_2") (pintype "passive"))
      (node (ref "C9") (pin "2") (pinfunction "2_2") (pintype "passive"))
      (node (ref "C90") (pin "2") (pinfunction "C_2") (pintype "passive"))
      (node (ref "C91") (pin "2") (pinfunction "C_2") (pintype "passive"))
      (node (ref "C92") (pin "2") (pinfunction "C_2") (pintype "passive"))
      (node (ref "C94") (pin "2") (pinfunction "C_2") (pintype "passive"))
      (node (ref "C95") (pin "2") (pinfunction "2_2") (pintype "passive"))
      (node (ref "C96") (pin "2") (pinfunction "C_2") (pintype "passive"))
      (node (ref "C98") (pin "2") (pinfunction "C_2") (pintype "passive"))
      (node (ref "C99") (pin "2") (pinfunction "C_2") (pintype "passive"))
      (node (ref "CON1") (pin "5") (pinfunction "GND_5") (pintype "passive"))
      (node (ref "CON1") (pin "6") (pinfunction "SGND_6") (pintype "passive"))
      (node (ref "CON1") (pin "7") (pinfunction "SGND_7") (pintype "passive"))
      (node (ref "CON1") (pin "8") (pinfunction "SGND_8") (pintype "passive"))
      (node (ref "CON1") (pin "9") (pinfunction "SGND_9") (pintype "passive"))
      (node (ref "J1") (pin "8") (pinfunction "C_GND_8") (pintype "passive"))
      (node (ref "J1") (pin "S1") (pinfunction "S1_S1") (pintype "passive"))
      (node (ref "J1") (pin "S2") (pinfunction "S2_S2") (pintype "passive"))
      (node (ref "J2") (pin "G") (pinfunction "G_G") (pintype "passive"))
      (node (ref "JP1") (pin "3") (pinfunction "3_3") (pintype "passive"))
      (node (ref "JP2") (pin "11") (pinfunction "10_11") (pintype "passive"))
      (node (ref "JP2") (pin "5") (pinfunction "9_5") (pintype "passive"))
      (node (ref "JP3") (pin "2") (pinfunction "2_2") (pintype "passive"))
      (node (ref "JP5") (pin "11") (pinfunction "10_11") (pintype "passive"))
      (node (ref "JP5") (pin "5") (pinfunction "9_5") (pintype "passive"))
      (node (ref "JP6") (pin "11") (pinfunction "10_11") (pintype "passive"))
      (node (ref "JP6") (pin "5") (pinfunction "9_5") (pintype "passive"))
      (node (ref "JP7") (pin "11") (pinfunction "10_11") (pintype "passive"))
      (node (ref "JP7") (pin "5") (pinfunction "9_5") (pintype "passive"))
      (node (ref "JP8") (pin "3") (pinfunction "3_3") (pintype "passive"))
      (node (ref "JP8") (pin "4") (pinfunction "4_4") (pintype "passive"))
      (node (ref "JP8") (pin "5") (pinfunction "5_5") (pintype "passive"))
      (node (ref "JP8") (pin "6") (pinfunction "6_6") (pintype "passive"))
      (node (ref "JP8") (pin "7") (pinfunction "7_7") (pintype "passive"))
      (node (ref "JP8") (pin "8") (pinfunction "8_8") (pintype "passive"))
      (node (ref "Q1") (pin "2") (pinfunction "S_2") (pintype "passive"))
      (node (ref "Q16") (pin "2") (pinfunction "S_2") (pintype "passive"))
      (node (ref "R1") (pin "2") (pinfunction "2_2") (pintype "passive"))
      (node (ref "R3") (pin "2") (pinfunction "2_2") (pintype "passive"))
      (node (ref "R35") (pin "1") (pinfunction "1_1") (pintype "passive"))
      (node (ref "R36") (pin "1") (pinfunction "1_1") (pintype "passive"))
      (node (ref "R4") (pin "2") (pinfunction "2_2") (pintype "passive"))
      (node (ref "R49") (pin "2") (pinfunction "2_2") (pintype "passive"))
      (node (ref "R5") (pin "2") (pinfunction "2_2") (pintype "passive"))
      (node (ref "R50") (pin "1") (pinfunction "1_1") (pintype "passive"))
      (node (ref "SW3") (pin "1") (pinfunction "1_1") (pintype "passive"))
      (node (ref "SW3") (pin "4") (pinfunction "4_4") (pintype "passive"))
      (node (ref "U1") (pin "GP") (pinfunction "GP_GP") (pintype "passive"))
      (node (ref "U10") (pin "4") (pinfunction "GND_4") (pintype "power_in"))
      (node (ref "U11") (pin "4") (pinfunction "GND_4") (pintype "power_in"))
      (node (ref "U12") (pin "GPAD") (pinfunction "GPAD_GPAD") (pintype "passive"))
      (node (ref "U13") (pin "2") (pinfunction "LRSEL_2") (pintype "passive"))
      (node (ref "U13") (pin "3") (pinfunction "GND_3") (pintype "passive"))
      (node (ref "U17") (pin "2") (pinfunction "GND_2") (pintype "passive"))
      (node (ref "U2") (pin "A12") (pinfunction "GND_A12") (pintype "power_in"))
      (node (ref "U2") (pin "A4") (pinfunction "GND_2_A4") (pintype "power_in"))
      (node (ref "U2") (pin "E15") (pinfunction "GND_2_E15") (pintype "power_in"))
      (node (ref "U2") (pin "E7") (pinfunction "GNDPLL1_E7") (pintype "power_in"))
      (node (ref "U2") (pin "G7") (pinfunction "GND_3_G7") (pintype "power_in"))
      (node (ref "U2") (pin "G8") (pinfunction "GND_4_G8") (pintype "power_in"))
      (node (ref "U2") (pin "G9") (pinfunction "GND_5_G9") (pintype "power_in"))
      (node (ref "U2") (pin "H7") (pinfunction "GND_6_H7") (pintype "power_in"))
      (node (ref "U2") (pin "H8") (pinfunction "GND_7_H8") (pintype "power_in"))
      (node (ref "U2") (pin "H9") (pinfunction "GND_8_H9") (pintype "power_in"))
      (node (ref "U2") (pin "J7") (pinfunction "GND_9_J7") (pintype "power_in"))
      (node (ref "U2") (pin "J8") (pinfunction "GND_10_J8") (pintype "power_in"))
      (node (ref "U2") (pin "J9") (pinfunction "GND_11_J9") (pintype "power_in"))
      (node (ref "U2") (pin "K2") (pinfunction "GND_K2") (pintype "power_in"))
      (node (ref "U2") (pin "K7") (pinfunction "GND_2_K7") (pintype "power_in"))
      (node (ref "U2") (pin "L15") (pinfunction "GND_3_L15") (pintype "power_in"))
      (node (ref "U2") (pin "N8") (pinfunction "GNDPLL0_N8") (pintype "power_in"))
      (node (ref "U2") (pin "R7") (pinfunction "GND_3_R7") (pintype "power_in"))
      (node (ref "U2") (pin "T12") (pinfunction "GND_T12") (pintype "power_in"))
      (node (ref "U2") (pin "T4") (pinfunction "GND_4_T4") (pintype "power_in"))
      (node (ref "U3") (pin "10") (pinfunction "PRE_10") (pintype "input"))
      (node (ref "U3") (pin "11") (pinfunction "CLK_11") (pintype "input"))
      (node (ref "U3") (pin "12") (pinfunction "D_12") (pintype "input"))
      (node (ref "U3") (pin "13") (pinfunction "CLR_13") (pintype "input"))
      (node (ref "U3") (pin "7") (pinfunction "GND_7") (pintype "power_in"))
      (node (ref "U4") (pin "1") (pinfunction "GROUND_1") (pintype "passive"))
      (node (ref "U5") (pin "3") (pinfunction "GND_3") (pintype "power_in"))
      (node (ref "U6") (pin "3") (pinfunction "GND_3") (pintype "power_in"))
      (node (ref "U7") (pin "8") (pinfunction "GND_8") (pintype "power_in"))
      (node (ref "U8") (pin "13") (pinfunction "GND_13") (pintype "power_in"))
      (node (ref "U8") (pin "3") (pinfunction "GND_3") (pintype "power_in"))
      (node (ref "U9") (pin "107") (pinfunction "VSS_107") (pintype "passive"))
      (node (ref "U9") (pin "120") (pinfunction "VSS_120") (pintype "passive"))
      (node (ref "U9") (pin "130") (pinfunction "VSS_130") (pintype "passive"))
      (node (ref "U9") (pin "138") (pinfunction "BOOT0/VPP_138") (pintype "passive"))
      (node (ref "U9") (pin "16") (pinfunction "VSS_16") (pintype "passive"))
      (node (ref "U9") (pin "31") (pinfunction "VSSA_31") (pintype "passive"))
      (node (ref "U9") (pin "38") (pinfunction "VSS_38") (pintype "passive"))
      (node (ref "U9") (pin "51") (pinfunction "VSS_51") (pintype "passive"))
      (node (ref "U9") (pin "61") (pinfunction "VSS_61") (pintype "passive"))
      (node (ref "U9") (pin "83") (pinfunction "VSS_83") (pintype "passive"))
      (node (ref "U9") (pin "94") (pinfunction "VSS_94") (pintype "passive"))
      (node (ref "X1") (pin "GND") (pinfunction "GND_GND") (pintype "passive"))
      (node (ref "X3") (pin "GND@1") (pinfunction "1_GND@1") (pintype "passive"))
      (node (ref "X3") (pin "GND@2") (pinfunction "2_GND@2") (pintype "passive"))
      (node (ref "X5") (pin "GND") (pinfunction "GND_GND") (pintype "passive"))
      (node (ref "Z1") (pin "1") (pinfunction "GND_1") (pintype "passive"))
      (node (ref "Z2") (pin "1") (pinfunction "GND_1") (pintype "passive"))
      (node (ref "Z3") (pin "1") (pinfunction "GND_1") (pintype "passive"))
    )
    (net (code "79") (name "LED1") (class "Default")
      (node (ref "J1") (pin "A1") (pinfunction "A_A1") (pintype "passive"))
      (node (ref "U1") (pin "3") (pinfunction "LED1/REGOFF_3") (pintype "passive"))
    )
    (net (code "80") (name "LED2_~{INTSEL}") (class "Default")
      (node (ref "J1") (pin "A2") (pinfunction "A1_A2") (pintype "passive"))
      (node (ref "U1") (pin "2") (pinfunction "LED2/~{INTSEL}_2") (pintype "passive"))
    )
    (net (code "81") (name "LED_F1") (class "Default")
      (node (ref "R10") (pin "2") (pinfunction "2_2") (pintype "passive"))
      (node (ref "U2") (pin "A1") (pinfunction "IOT_220_A1") (pintype "bidirectional"))
    )
    (net (code "82") (name "LED_F2") (class "Default")
      (node (ref "R6") (pin "2") (pinfunction "2_2") (pintype "passive"))
      (node (ref "U2") (pin "A2") (pinfunction "IOT_218_A2") (pintype "bidirectional"))
    )
    (net (code "83") (name "LED_F3") (class "Default")
      (node (ref "R7") (pin "2") (pinfunction "2_2") (pintype "passive"))
      (node (ref "U2") (pin "A5") (pinfunction "IOT_213_A5") (pintype "bidirectional"))
    )
    (net (code "84") (name "LRCLK") (class "Default")
      (node (ref "R59") (pin "2") (pinfunction "2_2") (pintype "passive"))
      (node (ref "U2") (pin "T6") (pinfunction "IOB_73_T6") (pintype "bidirectional"))
    )
    (net (code "85") (name "MCLK") (class "Default")
      (node (ref "R60") (pin "2") (pinfunction "2_2") (pintype "passive"))
      (node (ref "U2") (pin "T5") (pinfunction "IOB_69_T5") (pintype "bidirectional"))
    )
    (net (code "86") (name "MCU_RX_UART3") (class "Default")
      (node (ref "U8") (pin "15") (pinfunction "TXD_15") (pintype "output"))
      (node (ref "U9") (pin "70") (pinfunction "PB11/I2C2_SDA/USART3_RX/OTG_HS_ULPI_D4/ETH_RMII_TX_EN/ETH_MII_TX_EN/TIM2_CH4/EVENTOUT_70") (pintype "passive"))
    )
    (net (code "87") (name "MCU_SPI3_MISO") (class "Default")
      (node (ref "R62") (pin "2") (pinfunction "2_2") (pintype "passive"))
      (node (ref "U10") (pin "2") (pinfunction "SO_2") (pintype "output"))
      (node (ref "U11") (pin "2") (pinfunction "SO_2") (pintype "output"))
      (node (ref "U2") (pin "N12") (pinfunction "IOB_98_N12") (pintype "bidirectional"))
      (node (ref "U9") (pin "112") (pinfunction "PC11/UART4_RX/SPI3_MISO/SDIO_D3/DCMI_D4/USART3_RX/I2S3EXT_SD/EVENTOUT_112") (pintype "passive"))
    )
    (net (code "88") (name "MCU_SPI3_MOSI") (class "Default")
      (node (ref "U10") (pin "5") (pinfunction "SI_5") (pintype "input"))
      (node (ref "U11") (pin "5") (pinfunction "SI_5") (pintype "input"))
      (node (ref "U2") (pin "P10") (pinfunction "IOB_86_P10") (pintype "bidirectional"))
      (node (ref "U2") (pin "P11") (pinfunction "IOB_106_SDI_P11") (pintype "bidirectional"))
      (node (ref "U9") (pin "113") (pinfunction "PC12/UART5_TX/SDIO_CK/DCMI_D9/SPI3_MOSI/I2S3_SD/USART3_CK/EVENTOUT_113") (pintype "passive"))
    )
    (net (code "89") (name "MCU_SPI3_SCLK") (class "Default")
      (node (ref "U10") (pin "6") (pinfunction "SCK_6") (pintype "input"))
      (node (ref "U11") (pin "6") (pinfunction "SCK_6") (pintype "input"))
      (node (ref "U2") (pin "R10") (pinfunction "IOB_84_R10") (pintype "bidirectional"))
      (node (ref "U2") (pin "R11") (pinfunction "IOB_107_SCK_R11") (pintype "bidirectional"))
      (node (ref "U9") (pin "111") (pinfunction "PC10/SPI3_SCK/I2S3_CK/UART4_TX/SDIO_D2/DCMI_D8/USART3_TX/EVENTOUT_111") (pintype "passive"))
    )
    (net (code "90") (name "MCU_TX_UART3") (class "Default")
      (node (ref "U8") (pin "2") (pinfunction "RXD_2") (pintype "input"))
      (node (ref "U9") (pin "69") (pinfunction "PB10/SPI2_SCK/I2S2_CK/I2C2_SCL/USART3_TX/OTG_HS_ULPI_D3/ETH_MII_RX_ER/TIM2_CH3/EVENTOUT_69") (pintype "passive"))
    )
    (net (code "91") (name "MIC_CLK") (class "Default")
      (node (ref "Q1") (pin "1") (pinfunction "G_1") (pintype "passive"))
      (node (ref "U2") (pin "C11") (pinfunction "IOT_180_C11") (pintype "bidirectional"))
    )
    (net (code "92") (name "MIC_DATA") (class "Default")
      (node (ref "Q16") (pin "3") (pinfunction "D_3") (pintype "passive"))
      (node (ref "R67") (pin "1") (pinfunction "1_1") (pintype "passive"))
      (node (ref "U2") (pin "C10") (pinfunction "IOT_185_C10") (pintype "bidirectional"))
    )
    (net (code "93") (name "Net-(C1-Pad2)") (class "Default")
      (node (ref "C1") (pin "2") (pinfunction "2_2") (pintype "passive"))
      (node (ref "C22") (pin "2") (pinfunction "2_2") (pintype "passive"))
      (node (ref "X1") (pin "OUTPUT") (pinfunction "OUTPUT_OUTPUT") (pintype "passive"))
    )
    (net (code "94") (name "Net-(C20-Pad2)") (class "Default")
      (node (ref "C20") (pin "2") (pinfunction "2_2") (pintype "passive"))
      (node (ref "X5") (pin "OUTPUT") (pinfunction "OUTPUT_OUTPUT") (pintype "passive"))
    )
    (net (code "95") (name "Net-(C40-A)") (class "Default")
      (node (ref "C40") (pin "1") (pinfunction "A_1") (pintype "passive"))
      (node (ref "L19") (pin "2") (pinfunction "2_2") (pintype "passive"))
      (node (ref "U9") (pin "33") (pinfunction "VDDA_33") (pintype "passive"))
    )
    (net (code "96") (name "Net-(C75-Pad1)") (class "Default")
      (node (ref "C75") (pin "1") (pinfunction "1_1") (pintype "passive"))
      (node (ref "R35") (pin "2") (pinfunction "2_2") (pintype "passive"))
      (node (ref "R37") (pin "2") (pinfunction "2_2") (pintype "passive"))
    )
    (net (code "97") (name "Net-(C77-Pad1)") (class "Default")
      (node (ref "C77") (pin "1") (pinfunction "1_1") (pintype "passive"))
      (node (ref "R36") (pin "2") (pinfunction "2_2") (pintype "passive"))
      (node (ref "R38") (pin "2") (pinfunction "2_2") (pintype "passive"))
    )
    (net (code "98") (name "Net-(C99-A)") (class "Default")
      (node (ref "C99") (pin "1") (pinfunction "A_1") (pintype "passive"))
      (node (ref "L1") (pin "2") (pinfunction "2_2") (pintype "passive"))
      (node (ref "U9") (pin "32") (pinfunction "VREF+_32") (pintype "passive"))
    )
    (net (code "99") (name "Net-(CON1-VBUS)") (class "Default")
      (node (ref "C105") (pin "A") (pinfunction "A_A") (pintype "passive"))
      (node (ref "CON1") (pin "1") (pinfunction "VBUS_1") (pintype "passive"))
      (node (ref "L21") (pin "2") (pinfunction "2_2") (pintype "passive"))
    )
    (net (code "100") (name "Net-(D1-PadC)") (class "Default")
      (node (ref "D1") (pin "C") (pinfunction "C_C") (pintype "passive"))
      (node (ref "R10") (pin "1") (pinfunction "1_1") (pintype "passive"))
    )
    (net (code "101") (name "Net-(D2-PadC)") (class "Default")
      (node (ref "D2") (pin "C") (pinfunction "C_C") (pintype "passive"))
      (node (ref "R6") (pin "1") (pinfunction "1_1") (pintype "passive"))
    )
    (net (code "102") (name "Net-(D3-PadC)") (class "Default")
      (node (ref "D3") (pin "C") (pinfunction "C_C") (pintype "passive"))
      (node (ref "R7") (pin "1") (pinfunction "1_1") (pintype "passive"))
    )
    (net (code "103") (name "Net-(D5-PadA)") (class "Default")
      (node (ref "D5") (pin "A") (pinfunction "A_A") (pintype "passive"))
      (node (ref "D6") (pin "A") (pinfunction "A_A") (pintype "passive"))
      (node (ref "D7") (pin "A") (pinfunction "A_A") (pintype "passive"))
      (node (ref "R61") (pin "2") (pinfunction "2_2") (pintype "passive"))
    )
    (net (code "104") (name "Net-(D8-PadC)") (class "Default")
      (node (ref "D8") (pin "C") (pinfunction "C_C") (pintype "passive"))
      (node (ref "D9") (pin "A") (pinfunction "A_A") (pintype "passive"))
    )
    (net (code "105") (name "Net-(J1-C)") (class "Default")
      (node (ref "J1") (pin "C1") (pinfunction "C_C1") (pintype "passive"))
      (node (ref "R4") (pin "1") (pinfunction "1_1") (pintype "passive"))
    )
    (net (code "106") (name "Net-(J1-C1)") (class "Default")
      (node (ref "J1") (pin "C2") (pinfunction "C1_C2") (pintype "passive"))
      (node (ref "R3") (pin "1") (pinfunction "1_1") (pintype "passive"))
    )
    (net (code "107") (name "Net-(J1-RCT)") (class "Default")
      (node (ref "C2") (pin "1") (pinfunction "1_1") (pintype "passive"))
      (node (ref "J1") (pin "2") (pinfunction "TCT_2") (pintype "passive"))
      (node (ref "J1") (pin "5") (pinfunction "RCT_5") (pintype "passive"))
      (node (ref "L6") (pin "2") (pinfunction "2_2") (pintype "passive"))
      (node (ref "R23") (pin "1") (pinfunction "1_1") (pintype "passive"))
      (node (ref "R24") (pin "1") (pinfunction "1_1") (pintype "passive"))
      (node (ref "R25") (pin "1") (pinfunction "1_1") (pintype "passive"))
      (node (ref "R26") (pin "1") (pinfunction "1_1") (pintype "passive"))
    )
    (net (code "108") (name "Net-(JP2-2)") (class "Default")
      (node (ref "JP2") (pin "7") (pinfunction "2_7") (pintype "passive"))
      (node (ref "R46") (pin "1") (pinfunction "1_1") (pintype "passive"))
    )
    (net (code "109") (name "Net-(JP2-3)") (class "Default")
      (node (ref "JP2") (pin "2") (pinfunction "3_2") (pintype "passive"))
      (node (ref "R43") (pin "2") (pinfunction "2_2") (pintype "passive"))
    )
    (net (code "110") (name "Net-(JP2-4)") (class "Default")
      (node (ref "JP2") (pin "8") (pinfunction "4_8") (pintype "passive"))
      (node (ref "R47") (pin "1") (pinfunction "1_1") (pintype "passive"))
    )
    (net (code "111") (name "Net-(JP2-5)") (class "Default")
      (node (ref "JP2") (pin "3") (pinfunction "5_3") (pintype "passive"))
      (node (ref "R44") (pin "2") (pinfunction "2_2") (pintype "passive"))
    )
    (net (code "112") (name "Net-(JP2-6)") (class "Default")
      (node (ref "JP2") (pin "9") (pinfunction "6_9") (pintype "passive"))
      (node (ref "R48") (pin "1") (pinfunction "1_1") (pintype "passive"))
    )
    (net (code "113") (name "Net-(JP2-7)") (class "Default")
      (node (ref "JP2") (pin "4") (pinfunction "7_4") (pintype "passive"))
      (node (ref "R45") (pin "2") (pinfunction "2_2") (pintype "passive"))
    )
    (net (code "114") (name "Net-(JP2-8)") (class "Default")
      (node (ref "JP2") (pin "10") (pinfunction "8_10") (pintype "passive"))
      (node (ref "R51") (pin "1") (pinfunction "1_1") (pintype "passive"))
    )
    (net (code "115") (name "Net-(JP2-Pad1)") (class "Default")
      (node (ref "JP2") (pin "1") (pinfunction "1_1") (pintype "passive"))
      (node (ref "R42") (pin "2") (pinfunction "2_2") (pintype "passive"))
    )
    (net (code "116") (name "Net-(JP5-2)") (class "Default")
      (node (ref "JP5") (pin "7") (pinfunction "2_7") (pintype "passive"))
      (node (ref "R14") (pin "1") (pinfunction "1_1") (pintype "passive"))
    )
    (net (code "117") (name "Net-(JP5-3)") (class "Default")
      (node (ref "JP5") (pin "2") (pinfunction "3_2") (pintype "passive"))
      (node (ref "R11") (pin "2") (pinfunction "2_2") (pintype "passive"))
    )
    (net (code "118") (name "Net-(JP5-4)") (class "Default")
      (node (ref "JP5") (pin "8") (pinfunction "4_8") (pintype "passive"))
      (node (ref "R15") (pin "1") (pinfunction "1_1") (pintype "passive"))
    )
    (net (code "119") (name "Net-(JP5-5)") (class "Default")
      (node (ref "JP5") (pin "3") (pinfunction "5_3") (pintype "passive"))
      (node (ref "R12") (pin "2") (pinfunction "2_2") (pintype "passive"))
    )
    (net (code "120") (name "Net-(JP5-6)") (class "Default")
      (node (ref "JP5") (pin "9") (pinfunction "6_9") (pintype "passive"))
      (node (ref "R16") (pin "1") (pinfunction "1_1") (pintype "passive"))
    )
    (net (code "121") (name "Net-(JP5-7)") (class "Default")
      (node (ref "JP5") (pin "4") (pinfunction "7_4") (pintype "passive"))
      (node (ref "R13") (pin "2") (pinfunction "2_2") (pintype "passive"))
    )
    (net (code "122") (name "Net-(JP5-8)") (class "Default")
      (node (ref "JP5") (pin "10") (pinfunction "8_10") (pintype "passive"))
      (node (ref "R17") (pin "1") (pinfunction "1_1") (pintype "passive"))
    )
    (net (code "123") (name "Net-(JP5-Pad1)") (class "Default")
      (node (ref "JP5") (pin "1") (pinfunction "1_1") (pintype "passive"))
      (node (ref "R9") (pin "2") (pinfunction "2_2") (pintype "passive"))
    )
    (net (code "124") (name "Net-(JP6-2)") (class "Default")
      (node (ref "JP6") (pin "7") (pinfunction "2_7") (pintype "passive"))
      (node (ref "R22") (pin "1") (pinfunction "1_1") (pintype "passive"))
    )
    (net (code "125") (name "Net-(JP6-3)") (class "Default")
      (node (ref "JP6") (pin "2") (pinfunction "3_2") (pintype "passive"))
      (node (ref "R19") (pin "2") (pinfunction "2_2") (pintype "passive"))
    )
    (net (code "126") (name "Net-(JP6-4)") (class "Default")
      (node (ref "JP6") (pin "8") (pinfunction "4_8") (pintype "passive"))
      (node (ref "R27") (pin "1") (pinfunction "1_1") (pintype "passive"))
    )
    (net (code "127") (name "Net-(JP6-5)") (class "Default")
      (node (ref "JP6") (pin "3") (pinfunction "5_3") (pintype "passive"))
      (node (ref "R20") (pin "2") (pinfunction "2_2") (pintype "passive"))
    )
    (net (code "128") (name "Net-(JP6-6)") (class "Default")
      (node (ref "JP6") (pin "9") (pinfunction "6_9") (pintype "passive"))
      (node (ref "R28") (pin "1") (pinfunction "1_1") (pintype "passive"))
    )
    (net (code "129") (name "Net-(JP6-7)") (class "Default")
      (node (ref "JP6") (pin "4") (pinfunction "7_4") (pintype "passive"))
      (node (ref "R21") (pin "2") (pinfunction "2_2") (pintype "passive"))
    )
    (net (code "130") (name "Net-(JP6-8)") (class "Default")
      (node (ref "JP6") (pin "10") (pinfunction "8_10") (pintype "passive"))
      (node (ref "R29") (pin "1") (pinfunction "1_1") (pintype "passive"))
    )
    (net (code "131") (name "Net-(JP6-Pad1)") (class "Default")
      (node (ref "JP6") (pin "1") (pinfunction "1_1") (pintype "passive"))
      (node (ref "R18") (pin "2") (pinfunction "2_2") (pintype "passive"))
    )
    (net (code "132") (name "Net-(JP7-2)") (class "Default")
      (node (ref "JP7") (pin "7") (pinfunction "2_7") (pintype "passive"))
      (node (ref "R34") (pin "1") (pinfunction "1_1") (pintype "passive"))
    )
    (net (code "133") (name "Net-(JP7-3)") (class "Default")
      (node (ref "JP7") (pin "2") (pinfunction "3_2") (pintype "passive"))
      (node (ref "R31") (pin "2") (pinfunction "2_2") (pintype "passive"))
    )
    (net (code "134") (name "Net-(JP7-4)") (class "Default")
      (node (ref "JP7") (pin "8") (pinfunction "4_8") (pintype "passive"))
      (node (ref "R39") (pin "1") (pinfunction "1_1") (pintype "passive"))
    )
    (net (code "135") (name "Net-(JP7-5)") (class "Default")
      (node (ref "JP7") (pin "3") (pinfunction "5_3") (pintype "passive"))
      (node (ref "R32") (pin "2") (pinfunction "2_2") (pintype "passive"))
    )
    (net (code "136") (name "Net-(JP7-6)") (class "Default")
      (node (ref "JP7") (pin "9") (pinfunction "6_9") (pintype "passive"))
      (node (ref "R40") (pin "1") (pinfunction "1_1") (pintype "passive"))
    )
    (net (code "137") (name "Net-(JP7-7)") (class "Default")
      (node (ref "JP7") (pin "4") (pinfunction "7_4") (pintype "passive"))
      (node (ref "R33") (pin "2") (pinfunction "2_2") (pintype "passive"))
    )
    (net (code "138") (name "Net-(JP7-8)") (class "Default")
      (node (ref "JP7") (pin "10") (pinfunction "8_10") (pintype "passive"))
      (node (ref "R41") (pin "1") (pinfunction "1_1") (pintype "passive"))
    )
    (net (code "139") (name "Net-(JP7-Pad1)") (class "Default")
      (node (ref "JP7") (pin "1") (pinfunction "1_1") (pintype "passive"))
      (node (ref "R30") (pin "2") (pinfunction "2_2") (pintype "passive"))
    )
    (net (code "140") (name "Net-(Q1-D)") (class "Default")
      (node (ref "Q1") (pin "3") (pinfunction "D_3") (pintype "passive"))
      (node (ref "R66") (pin "1") (pinfunction "1_1") (pintype "passive"))
      (node (ref "U13") (pin "4") (pinfunction "CLK_4") (pintype "passive"))
    )
    (net (code "141") (name "Net-(Q16-G)") (class "Default")
      (node (ref "Q16") (pin "1") (pinfunction "G_1") (pintype "passive"))
      (node (ref "U13") (pin "1") (pinfunction "DATA_1") (pintype "passive"))
    )
    (net (code "142") (name "Net-(R2-Pad2)") (class "Default")
      (node (ref "R2") (pin "2") (pinfunction "2_2") (pintype "passive"))
      (node (ref "R5") (pin "1") (pinfunction "1_1") (pintype "passive"))
      (node (ref "X5") (pin "VCC") (pinfunction "VCC_VCC") (pintype "passive"))
    )
    (net (code "143") (name "Net-(U1-RBIAS)") (class "Default")
      (node (ref "R1") (pin "1") (pinfunction "1_1") (pintype "passive"))
      (node (ref "U1") (pin "24") (pinfunction "RBIAS_24") (pintype "passive"))
    )
    (net (code "144") (name "Net-(U1-VDDCR)") (class "Default")
      (node (ref "C42") (pin "1") (pinfunction "1_1") (pintype "passive"))
      (node (ref "C43") (pin "1") (pinfunction "1_1") (pintype "passive"))
      (node (ref "U1") (pin "6") (pinfunction "VDDCR_6") (pintype "passive"))
    )
    (net (code "145") (name "Net-(U3A-CLK)") (class "Default")
      (node (ref "U3") (pin "3") (pinfunction "CLK_3") (pintype "input"))
      (node (ref "U6") (pin "4") (pinfunction "O_4") (pintype "output"))
    )
    (net (code "146") (name "Net-(U3A-D)") (class "Default")
      (node (ref "U3") (pin "2") (pinfunction "D_2") (pintype "input"))
      (node (ref "U3") (pin "6") (pinfunction "~{Q}_6") (pintype "output"))
    )
    (net (code "147") (name "Net-(U3A-Q)") (class "Default")
      (node (ref "C14") (pin "1") (pinfunction "1_1") (pintype "passive"))
      (node (ref "U3") (pin "5") (pinfunction "Q_5") (pintype "output"))
    )
    (net (code "148") (name "Net-(U5A-I)") (class "Default")
      (node (ref "C20") (pin "1") (pinfunction "1_1") (pintype "passive"))
      (node (ref "R49") (pin "1") (pinfunction "1_1") (pintype "passive"))
      (node (ref "R8") (pin "2") (pinfunction "2_2") (pintype "passive"))
      (node (ref "U5") (pin "2") (pinfunction "I_2") (pintype "input"))
      (node (ref "U6") (pin "2") (pinfunction "I_2") (pintype "input"))
    )
    (net (code "149") (name "Net-(U5A-O)") (class "Default")
      (node (ref "C113") (pin "2") (pinfunction "2_2") (pintype "passive"))
      (node (ref "U5") (pin "4") (pinfunction "O_4") (pintype "output"))
    )
    (net (code "150") (name "Net-(U7--DEM{slash}SCLK)") (class "Default")
      (node (ref "R58") (pin "1") (pinfunction "1_1") (pintype "passive"))
      (node (ref "U7") (pin "2") (pinfunction "-DEM/SCLK_2") (pintype "input"))
    )
    (net (code "151") (name "Net-(U7-AOUTL)") (class "Default")
      (node (ref "C75") (pin "2") (pinfunction "2_2") (pintype "passive"))
      (node (ref "U7") (pin "7") (pinfunction "AOUTL_7") (pintype "output"))
    )
    (net (code "152") (name "Net-(U7-AOUTR)") (class "Default")
      (node (ref "C77") (pin "2") (pinfunction "2_2") (pintype "passive"))
      (node (ref "U7") (pin "10") (pinfunction "AOUTR_10") (pintype "output"))
    )
    (net (code "153") (name "Net-(U7-FILT+)") (class "Default")
      (node (ref "C73") (pin "2") (pinfunction "2_2") (pintype "passive"))
      (node (ref "U7") (pin "6") (pinfunction "FILT+_6") (pintype "passive"))
    )
    (net (code "154") (name "Net-(U7-LRCLK)") (class "Default")
      (node (ref "R59") (pin "1") (pinfunction "1_1") (pintype "passive"))
      (node (ref "U7") (pin "3") (pinfunction "LRCLK_3") (pintype "input"))
    )
    (net (code "155") (name "Net-(U7-MCLK)") (class "Default")
      (node (ref "R60") (pin "1") (pinfunction "1_1") (pintype "passive"))
      (node (ref "U7") (pin "4") (pinfunction "MCLK_4") (pintype "input"))
    )
    (net (code "156") (name "Net-(U7-SDIN)") (class "Default")
      (node (ref "R57") (pin "1") (pinfunction "1_1") (pintype "passive"))
      (node (ref "U7") (pin "1") (pinfunction "SDIN_1") (pintype "input"))
    )
    (net (code "157") (name "Net-(U7-VA)") (class "Default")
      (node (ref "C74") (pin "1") (pinfunction "1_1") (pintype "passive"))
      (node (ref "L17") (pin "1") (pinfunction "1_1") (pintype "passive"))
      (node (ref "U7") (pin "9") (pinfunction "VA_9") (pintype "power_in"))
    )
    (net (code "158") (name "Net-(U7-VQ)") (class "Default")
      (node (ref "C71") (pin "1") (pinfunction "1_1") (pintype "passive"))
      (node (ref "C72") (pin "1") (pinfunction "1_1") (pintype "passive"))
      (node (ref "U7") (pin "5") (pinfunction "VQ_5") (pintype "passive"))
    )
    (net (code "159") (name "Net-(U8-3V3OUT)") (class "Default")
      (node (ref "C24") (pin "1") (pinfunction "1_1") (pintype "passive"))
      (node (ref "U8") (pin "1") (pinfunction "VCCIO_1") (pintype "power_in"))
      (node (ref "U8") (pin "8") (pinfunction "3V3OUT_8") (pintype "output"))
      (node (ref "U8") (pin "9") (pinfunction "~{RESET}_9") (pintype "input"))
    )
    (net (code "160") (name "Net-(U8-USBDM)") (class "Default")
      (node (ref "R64") (pin "1") (pinfunction "1_1") (pintype "passive"))
      (node (ref "U8") (pin "7") (pinfunction "USBDM_7") (pintype "input"))
    )
    (net (code "161") (name "Net-(U8-USBDP)") (class "Default")
      (node (ref "R65") (pin "2") (pinfunction "2_2") (pintype "passive"))
      (node (ref "U8") (pin "6") (pinfunction "USBDP_6") (pintype "input"))
    )
    (net (code "162") (name "Net-(U9B-PE2{slash}TRACECLK{slash}FSMC_A23{slash}ETH_MII_TXD3{slash}EVENTOUT)") (class "Default")
      (node (ref "D7") (pin "C") (pinfunction "C_C") (pintype "passive"))
      (node (ref "U9") (pin "1") (pinfunction "PE2/TRACECLK/FSMC_A23/ETH_MII_TXD3/EVENTOUT_1") (pintype "passive"))
    )
    (net (code "163") (name "Net-(U9B-PE3{slash}TRACED0{slash}FSMC_A19{slash}EVENTOUT)") (class "Default")
      (node (ref "D6") (pin "C") (pinfunction "C_C") (pintype "passive"))
      (node (ref "U9") (pin "2") (pinfunction "PE3/TRACED0/FSMC_A19/EVENTOUT_2") (pintype "passive"))
    )
    (net (code "164") (name "Net-(U9B-PE4{slash}TRACED1{slash}FSMC_A20{slash}DCMI_D4{slash}EVENTOUT)") (class "Default")
      (node (ref "D5") (pin "C") (pinfunction "C_C") (pintype "passive"))
      (node (ref "U9") (pin "3") (pinfunction "PE4/TRACED1/FSMC_A20/DCMI_D4/EVENTOUT_3") (pintype "passive"))
    )
    (net (code "165") (name "Net-(U9C-PH1-OSC_OUT{slash}EVENTOUT)") (class "Default")
      (node (ref "C5") (pin "2") (pinfunction "2_2") (pintype "passive"))
      (node (ref "U9") (pin "24") (pinfunction "PH1-OSC_OUT/EVENTOUT_24") (pintype "passive"))
      (node (ref "X3") (pin "3") (pinfunction "P$2_3") (pintype "passive"))
    )
    (net (code "166") (name "Net-(U9C-VCAP_1)") (class "Default")
      (node (ref "C100") (pin "1") (pinfunction "1_1") (pintype "passive"))
      (node (ref "U9") (pin "71") (pinfunction "VCAP_1_71") (pintype "passive"))
    )
    (net (code "167") (name "Net-(U9C-VCAP_2)") (class "Default")
      (node (ref "C102") (pin "1") (pinfunction "1_1") (pintype "passive"))
      (node (ref "U9") (pin "106") (pinfunction "VCAP_2_106") (pintype "passive"))
    )
    (net (code "168") (name "Net-(U12-BYP)") (class "Default")
      (node (ref "C107") (pin "1") (pinfunction "1_1") (pintype "passive"))
      (node (ref "U12") (pin "3") (pinfunction "BYP_3") (pintype "passive"))
    )
    (net (code "169") (name "Net-(U12-REF)") (class "Default")
      (node (ref "C109") (pin "1") (pinfunction "1_1") (pintype "passive"))
      (node (ref "U12") (pin "5") (pinfunction "REF_SENSE_5") (pintype "passive"))
      (node (ref "U12") (pin "6") (pinfunction "REF_6") (pintype "passive"))
    )
    (net (code "170") (name "Net-(U12-VOUT)") (class "Default")
      (node (ref "C106") (pin "A") (pinfunction "A_A") (pintype "passive"))
      (node (ref "L20") (pin "1") (pinfunction "1_1") (pintype "passive"))
      (node (ref "U12") (pin "1") (pinfunction "VOUT_1") (pintype "passive"))
      (node (ref "U12") (pin "2") (pinfunction "VOUT_SENSE_2") (pintype "passive"))
    )
    (net (code "171") (name "Net-(U12-VREG)") (class "Default")
      (node (ref "C110") (pin "1") (pinfunction "1_1") (pintype "passive"))
      (node (ref "U12") (pin "7") (pinfunction "VREG_7") (pintype "passive"))
    )
    (net (code "172") (name "Net-(U13-VDD)") (class "Default")
      (node (ref "C25") (pin "1") (pinfunction "1_1") (pintype "passive"))
      (node (ref "D9") (pin "C") (pinfunction "C_C") (pintype "passive"))
      (node (ref "R66") (pin "2") (pinfunction "2_2") (pintype "passive"))
      (node (ref "U13") (pin "5") (pinfunction "VDD_5") (pintype "passive"))
    )
    (net (code "173") (name "Net-(U17-EN)") (class "Default")
      (node (ref "C221") (pin "1") (pinfunction "1_1") (pintype "passive"))
      (node (ref "L2") (pin "2") (pinfunction "2_2") (pintype "passive"))
      (node (ref "U17") (pin "1") (pinfunction "IN_1") (pintype "passive"))
      (node (ref "U17") (pin "3") (pinfunction "EN_3") (pintype "passive"))
    )
    (net (code "174") (name "Net-(U17-NR)") (class "Default")
      (node (ref "C3") (pin "1") (pinfunction "1_1") (pintype "passive"))
      (node (ref "U17") (pin "4") (pinfunction "NR_4") (pintype "passive"))
    )
    (net (code "175") (name "Net-(U17-OUT)") (class "Default")
      (node (ref "C222") (pin "1") (pinfunction "1_1") (pintype "passive"))
      (node (ref "C4") (pin "1") (pinfunction "1_1") (pintype "passive"))
      (node (ref "R2") (pin "1") (pinfunction "1_1") (pintype "passive"))
      (node (ref "U17") (pin "5") (pinfunction "OUT_5") (pintype "passive"))
      (node (ref "X5") (pin "VDD") (pinfunction "VDD_VDD") (pintype "passive"))
    )
    (net (code "176") (name "PLL_VCC_1V2") (class "Default")
      (node (ref "C8") (pin "A") (pinfunction "A_A") (pintype "passive"))
      (node (ref "C9") (pin "1") (pinfunction "1_1") (pintype "passive"))
      (node (ref "R52") (pin "2") (pinfunction "2_2") (pintype "passive"))
      (node (ref "U2") (pin "E8") (pinfunction "VCCPLL1_E8") (pintype "power_in"))
      (node (ref "U2") (pin "L8") (pinfunction "VCCPLL0_L8") (pintype "power_in"))
    )
    (net (code "177") (name "PMOD1_1") (class "Default")
      (node (ref "R42") (pin "1") (pinfunction "1_1") (pintype "passive"))
      (node (ref "U2") (pin "P2") (pinfunction "IOL_25A_P2") (pintype "bidirectional"))
    )
    (net (code "178") (name "PMOD1_2") (class "Default")
      (node (ref "R43") (pin "1") (pinfunction "1_1") (pintype "passive"))
      (node (ref "U2") (pin "R2") (pinfunction "IOB_55_R2") (pintype "bidirectional"))
    )
    (net (code "179") (name "PMOD1_3") (class "Default")
      (node (ref "R44") (pin "1") (pinfunction "1_1") (pintype "passive"))
      (node (ref "U2") (pin "T1") (pinfunction "IOB_53_T1") (pintype "bidirectional"))
    )
    (net (code "180") (name "PMOD1_4") (class "Default")
      (node (ref "R45") (pin "1") (pinfunction "1_1") (pintype "passive"))
      (node (ref "U2") (pin "T3") (pinfunction "IOB_61_T3") (pintype "bidirectional"))
    )
    (net (code "181") (name "PMOD1_7") (class "Default")
      (node (ref "R46") (pin "2") (pinfunction "2_2") (pintype "passive"))
      (node (ref "U2") (pin "P1") (pinfunction "IOL_24A_P1") (pintype "bidirectional"))
    )
    (net (code "182") (name "PMOD1_8") (class "Default")
      (node (ref "R47") (pin "2") (pinfunction "2_2") (pintype "passive"))
      (node (ref "U2") (pin "R1") (pinfunction "IOL_26A_R1") (pintype "bidirectional"))
    )
    (net (code "183") (name "PMOD1_9") (class "Default")
      (node (ref "R48") (pin "2") (pinfunction "2_2") (pintype "passive"))
      (node (ref "U2") (pin "R3") (pinfunction "IOB_59_R3") (pintype "bidirectional"))
    )
    (net (code "184") (name "PMOD1_10") (class "Default")
      (node (ref "R51") (pin "2") (pinfunction "2_2") (pintype "passive"))
      (node (ref "U2") (pin "T2") (pinfunction "IOB_57_T2") (pintype "bidirectional"))
    )
    (net (code "185") (name "PMOD2_1") (class "Default")
      (node (ref "R30") (pin "1") (pinfunction "1_1") (pintype "passive"))
      (node (ref "U2") (pin "K1") (pinfunction "IOL_16A_K1") (pintype "bidirectional"))
    )
    (net (code "186") (name "PMOD2_2") (class "Default")
      (node (ref "R31") (pin "1") (pinfunction "1_1") (pintype "passive"))
      (node (ref "U2") (pin "L3") (pinfunction "IOL_19B_L3") (pintype "bidirectional"))
    )
    (net (code "187") (name "PMOD2_3") (class "Default")
      (node (ref "R32") (pin "1") (pinfunction "1_1") (pintype "passive"))
      (node (ref "U2") (pin "M2") (pinfunction "IOL_20B_M2") (pintype "bidirectional"))
    )
    (net (code "188") (name "PMOD2_4") (class "Default")
      (node (ref "R33") (pin "1") (pinfunction "1_1") (pintype "passive"))
      (node (ref "U2") (pin "N3") (pinfunction "IOL_23B_N3") (pintype "bidirectional"))
    )
    (net (code "189") (name "PMOD2_7") (class "Default")
      (node (ref "R34") (pin "2") (pinfunction "2_2") (pintype "passive"))
      (node (ref "U2") (pin "K3") (pinfunction "IOL_16B_K3") (pintype "bidirectional"))
    )
    (net (code "190") (name "PMOD2_8") (class "Default")
      (node (ref "R39") (pin "2") (pinfunction "2_2") (pintype "passive"))
      (node (ref "U2") (pin "L1") (pinfunction "IOL_17B_L1") (pintype "bidirectional"))
    )
    (net (code "191") (name "PMOD2_9") (class "Default")
      (node (ref "R40") (pin "2") (pinfunction "2_2") (pintype "passive"))
      (node (ref "U2") (pin "M1") (pinfunction "IOL_18B_M1") (pintype "bidirectional"))
    )
    (net (code "192") (name "PMOD2_10") (class "Default")
      (node (ref "R41") (pin "2") (pinfunction "2_2") (pintype "passive"))
      (node (ref "U2") (pin "N2") (pinfunction "IOL_21B_N2") (pintype "bidirectional"))
    )
    (net (code "193") (name "PMOD3_1") (class "Default")
      (node (ref "R18") (pin "1") (pinfunction "1_1") (pintype "passive"))
      (node (ref "U2") (pin "F2") (pinfunction "IOL_9B_F2") (pintype "bidirectional"))
    )
    (net (code "194") (name "PMOD3_2") (class "Default")
      (node (ref "R19") (pin "1") (pinfunction "1_1") (pintype "passive"))
      (node (ref "U2") (pin "G3") (pinfunction "IOL_8A_G3") (pintype "bidirectional"))
    )
    (net (code "195") (name "PMOD3_3") (class "Default")
      (node (ref "R20") (pin "1") (pinfunction "1_1") (pintype "passive"))
      (node (ref "U2") (pin "H1") (pinfunction "IOL_14B_H1") (pintype "bidirectional"))
    )
    (net (code "196") (name "PMOD3_4") (class "Default")
      (node (ref "R21") (pin "1") (pinfunction "1_1") (pintype "passive"))
      (node (ref "U2") (pin "J2") (pinfunction "IOL_15A_J2") (pintype "bidirectional"))
    )
    (net (code "197") (name "PMOD3_7") (class "Default")
      (node (ref "R22") (pin "2") (pinfunction "2_2") (pintype "passive"))
      (node (ref "U2") (pin "F1") (pinfunction "IOL_10B_F1") (pintype "bidirectional"))
    )
    (net (code "198") (name "PMOD3_8") (class "Default")
      (node (ref "R27") (pin "2") (pinfunction "2_2") (pintype "passive"))
      (node (ref "U2") (pin "G2") (pinfunction "IOL_11B_G2") (pintype "bidirectional"))
    )
    (net (code "199") (name "PMOD3_9") (class "Default")
      (node (ref "R28") (pin "2") (pinfunction "2_2") (pintype "passive"))
      (node (ref "U2") (pin "H2") (pinfunction "IOL_12B_H2") (pintype "bidirectional"))
    )
    (net (code "200") (name "PMOD3_10") (class "Default")
      (node (ref "R29") (pin "2") (pinfunction "2_2") (pintype "passive"))
      (node (ref "U2") (pin "J1") (pinfunction "IOL_15B_J1") (pintype "bidirectional"))
    )
    (net (code "201") (name "PMOD4_1") (class "Default")
      (node (ref "R9") (pin "1") (pinfunction "1_1") (pintype "passive"))
      (node (ref "U2") (pin "B3") (pinfunction "IOT_223_B3") (pintype "bidirectional"))
    )
    (net (code "202") (name "PMOD4_2") (class "Default")
      (node (ref "R11") (pin "1") (pinfunction "1_1") (pintype "passive"))
      (node (ref "U2") (pin "C3") (pinfunction "IOT_227_C3") (pintype "bidirectional"))
    )
    (net (code "203") (name "PMOD4_3") (class "Default")
      (node (ref "R12") (pin "1") (pinfunction "1_1") (pintype "passive"))
      (node (ref "U2") (pin "D3") (pinfunction "IOT_226_D3") (pintype "bidirectional"))
    )
    (net (code "204") (name "PMOD4_4") (class "Default")
      (node (ref "R13") (pin "1") (pinfunction "1_1") (pintype "passive"))
      (node (ref "U2") (pin "E3") (pinfunction "IOL_6B_E3") (pintype "bidirectional"))
    )
    (net (code "205") (name "PMOD4_7") (class "Default")
      (node (ref "R14") (pin "2") (pinfunction "2_2") (pintype "passive"))
      (node (ref "U2") (pin "B2") (pinfunction "IOL_1B_B2") (pintype "bidirectional"))
    )
    (net (code "206") (name "PMOD4_8") (class "Default")
      (node (ref "R15") (pin "2") (pinfunction "2_2") (pintype "passive"))
      (node (ref "U2") (pin "C2") (pinfunction "IOL_3B_C2") (pintype "bidirectional"))
    )
    (net (code "207") (name "PMOD4_9") (class "Default")
      (node (ref "R16") (pin "2") (pinfunction "2_2") (pintype "passive"))
      (node (ref "U2") (pin "D2") (pinfunction "IOL_4B_D2") (pintype "bidirectional"))
    )
    (net (code "208") (name "PMOD4_10") (class "Default")
      (node (ref "R17") (pin "2") (pinfunction "2_2") (pintype "passive"))
      (node (ref "U2") (pin "E2") (pinfunction "IOL_7B_E2") (pintype "bidirectional"))
    )
    (net (code "209") (name "P_A6") (class "Default")
      (node (ref "JP4") (pin "10") (pinfunction "10_10") (pintype "passive"))
      (node (ref "U2") (pin "A6") (pinfunction "IOT_211_A6") (pintype "bidirectional"))
    )
    (net (code "210") (name "P_A7") (class "Default")
      (node (ref "JP4") (pin "9") (pinfunction "9_9") (pintype "passive"))
      (node (ref "U2") (pin "A7") (pinfunction "IOT_205_A7") (pintype "bidirectional"))
    )
    (net (code "211") (name "P_A9") (class "Default")
      (node (ref "JP4") (pin "8") (pinfunction "8_8") (pintype "passive"))
      (node (ref "U2") (pin "A9") (pinfunction "IOT_194_A9") (pintype "bidirectional"))
    )
    (net (code "212") (name "P_A10") (class "Default")
      (node (ref "JP4") (pin "7") (pinfunction "7_7") (pintype "passive"))
      (node (ref "U2") (pin "A10") (pinfunction "IOT_186_A10") (pintype "bidirectional"))
    )
    (net (code "213") (name "P_A11") (class "Default")
      (node (ref "JP4") (pin "6") (pinfunction "6_6") (pintype "passive"))
      (node (ref "U2") (pin "A11") (pinfunction "IOT_187_A11") (pintype "bidirectional"))
    )
    (net (code "214") (name "P_B6") (class "Default")
      (node (ref "JP4") (pin "5") (pinfunction "5_5") (pintype "passive"))
      (node (ref "U2") (pin "B6") (pinfunction "IOT_208_B6") (pintype "bidirectional"))
    )
    (net (code "215") (name "P_B7") (class "Default")
      (node (ref "JP4") (pin "4") (pinfunction "4_4") (pintype "passive"))
      (node (ref "U2") (pin "B7") (pinfunction "IOT_207_B7") (pintype "bidirectional"))
    )
    (net (code "216") (name "P_B8") (class "Default")
      (node (ref "JP4") (pin "3") (pinfunction "3_3") (pintype "passive"))
      (node (ref "U2") (pin "B8") (pinfunction "IOT_203_B8") (pintype "bidirectional"))
    )
    (net (code "217") (name "P_B9") (class "Default")
      (node (ref "JP4") (pin "2") (pinfunction "2_2") (pintype "passive"))
      (node (ref "U2") (pin "B9") (pinfunction "IOT_199_B9") (pintype "bidirectional"))
    )
    (net (code "218") (name "P_B11") (class "Default")
      (node (ref "JP4") (pin "1") (pinfunction "1_1") (pintype "passive"))
      (node (ref "U2") (pin "B11") (pinfunction "IOT_184_B11") (pintype "bidirectional"))
    )
    (net (code "219") (name "REFCLK_PHY_50MHZ") (class "Default")
      (node (ref "C1") (pin "1") (pinfunction "1_1") (pintype "passive"))
      (node (ref "U1") (pin "5") (pinfunction "XTAL1/CLKIN_5") (pintype "passive"))
    )
    (net (code "220") (name "RMII_MDC") (class "Default")
      (node (ref "U1") (pin "13") (pinfunction "MDC_13") (pintype "passive"))
      (node (ref "U9") (pin "27") (pinfunction "PC1/ETH_MDC/EVENTOUT/ADC123_IN11_27") (pintype "passive"))
    )
    (net (code "221") (name "RMII_MDIO") (class "Default")
      (node (ref "R54") (pin "2") (pinfunction "2_2") (pintype "passive"))
      (node (ref "U1") (pin "12") (pinfunction "MDIO_12") (pintype "passive"))
      (node (ref "U9") (pin "36") (pinfunction "PA2/USART2_TX/TIM5_CH3/TIM9_CH1/TIM2_CH3/ETH_MDIO/EVENTOUT/ADC123_IN2_36") (pintype "passive"))
    )
    (net (code "222") (name "RMII_RXD_0") (class "Default")
      (node (ref "U1") (pin "8") (pinfunction "RXD0/MODE0_8") (pintype "passive"))
      (node (ref "U9") (pin "44") (pinfunction "PC4/ETH_RMII_RX_D0/ETH_MII_RX_D0/ADC12_IN14_44") (pintype "passive"))
    )
    (net (code "223") (name "RMII_RXD_1") (class "Default")
      (node (ref "U1") (pin "7") (pinfunction "RXD1/MODE1_7") (pintype "passive"))
      (node (ref "U9") (pin "45") (pinfunction "PC5/ETH_RMII_RX_D1/ETH_MII_RX_D1/EVENTOUT/ADC12_IN15_45") (pintype "passive"))
    )
    (net (code "224") (name "RMII_RX_DV") (class "Default")
      (node (ref "U1") (pin "11") (pinfunction "CRS_DV/MODE2_11") (pintype "passive"))
      (node (ref "U9") (pin "43") (pinfunction "PA7/SPI1_MOSI/TIM8_CH1N/TIM14_CH1/TIM3_CH2/ETH_MII_RX_DV/TIM1_CH1N/RMII_CRS_DV/EVENTOUT/ADC12_IN7_43") (pintype "passive"))
    )
    (net (code "225") (name "RMII_TXD_0") (class "Default")
      (node (ref "U1") (pin "17") (pinfunction "TXD0_17") (pintype "passive"))
      (node (ref "U9") (pin "128") (pinfunction "PG13/FSMC_A24/USART6_CTS/ETH_MII_TXD0/ETH_RMII_TXD0/EVENTOUT_128") (pintype "passive"))
    )
    (net (code "226") (name "RMII_TXD_1") (class "Default")
      (node (ref "U1") (pin "18") (pinfunction "TXD1_18") (pintype "passive"))
      (node (ref "U9") (pin "129") (pinfunction "PG14/FSMC_A25/USART6_TX/ETH_MII_TXD1/ETH_RMII_TXD1/EVENTOUT_129") (pintype "passive"))
    )
    (net (code "227") (name "RMII_TXD_EN") (class "Default")
      (node (ref "U1") (pin "16") (pinfunction "TXEN_16") (pintype "passive"))
      (node (ref "U9") (pin "126") (pinfunction "PG11/FSMC_NCE4_2/ETH_MII_TX_EN/ETH_RMII_TX_EN/EVENTOUT_126") (pintype "passive"))
    )
    (net (code "228") (name "RXER") (class "Default")
      (node (ref "R55") (pin "2") (pinfunction "2_2") (pintype "passive"))
      (node (ref "U1") (pin "10") (pinfunction "RXER/PHYAD0_10") (pintype "passive"))
    )
    (net (code "229") (name "SCLK") (class "Default")
      (node (ref "R58") (pin "2") (pinfunction "2_2") (pintype "passive"))
      (node (ref "U2") (pin "T7") (pinfunction "IOB_75_T7") (pintype "bidirectional"))
    )
    (net (code "230") (name "SDIN") (class "Default")
      (node (ref "R57") (pin "2") (pinfunction "2_2") (pintype "passive"))
      (node (ref "U2") (pin "T8") (pinfunction "IOB_76_T8") (pintype "bidirectional"))
    )
    (net (code "231") (name "SWCLK") (class "Default")
      (node (ref "JP1") (pin "2") (pinfunction "2_2") (pintype "passive"))
      (node (ref "U9") (pin "109") (pinfunction "PA14/JTCK-SWCLK/EVENTOUT_109") (pintype "passive"))
    )
    (net (code "232") (name "SWDIO") (class "Default")
      (node (ref "JP1") (pin "4") (pinfunction "4_4") (pintype "passive"))
      (node (ref "U9") (pin "105") (pinfunction "PA13/JTMS-SWDIO/EVENTOUT_105") (pintype "passive"))
    )
    (net (code "233") (name "SWO") (class "Default")
      (node (ref "JP1") (pin "6") (pinfunction "6_6") (pintype "passive"))
      (node (ref "U9") (pin "133") (pinfunction "PB3/JTDO/TRACESWO/SPI3_SCK/I2S3_CK/TIM2_CH2/SPI1_SCK/EVENTOUT_133") (pintype "passive"))
    )
    (net (code "234") (name "USB_DM") (class "Default")
      (node (ref "CON1") (pin "2") (pinfunction "DM_2") (pintype "passive"))
      (node (ref "R64") (pin "2") (pinfunction "2_2") (pintype "passive"))
    )
    (net (code "235") (name "USB_DP") (class "Default")
      (node (ref "CON1") (pin "3") (pinfunction "DP_3") (pintype "passive"))
      (node (ref "R65") (pin "1") (pinfunction "1_1") (pintype "passive"))
    )
    (net (code "236") (name "VPP_2V5") (class "Default")
      (node (ref "D4") (pin "C") (pinfunction "C_C") (pintype "passive"))
      (node (ref "U2") (pin "E12") (pinfunction "VPP_2V5_E12") (pintype "power_in"))
    )
    (net (code "237") (name "VPP_FAST") (class "Default")
      (node (ref "U2") (pin "D12") (pinfunction "VPP_FAST_D12") (pintype "power_in"))
    )
    (net (code "238") (name "unconnected-(CON1-ID-Pad4)") (class "Default")
      (node (ref "CON1") (pin "4") (pinfunction "ID_4") (pintype "passive"))
    )
    (net (code "239") (name "unconnected-(J1-NC-Pad7)") (class "Default")
      (node (ref "J1") (pin "7") (pinfunction "NC_7") (pintype "passive"))
    )
    (net (code "240") (name "unconnected-(JP1-Pad1)") (class "Default")
      (node (ref "JP1") (pin "1") (pinfunction "1_1") (pintype "passive"))
    )
    (net (code "241") (name "unconnected-(U1-XTAL2-Pad4)") (class "Default")
      (node (ref "U1") (pin "4") (pinfunction "XTAL2_4") (pintype "passive"))
    )
    (net (code "242") (name "unconnected-(U2A-IOL_1A-PadE4)") (class "Default")
      (node (ref "U2") (pin "E4") (pinfunction "IOL_1A_E4") (pintype "bidirectional"))
    )
    (net (code "243") (name "unconnected-(U2A-IOL_2A-PadF5)") (class "Default")
      (node (ref "U2") (pin "F5") (pinfunction "IOL_2A_F5") (pintype "bidirectional"))
    )
    (net (code "244") (name "unconnected-(U2A-IOL_2B-PadB1)") (class "Default")
      (node (ref "U2") (pin "B1") (pinfunction "IOL_2B_B1") (pintype "bidirectional"))
    )
    (net (code "245") (name "unconnected-(U2A-IOL_3A-PadC1)") (class "Default")
      (node (ref "U2") (pin "C1") (pinfunction "IOL_3A_C1") (pintype "bidirectional"))
    )
    (net (code "246") (name "unconnected-(U2A-IOL_4A-PadF4)") (class "Default")
      (node (ref "U2") (pin "F4") (pinfunction "IOL_4A_F4") (pintype "bidirectional"))
    )
    (net (code "247") (name "unconnected-(U2A-IOL_5A-PadG5)") (class "Default")
      (node (ref "U2") (pin "G5") (pinfunction "IOL_5A_G5") (pintype "bidirectional"))
    )
    (net (code "248") (name "unconnected-(U2A-IOL_5B-PadD1)") (class "Default")
      (node (ref "U2") (pin "D1") (pinfunction "IOL_5B_D1") (pintype "bidirectional"))
    )
    (net (code "249") (name "unconnected-(U2A-IOL_6A-PadG4)") (class "Default")
      (node (ref "U2") (pin "G4") (pinfunction "IOL_6A_G4") (pintype "bidirectional"))
    )
    (net (code "250") (name "unconnected-(U2A-IOL_7A-PadH5)") (class "Default")
      (node (ref "U2") (pin "H5") (pinfunction "IOL_7A_H5") (pintype "bidirectional"))
    )
    (net (code "251") (name "unconnected-(U2A-IOL_8B-PadF3)") (class "Default")
      (node (ref "U2") (pin "F3") (pinfunction "IOL_8B_F3") (pintype "bidirectional"))
    )
    (net (code "252") (name "unconnected-(U2A-IOL_9A-PadH3)") (class "Default")
      (node (ref "U2") (pin "H3") (pinfunction "IOL_9A_H3") (pintype "bidirectional"))
    )
    (net (code "253") (name "unconnected-(U2A-IOL_10A-PadH6)") (class "Default")
      (node (ref "U2") (pin "H6") (pinfunction "IOL_10A_H6") (pintype "bidirectional"))
    )
    (net (code "254") (name "unconnected-(U2A-IOL_11A-PadH4)") (class "Default")
      (node (ref "U2") (pin "H4") (pinfunction "IOL_11A_H4") (pintype "bidirectional"))
    )
    (net (code "255") (name "unconnected-(U2A-IOL_12A-PadJ4)") (class "Default")
      (node (ref "U2") (pin "J4") (pinfunction "IOL_12A_J4") (pintype "bidirectional"))
    )
    (net (code "256") (name "unconnected-(U2A-IOL_13A-PadJ5)") (class "Default")
      (node (ref "U2") (pin "J5") (pinfunction "IOL_13A_J5") (pintype "bidirectional"))
    )
    (net (code "257") (name "unconnected-(U2A-IOL_18A-PadK4)") (class "Default")
      (node (ref "U2") (pin "K4") (pinfunction "IOL_18A_K4") (pintype "bidirectional"))
    )
    (net (code "258") (name "unconnected-(U2A-IOL_20A-PadK5)") (class "Default")
      (node (ref "U2") (pin "K5") (pinfunction "IOL_20A_K5") (pintype "bidirectional"))
    )
    (net (code "259") (name "unconnected-(U2A-IOT_191-PadC9)") (class "Default")
      (node (ref "U2") (pin "C9") (pinfunction "IOT_191_C9") (pintype "bidirectional"))
    )
    (net (code "260") (name "unconnected-(U2A-IOT_192-PadE9)") (class "Default")
      (node (ref "U2") (pin "E9") (pinfunction "IOT_192_E9") (pintype "bidirectional"))
    )
    (net (code "261") (name "unconnected-(U2A-IOT_193-PadD9)") (class "Default")
      (node (ref "U2") (pin "D9") (pinfunction "IOT_193_D9") (pintype "bidirectional"))
    )
    (net (code "262") (name "unconnected-(U2A-IOT_196-PadF9)") (class "Default")
      (node (ref "U2") (pin "F9") (pinfunction "IOT_196_F9") (pintype "bidirectional"))
    )
    (net (code "263") (name "unconnected-(U2A-IOT_200-PadD8)") (class "Default")
      (node (ref "U2") (pin "D8") (pinfunction "IOT_200_D8") (pintype "bidirectional"))
    )
    (net (code "264") (name "unconnected-(U2A-IOT_206-PadC7)") (class "Default")
      (node (ref "U2") (pin "C7") (pinfunction "IOT_206_C7") (pintype "bidirectional"))
    )
    (net (code "265") (name "unconnected-(U2A-IOT_209-PadC6)") (class "Default")
      (node (ref "U2") (pin "C6") (pinfunction "IOT_209_C6") (pintype "bidirectional"))
    )
    (net (code "266") (name "unconnected-(U2A-IOT_210-PadD7)") (class "Default")
      (node (ref "U2") (pin "D7") (pinfunction "IOT_210_D7") (pintype "bidirectional"))
    )
    (net (code "267") (name "unconnected-(U2A-IOT_212-PadD6)") (class "Default")
      (node (ref "U2") (pin "D6") (pinfunction "IOT_212_D6") (pintype "bidirectional"))
    )
    (net (code "268") (name "unconnected-(U2A-IOT_214-PadB5)") (class "Default")
      (node (ref "U2") (pin "B5") (pinfunction "IOT_214_B5") (pintype "bidirectional"))
    )
    (net (code "269") (name "unconnected-(U2A-IOT_215-PadE6)") (class "Default")
      (node (ref "U2") (pin "E6") (pinfunction "IOT_215_E6") (pintype "bidirectional"))
    )
    (net (code "270") (name "unconnected-(U2A-IOT_216-PadB4)") (class "Default")
      (node (ref "U2") (pin "B4") (pinfunction "IOT_216_B4") (pintype "bidirectional"))
    )
    (net (code "271") (name "unconnected-(U2A-IOT_219-PadD5)") (class "Default")
      (node (ref "U2") (pin "D5") (pinfunction "IOT_219_D5") (pintype "bidirectional"))
    )
    (net (code "272") (name "unconnected-(U2A-IOT_221-PadC5)") (class "Default")
      (node (ref "U2") (pin "C5") (pinfunction "IOT_221_C5") (pintype "bidirectional"))
    )
    (net (code "273") (name "unconnected-(U2A-IOT_222-PadC4)") (class "Default")
      (node (ref "U2") (pin "C4") (pinfunction "IOT_222_C4") (pintype "bidirectional"))
    )
    (net (code "274") (name "unconnected-(U2A-IOT_224-PadD4)") (class "Default")
      (node (ref "U2") (pin "D4") (pinfunction "IOT_224_D4") (pintype "bidirectional"))
    )
    (net (code "275") (name "unconnected-(U2A-IOT_225-PadE5)") (class "Default")
      (node (ref "U2") (pin "E5") (pinfunction "IOT_225_E5") (pintype "bidirectional"))
    )
    (net (code "276") (name "unconnected-(U2B-IOB_52-PadN6)") (class "Default")
      (node (ref "U2") (pin "N6") (pinfunction "IOB_52_N6") (pintype "bidirectional"))
    )
    (net (code "277") (name "unconnected-(U2B-IOB_54-PadP4)") (class "Default")
      (node (ref "U2") (pin "P4") (pinfunction "IOB_54_P4") (pintype "bidirectional"))
    )
    (net (code "278") (name "unconnected-(U2B-IOB_56-PadN5)") (class "Default")
      (node (ref "U2") (pin "N5") (pinfunction "IOB_56_N5") (pintype "bidirectional"))
    )
    (net (code "279") (name "unconnected-(U2B-IOB_58-PadP5)") (class "Default")
      (node (ref "U2") (pin "P5") (pinfunction "IOB_58_P5") (pintype "bidirectional"))
    )
    (net (code "280") (name "unconnected-(U2B-IOB_60-PadR5)") (class "Default")
      (node (ref "U2") (pin "R5") (pinfunction "IOB_60_R5") (pintype "bidirectional"))
    )
    (net (code "281") (name "unconnected-(U2B-IOB_63-PadR4)") (class "Default")
      (node (ref "U2") (pin "R4") (pinfunction "IOB_63_R4") (pintype "bidirectional"))
    )
    (net (code "282") (name "unconnected-(U2B-IOB_64-PadM7)") (class "Default")
      (node (ref "U2") (pin "M7") (pinfunction "IOB_64_M7") (pintype "bidirectional"))
    )
    (net (code "283") (name "unconnected-(U2B-IOB_66-PadN7)") (class "Default")
      (node (ref "U2") (pin "N7") (pinfunction "IOB_66_N7") (pintype "bidirectional"))
    )
    (net (code "284") (name "unconnected-(U2B-IOB_67-PadP6)") (class "Default")
      (node (ref "U2") (pin "P6") (pinfunction "IOB_67_P6") (pintype "bidirectional"))
    )
    (net (code "285") (name "unconnected-(U2B-IOB_68-PadM8)") (class "Default")
      (node (ref "U2") (pin "M8") (pinfunction "IOB_68_M8") (pintype "bidirectional"))
    )
    (net (code "286") (name "unconnected-(U2B-IOB_71-PadR6)") (class "Default")
      (node (ref "U2") (pin "R6") (pinfunction "IOB_71_R6") (pintype "bidirectional"))
    )
    (net (code "287") (name "unconnected-(U2B-IOB_72-PadP8)") (class "Default")
      (node (ref "U2") (pin "P8") (pinfunction "IOB_72_P8") (pintype "bidirectional"))
    )
    (net (code "288") (name "unconnected-(U2B-IOB_74-PadL9)") (class "Default")
      (node (ref "U2") (pin "L9") (pinfunction "IOB_74_L9") (pintype "bidirectional"))
    )
    (net (code "289") (name "unconnected-(U2B-IOB_77-PadP7)") (class "Default")
      (node (ref "U2") (pin "P7") (pinfunction "IOB_77_P7") (pintype "bidirectional"))
    )
    (net (code "290") (name "unconnected-(U2B-IOB_78-PadN9)") (class "Default")
      (node (ref "U2") (pin "N9") (pinfunction "IOB_78_N9") (pintype "bidirectional"))
    )
    (net (code "291") (name "unconnected-(U2B-IOB_79-PadT9)") (class "Default")
      (node (ref "U2") (pin "T9") (pinfunction "IOB_79_T9") (pintype "bidirectional"))
    )
    (net (code "292") (name "unconnected-(U2B-IOB_80-PadM9)") (class "Default")
      (node (ref "U2") (pin "M9") (pinfunction "IOB_80_M9") (pintype "bidirectional"))
    )
    (net (code "293") (name "unconnected-(U2B-IOB_83-PadP9)") (class "Default")
      (node (ref "U2") (pin "P9") (pinfunction "IOB_83_P9") (pintype "bidirectional"))
    )
    (net (code "294") (name "unconnected-(U2B-IOL_17A-PadL4)") (class "Default")
      (node (ref "U2") (pin "L4") (pinfunction "IOL_17A_L4") (pintype "bidirectional"))
    )
    (net (code "295") (name "unconnected-(U2B-IOL_19A-PadL6)") (class "Default")
      (node (ref "U2") (pin "L6") (pinfunction "IOL_19A_L6") (pintype "bidirectional"))
    )
    (net (code "296") (name "unconnected-(U2B-IOL_21A-PadL7)") (class "Default")
      (node (ref "U2") (pin "L7") (pinfunction "IOL_21A_L7") (pintype "bidirectional"))
    )
    (net (code "297") (name "unconnected-(U2B-IOL_22A-PadM6)") (class "Default")
      (node (ref "U2") (pin "M6") (pinfunction "IOL_22A_M6") (pintype "bidirectional"))
    )
    (net (code "298") (name "unconnected-(U2B-IOL_22B-PadM3)") (class "Default")
      (node (ref "U2") (pin "M3") (pinfunction "IOL_22B_M3") (pintype "bidirectional"))
    )
    (net (code "299") (name "unconnected-(U2B-IOL_23A-PadL5)") (class "Default")
      (node (ref "U2") (pin "L5") (pinfunction "IOL_23A_L5") (pintype "bidirectional"))
    )
    (net (code "300") (name "unconnected-(U2B-IOL_24B-PadM4)") (class "Default")
      (node (ref "U2") (pin "M4") (pinfunction "IOL_24B_M4") (pintype "bidirectional"))
    )
    (net (code "301") (name "unconnected-(U2B-IOL_25B-PadM5)") (class "Default")
      (node (ref "U2") (pin "M5") (pinfunction "IOL_25B_M5") (pintype "bidirectional"))
    )
    (net (code "302") (name "unconnected-(U2B-IOL_26B-PadN4)") (class "Default")
      (node (ref "U2") (pin "N4") (pinfunction "IOL_26B_N4") (pintype "bidirectional"))
    )
    (net (code "303") (name "unconnected-(U2B-IOT_170-PadD13)") (class "Default")
      (node (ref "U2") (pin "D13") (pinfunction "IOT_170_D13") (pintype "bidirectional"))
    )
    (net (code "304") (name "unconnected-(U2B-IOT_172-PadC12)") (class "Default")
      (node (ref "U2") (pin "C12") (pinfunction "IOT_172_C12") (pintype "bidirectional"))
    )
    (net (code "305") (name "unconnected-(U2B-IOT_174-PadC13)") (class "Default")
      (node (ref "U2") (pin "C13") (pinfunction "IOT_174_C13") (pintype "bidirectional"))
    )
    (net (code "306") (name "unconnected-(U2B-IOT_178-PadB13)") (class "Default")
      (node (ref "U2") (pin "B13") (pinfunction "IOT_178_B13") (pintype "bidirectional"))
    )
    (net (code "307") (name "unconnected-(U2B-IOT_181-PadD11)") (class "Default")
      (node (ref "U2") (pin "D11") (pinfunction "IOT_181_D11") (pintype "bidirectional"))
    )
    (net (code "308") (name "unconnected-(U2B-IOT_182-PadB12)") (class "Default")
      (node (ref "U2") (pin "B12") (pinfunction "IOT_182_B12") (pintype "bidirectional"))
    )
    (net (code "309") (name "unconnected-(U2B-IOT_183-PadB10)") (class "Default")
      (node (ref "U2") (pin "B10") (pinfunction "IOT_183_B10") (pintype "bidirectional"))
    )
    (net (code "310") (name "unconnected-(U2B-IOT_190-PadD10)") (class "Default")
      (node (ref "U2") (pin "D10") (pinfunction "IOT_190_D10") (pintype "bidirectional"))
    )
    (net (code "311") (name "unconnected-(U2C-IOB_85-PadL10)") (class "Default")
      (node (ref "U2") (pin "L10") (pinfunction "IOB_85_L10") (pintype "bidirectional"))
    )
    (net (code "312") (name "unconnected-(U2C-IOB_87-PadN10)") (class "Default")
      (node (ref "U2") (pin "N10") (pinfunction "IOB_87_N10") (pintype "bidirectional"))
    )
    (net (code "313") (name "unconnected-(U2C-IOB_88-PadT10)") (class "Default")
      (node (ref "U2") (pin "T10") (pinfunction "IOB_88_T10") (pintype "bidirectional"))
    )
    (net (code "314") (name "unconnected-(U2C-IOB_89-PadT11)") (class "Default")
      (node (ref "U2") (pin "T11") (pinfunction "IOB_89_T11") (pintype "bidirectional"))
    )
    (net (code "315") (name "unconnected-(U2C-IOB_93-PadM11)") (class "Default")
      (node (ref "U2") (pin "M11") (pinfunction "IOB_93_M11") (pintype "bidirectional"))
    )
    (net (code "316") (name "unconnected-(U2C-IOB_99-PadL11)") (class "Default")
      (node (ref "U2") (pin "L11") (pinfunction "IOB_99_L11") (pintype "bidirectional"))
    )
    (net (code "317") (name "unconnected-(U2C-IOB_101-PadM12)") (class "Default")
      (node (ref "U2") (pin "M12") (pinfunction "IOB_101_M12") (pintype "bidirectional"))
    )
    (net (code "318") (name "unconnected-(U2C-IOB_103_CBSEL0-PadK11)") (class "Default")
      (node (ref "U2") (pin "K11") (pinfunction "IOB_103_CBSEL0_K11") (pintype "bidirectional"))
    )
    (net (code "319") (name "unconnected-(U2C-IOB_105_SDO-PadP12)") (class "Default")
      (node (ref "U2") (pin "P12") (pinfunction "IOB_105_SDO_P12") (pintype "bidirectional"))
    )
    (net (code "320") (name "unconnected-(U2C-IOR_114-PadM13)") (class "Default")
      (node (ref "U2") (pin "M13") (pinfunction "IOR_114_M13") (pintype "bidirectional"))
    )
    (net (code "321") (name "unconnected-(U2C-IOR_115-PadM14)") (class "Default")
      (node (ref "U2") (pin "M14") (pinfunction "IOR_115_M14") (pintype "bidirectional"))
    )
    (net (code "322") (name "unconnected-(U2C-IOR_116-PadL12)") (class "Default")
      (node (ref "U2") (pin "L12") (pinfunction "IOR_116_L12") (pintype "bidirectional"))
    )
    (net (code "323") (name "unconnected-(U2C-IOR_118-PadL13)") (class "Default")
      (node (ref "U2") (pin "L13") (pinfunction "IOR_118_L13") (pintype "bidirectional"))
    )
    (net (code "324") (name "unconnected-(U2C-IOR_120-PadK12)") (class "Default")
      (node (ref "U2") (pin "K12") (pinfunction "IOR_120_K12") (pintype "bidirectional"))
    )
    (net (code "325") (name "unconnected-(U2C-IOR_122-PadJ10)") (class "Default")
      (node (ref "U2") (pin "J10") (pinfunction "IOR_122_J10") (pintype "bidirectional"))
    )
    (net (code "326") (name "unconnected-(U2C-IOR_126-PadJ11)") (class "Default")
      (node (ref "U2") (pin "J11") (pinfunction "IOR_126_J11") (pintype "bidirectional"))
    )
    (net (code "327") (name "unconnected-(U2C-IOR_128-PadK13)") (class "Default")
      (node (ref "U2") (pin "K13") (pinfunction "IOR_128_K13") (pintype "bidirectional"))
    )
    (net (code "328") (name "unconnected-(U2C-IOR_136-PadJ12)") (class "Default")
      (node (ref "U2") (pin "J12") (pinfunction "IOR_136_J12") (pintype "bidirectional"))
    )
    (net (code "329") (name "unconnected-(U2C-IOR_137-PadJ13)") (class "Default")
      (node (ref "U2") (pin "J13") (pinfunction "IOR_137_J13") (pintype "bidirectional"))
    )
    (net (code "330") (name "unconnected-(U2C-IOR_139-PadH13)") (class "Default")
      (node (ref "U2") (pin "H13") (pinfunction "IOR_139_H13") (pintype "bidirectional"))
    )
    (net (code "331") (name "unconnected-(U2C-IOR_144-PadH12)") (class "Default")
      (node (ref "U2") (pin "H12") (pinfunction "IOR_144_H12") (pintype "bidirectional"))
    )
    (net (code "332") (name "unconnected-(U2C-IOR_146-PadG10)") (class "Default")
      (node (ref "U2") (pin "G10") (pinfunction "IOR_146_G10") (pintype "bidirectional"))
    )
    (net (code "333") (name "unconnected-(U2C-IOR_148-PadG11)") (class "Default")
      (node (ref "U2") (pin "G11") (pinfunction "IOR_148_G11") (pintype "bidirectional"))
    )
    (net (code "334") (name "unconnected-(U2C-IOR_152-PadG13)") (class "Default")
      (node (ref "U2") (pin "G13") (pinfunction "IOR_152_G13") (pintype "bidirectional"))
    )
    (net (code "335") (name "unconnected-(U2C-IOR_154-PadG12)") (class "Default")
      (node (ref "U2") (pin "G12") (pinfunction "IOR_154_G12") (pintype "bidirectional"))
    )
    (net (code "336") (name "unconnected-(U2C-IOR_156-PadF12)") (class "Default")
      (node (ref "U2") (pin "F12") (pinfunction "IOR_156_F12") (pintype "bidirectional"))
    )
    (net (code "337") (name "unconnected-(U2C-IOR_158-PadF11)") (class "Default")
      (node (ref "U2") (pin "F11") (pinfunction "IOR_158_F11") (pintype "bidirectional"))
    )
    (net (code "338") (name "unconnected-(U2C-IOR_162-PadF13)") (class "Default")
      (node (ref "U2") (pin "F13") (pinfunction "IOR_162_F13") (pintype "bidirectional"))
    )
    (net (code "339") (name "unconnected-(U2C-IOR_166-PadE13)") (class "Default")
      (node (ref "U2") (pin "E13") (pinfunction "IOR_166_E13") (pintype "bidirectional"))
    )
    (net (code "340") (name "unconnected-(U2C-IOT_173-PadE11)") (class "Default")
      (node (ref "U2") (pin "E11") (pinfunction "IOT_173_E11") (pintype "bidirectional"))
    )
    (net (code "341") (name "unconnected-(U2C-IOT_179-PadE10)") (class "Default")
      (node (ref "U2") (pin "E10") (pinfunction "IOT_179_E10") (pintype "bidirectional"))
    )
    (net (code "342") (name "unconnected-(U2C-NC-PadN14)") (class "Default")
      (node (ref "U2") (pin "N14") (pinfunction "NC_N14") (pintype "no_connect"))
    )
    (net (code "343") (name "unconnected-(U3B-Q-Pad9)") (class "Default")
      (node (ref "U3") (pin "9") (pinfunction "Q_9") (pintype "output"))
    )
    (net (code "344") (name "unconnected-(U3B-~{Q}-Pad8)") (class "Default")
      (node (ref "U3") (pin "8") (pinfunction "~{Q}_8") (pintype "output"))
    )
    (net (code "345") (name "unconnected-(U8-CBUS0-Pad12)") (class "Default")
      (node (ref "U8") (pin "12") (pinfunction "CBUS0_12") (pintype "bidirectional"))
    )
    (net (code "346") (name "unconnected-(U8-CBUS1-Pad11)") (class "Default")
      (node (ref "U8") (pin "11") (pinfunction "CBUS1_11") (pintype "bidirectional"))
    )
    (net (code "347") (name "unconnected-(U8-CBUS2-Pad5)") (class "Default")
      (node (ref "U8") (pin "5") (pinfunction "CBUS2_5") (pintype "bidirectional"))
    )
    (net (code "348") (name "unconnected-(U8-CBUS3-Pad14)") (class "Default")
      (node (ref "U8") (pin "14") (pinfunction "CBUS3_14") (pintype "bidirectional"))
    )
    (net (code "349") (name "unconnected-(U8-~{CTS}-Pad4)") (class "Default")
      (node (ref "U8") (pin "4") (pinfunction "~{CTS}_4") (pintype "input"))
    )
    (net (code "350") (name "unconnected-(U8-~{RTS}-Pad16)") (class "Default")
      (node (ref "U8") (pin "16") (pinfunction "~{RTS}_16") (pintype "output"))
    )
    (net (code "351") (name "unconnected-(U9A-PA0-WKUP{slash}USART2_CTS{slash}UART4_TX{slash}ETH_MII_CRS{slash}TIM2_CH1_ETR{slash}TIM5_CH1{slash}TIM8_ETR{slash}EVENTOUT{slash}ADC123_IN0-Pad34)") (class "Default")
      (node (ref "U9") (pin "34") (pinfunction "PA0-WKUP/USART2_CTS/UART4_TX/ETH_MII_CRS/TIM2_CH1_ETR/TIM5_CH1/TIM8_ETR/EVENTOUT/ADC123_IN0_34") (pintype "passive"))
    )
    (net (code "352") (name "unconnected-(U9A-PA4{slash}SPI1_NSS{slash}SPI3_NSS{slash}USART2_CK{slash}DCMI_HSYNC{slash}OTG_HS_SOF{slash}I2S3_WS{slash}EVENTOUT{slash}ADC12_IN4{slash}DAC1_OUT-Pad40)") (class "Default")
      (node (ref "U9") (pin "40") (pinfunction "PA4/SPI1_NSS/SPI3_NSS/USART2_CK/DCMI_HSYNC/OTG_HS_SOF/I2S3_WS/EVENTOUT/ADC12_IN4/DAC1_OUT_40") (pintype "passive"))
    )
    (net (code "353") (name "unconnected-(U9A-PA5{slash}SPI1_SCK{slash}OTG_HS_ULPI_CK{slash}TIM2_CH1_ETR{slash}TIM8_CHIN{slash}EVENTOUT{slash}ADC12_IN5{slash}DAC2_OUT-Pad41)") (class "Default")
      (node (ref "U9") (pin "41") (pinfunction "PA5/SPI1_SCK/OTG_HS_ULPI_CK/TIM2_CH1_ETR/TIM8_CHIN/EVENTOUT/ADC12_IN5/DAC2_OUT_41") (pintype "passive"))
    )
    (net (code "354") (name "unconnected-(U9A-PA6{slash}SPI1_MISO{slash}TIM8_BKIN{slash}TIM13_CH1{slash}DCMI_PIXCLK{slash}TIM3_CH1{slash}TIM1_BKIN{slash}EVENTOUT{slash}ADC12_IN6-Pad42)") (class "Default")
      (node (ref "U9") (pin "42") (pinfunction "PA6/SPI1_MISO/TIM8_BKIN/TIM13_CH1/DCMI_PIXCLK/TIM3_CH1/TIM1_BKIN/EVENTOUT/ADC12_IN6_42") (pintype "passive"))
    )
    (net (code "355") (name "unconnected-(U9A-PA8{slash}MC01{slash}USART1_CK{slash}TIM1_CH1{slash}I2C3_SCL{slash}OTG_FS_SOF{slash}EVENTOUT-Pad100)") (class "Default")
      (node (ref "U9") (pin "100") (pinfunction "PA8/MC01/USART1_CK/TIM1_CH1/I2C3_SCL/OTG_FS_SOF/EVENTOUT_100") (pintype "passive"))
    )
    (net (code "356") (name "unconnected-(U9A-PA9{slash}USART1_TX{slash}TIM1_CH2{slash}I2C3_SMBA{slash}DCMI_D0{slash}EVENTOUT-Pad101)") (class "Default")
      (node (ref "U9") (pin "101") (pinfunction "PA9/USART1_TX/TIM1_CH2/I2C3_SMBA/DCMI_D0/EVENTOUT_101") (pintype "passive"))
    )
    (net (code "357") (name "unconnected-(U9A-PA10{slash}USART1_RX{slash}TIM1_CH{slash}OTG_FS_ID{slash}DCMI_D1{slash}EVENTOUT-Pad102)") (class "Default")
      (node (ref "U9") (pin "102") (pinfunction "PA10/USART1_RX/TIM1_CH/OTG_FS_ID/DCMI_D1/EVENTOUT_102") (pintype "passive"))
    )
    (net (code "358") (name "unconnected-(U9A-PA11{slash}USART1_CTS{slash}CAN1_RX{slash}TIM1_CH4{slash}OTG_FS_DM{slash}EVENTOUT-Pad103)") (class "Default")
      (node (ref "U9") (pin "103") (pinfunction "PA11/USART1_CTS/CAN1_RX/TIM1_CH4/OTG_FS_DM/EVENTOUT_103") (pintype "passive"))
    )
    (net (code "359") (name "unconnected-(U9A-PA12{slash}USART1_RTS{slash}CAN1_TX{slash}TIM1_ETR{slash}OTG_FS_DP{slash}EVENTOUT-Pad104)") (class "Default")
      (node (ref "U9") (pin "104") (pinfunction "PA12/USART1_RTS/CAN1_TX/TIM1_ETR/OTG_FS_DP/EVENTOUT_104") (pintype "passive"))
    )
    (net (code "360") (name "unconnected-(U9A-PA15{slash}JTDI{slash}SPI3_NSS{slash}I2S3_WS{slash}TIM2_CH1_ETR{slash}SPI1_NSS{slash}EVENTOUT-Pad110)") (class "Default")
      (node (ref "U9") (pin "110") (pinfunction "PA15/JTDI/SPI3_NSS/I2S3_WS/TIM2_CH1_ETR/SPI1_NSS/EVENTOUT_110") (pintype "passive"))
    )
    (net (code "361") (name "unconnected-(U9A-PB0{slash}TIM3_CH3{slash}TIM8_CH2N{slash}OTG_HS_ULPI_D1{slash}ETH_MII_RXD2{slash}TIM1_CH2N{slash}EVENTOUT{slash}ADC12_IN8-Pad46)") (class "Default")
      (node (ref "U9") (pin "46") (pinfunction "PB0/TIM3_CH3/TIM8_CH2N/OTG_HS_ULPI_D1/ETH_MII_RXD2/TIM1_CH2N/EVENTOUT/ADC12_IN8_46") (pintype "passive"))
    )
    (net (code "362") (name "unconnected-(U9A-PB1{slash}TIM3_CH4{slash}TIM8_CH3N{slash}OTG_HS_ULPI_D2{slash}ETH_MII_RXD3{slash}TIM1_CH3N{slash}EVENTOUT{slash}ADC12_IN9-Pad47)") (class "Default")
      (node (ref "U9") (pin "47") (pinfunction "PB1/TIM3_CH4/TIM8_CH3N/OTG_HS_ULPI_D2/ETH_MII_RXD3/TIM1_CH3N/EVENTOUT/ADC12_IN9_47") (pintype "passive"))
    )
    (net (code "363") (name "unconnected-(U9A-PB2-BOOT1{slash}EVENTOUT-Pad48)") (class "Default")
      (node (ref "U9") (pin "48") (pinfunction "PB2-BOOT1/EVENTOUT_48") (pintype "passive"))
    )
    (net (code "364") (name "unconnected-(U9A-PB4{slash}NJTRST{slash}SPI3_MISO{slash}TIM3_CH1{slash}SPI1_MISO{slash}I2S3EXT_SD{slash}EVENTOUT-Pad134)") (class "Default")
      (node (ref "U9") (pin "134") (pinfunction "PB4/NJTRST/SPI3_MISO/TIM3_CH1/SPI1_MISO/I2S3EXT_SD/EVENTOUT_134") (pintype "passive"))
    )
    (net (code "365") (name "unconnected-(U9A-PB5{slash}I2C1_SMBA{slash}CAN2_RX{slash}OTG_HS_ULPI_D7{slash}ETH_PPS_OUT{slash}TIM3_CH2{slash}SPI1_MOSI{slash}SPI3_MOSI{slash}DCMI_D10{slash}I2S3_SD{slash}EVENTOUT-Pad135)") (class "Default")
      (node (ref "U9") (pin "135") (pinfunction "PB5/I2C1_SMBA/CAN2_RX/OTG_HS_ULPI_D7/ETH_PPS_OUT/TIM3_CH2/SPI1_MOSI/SPI3_MOSI/DCMI_D10/I2S3_SD/EVENTOUT_135") (pintype "passive"))
    )
    (net (code "366") (name "unconnected-(U9A-PB6{slash}I2C1_SCL{slash}TIM4_CH1{slash}CAN2_TX{slash}DCMI_D5{slash}USART1_TX{slash}EVENTOUT-Pad136)") (class "Default")
      (node (ref "U9") (pin "136") (pinfunction "PB6/I2C1_SCL/TIM4_CH1/CAN2_TX/DCMI_D5/USART1_TX/EVENTOUT_136") (pintype "passive"))
    )
    (net (code "367") (name "unconnected-(U9A-PB8{slash}TIM4_CH3{slash}SDIO_D4{slash}TIM10_CH1{slash}DCMI_D6{slash}ETH_MII_TXD3{slash}I2C1_SCL{slash}CAN1_RX{slash}EVENTOUT-Pad139)") (class "Default")
      (node (ref "U9") (pin "139") (pinfunction "PB8/TIM4_CH3/SDIO_D4/TIM10_CH1/DCMI_D6/ETH_MII_TXD3/I2C1_SCL/CAN1_RX/EVENTOUT_139") (pintype "passive"))
    )
    (net (code "368") (name "unconnected-(U9A-PB9{slash}SPI2_NSS{slash}I2S2_WS{slash}TIM4_CH4{slash}TIM11_CH1{slash}SDIO_D5{slash}DCMI_D7{slash}I2C1_SDA{slash}CAN1_TX{slash}EVENTOUT-Pad140)") (class "Default")
      (node (ref "U9") (pin "140") (pinfunction "PB9/SPI2_NSS/I2S2_WS/TIM4_CH4/TIM11_CH1/SDIO_D5/DCMI_D7/I2C1_SDA/CAN1_TX/EVENTOUT_140") (pintype "passive"))
    )
    (net (code "369") (name "unconnected-(U9A-PC0{slash}OTG_HS_ULPI_STP{slash}EVENTOUT{slash}ADC123_IN10-Pad26)") (class "Default")
      (node (ref "U9") (pin "26") (pinfunction "PC0/OTG_HS_ULPI_STP/EVENTOUT/ADC123_IN10_26") (pintype "passive"))
    )
    (net (code "370") (name "unconnected-(U9A-PC2{slash}SPI2_MISO{slash}OTG_HS_ULPI_DIR{slash}TH_MII_TXD2{slash}I2S2EXT_SD{slash}EVENTOUT{slash}ADC123_IN12-Pad28)") (class "Default")
      (node (ref "U9") (pin "28") (pinfunction "PC2/SPI2_MISO/OTG_HS_ULPI_DIR/TH_MII_TXD2/I2S2EXT_SD/EVENTOUT/ADC123_IN12_28") (pintype "passive"))
    )
    (net (code "371") (name "unconnected-(U9A-PC3{slash}SPI2_MOSI{slash}I2S2_SD{slash}OTG_HS_ULPI_NXT{slash}ETH_MII_TX_CLK{slash}EVENTOUT{slash}ADC123_IN13-Pad29)") (class "Default")
      (node (ref "U9") (pin "29") (pinfunction "PC3/SPI2_MOSI/I2S2_SD/OTG_HS_ULPI_NXT/ETH_MII_TX_CLK/EVENTOUT/ADC123_IN13_29") (pintype "passive"))
    )
    (net (code "372") (name "unconnected-(U9A-PC13_DNU_{slash}EVENTOUT{slash}RTC_AF2{slash}-Pad7)") (class "Default")
      (node (ref "U9") (pin "7") (pinfunction "PC13_DNU_/EVENTOUT/RTC_AF2/_7") (pintype "passive"))
    )
    (net (code "373") (name "unconnected-(U9A-PC14-OSC32_IN_DNU_{slash}EVENTOUT-Pad8)") (class "Default")
      (node (ref "U9") (pin "8") (pinfunction "PC14-OSC32_IN_DNU_/EVENTOUT_8") (pintype "passive"))
    )
    (net (code "374") (name "unconnected-(U9A-PC15-OSC32_OUT_DNU_{slash}EVENTOUT-Pad9)") (class "Default")
      (node (ref "U9") (pin "9") (pinfunction "PC15-OSC32_OUT_DNU_/EVENTOUT_9") (pintype "passive"))
    )
    (net (code "375") (name "unconnected-(U9B-PD2{slash}TIM3_ETR{slash}UART5_RX{slash}SDIO_CMD{slash}DCMI_D11{slash}EVENTOUT-Pad116)") (class "Default")
      (node (ref "U9") (pin "116") (pinfunction "PD2/TIM3_ETR/UART5_RX/SDIO_CMD/DCMI_D11/EVENTOUT_116") (pintype "passive"))
    )
    (net (code "376") (name "unconnected-(U9B-PD6{slash}FSMC_NWAIT{slash}USART2_RX{slash}EVENTOUT-Pad122)") (class "Default")
      (node (ref "U9") (pin "122") (pinfunction "PD6/FSMC_NWAIT/USART2_RX/EVENTOUT_122") (pintype "passive"))
    )
    (net (code "377") (name "unconnected-(U9B-PD11{slash}FSMC_CLE{slash}FSMC_A16{slash}USART3_CTS{slash}EVENTOUT-Pad80)") (class "Default")
      (node (ref "U9") (pin "80") (pinfunction "PD11/FSMC_CLE/FSMC_A16/USART3_CTS/EVENTOUT_80") (pintype "passive"))
    )
    (net (code "378") (name "unconnected-(U9B-PD12{slash}FSMC_ALE{slash}FSMC_A17{slash}TIM4_CH1{slash}USART3_RTS{slash}EVENTOUT-Pad81)") (class "Default")
      (node (ref "U9") (pin "81") (pinfunction "PD12/FSMC_ALE/FSMC_A17/TIM4_CH1/USART3_RTS/EVENTOUT_81") (pintype "passive"))
    )
    (net (code "379") (name "unconnected-(U9B-PD13{slash}FSMC_A18{slash}TIM4_CH2{slash}EVENTOUT-Pad82)") (class "Default")
      (node (ref "U9") (pin "82") (pinfunction "PD13/FSMC_A18/TIM4_CH2/EVENTOUT_82") (pintype "passive"))
    )
    (net (code "380") (name "unconnected-(U9B-PE0{slash}TIM4_ETR{slash}FSMC_NBLO{slash}DCMI_D2{slash}EVENTOUT-Pad141)") (class "Default")
      (node (ref "U9") (pin "141") (pinfunction "PE0/TIM4_ETR/FSMC_NBLO/DCMI_D2/EVENTOUT_141") (pintype "passive"))
    )
    (net (code "381") (name "unconnected-(U9B-PE1{slash}FSMC_NBL1{slash}DMI_D3{slash}EVENTOUT-Pad142)") (class "Default")
      (node (ref "U9") (pin "142") (pinfunction "PE1/FSMC_NBL1/DMI_D3/EVENTOUT_142") (pintype "passive"))
    )
    (net (code "382") (name "unconnected-(U9B-PE6{slash}TRACED3{slash}FSMC_A22{slash}TIM9_CH2{slash}DCMI_D7{slash}EVENTOUT-Pad5)") (class "Default")
      (node (ref "U9") (pin "5") (pinfunction "PE6/TRACED3/FSMC_A22/TIM9_CH2/DCMI_D7/EVENTOUT_5") (pintype "passive"))
    )
    (net (code "383") (name "unconnected-(U9B-PF6{slash}TIM10_CH1{slash}FSMC_NIORD{slash}EVENTOUT{slash}ADC3_IN4-Pad18)") (class "Default")
      (node (ref "U9") (pin "18") (pinfunction "PF6/TIM10_CH1/FSMC_NIORD/EVENTOUT/ADC3_IN4_18") (pintype "passive"))
    )
    (net (code "384") (name "unconnected-(U9B-PF7{slash}TIM11_CH1{slash}FSMC_NREG{slash}EVENTOUT{slash}ADC3_IN5-Pad19)") (class "Default")
      (node (ref "U9") (pin "19") (pinfunction "PF7/TIM11_CH1/FSMC_NREG/EVENTOUT/ADC3_IN5_19") (pintype "passive"))
    )
    (net (code "385") (name "unconnected-(U9B-PF8{slash}TIM13_CH1{slash}FSMC_NIOWR{slash}EVENTOUT{slash}ADC3_IN6-Pad20)") (class "Default")
      (node (ref "U9") (pin "20") (pinfunction "PF8/TIM13_CH1/FSMC_NIOWR/EVENTOUT/ADC3_IN6_20") (pintype "passive"))
    )
    (net (code "386") (name "unconnected-(U9B-PF9{slash}TIM14_CH1{slash}FSMC_CD{slash}EVENTOUT{slash}ADC3_IN7-Pad21)") (class "Default")
      (node (ref "U9") (pin "21") (pinfunction "PF9/TIM14_CH1/FSMC_CD/EVENTOUT/ADC3_IN7_21") (pintype "passive"))
    )
    (net (code "387") (name "unconnected-(U9B-PF10{slash}FSMC_INTR{slash}EVENTOUT{slash}ADC3_IN8-Pad22)") (class "Default")
      (node (ref "U9") (pin "22") (pinfunction "PF10/FSMC_INTR/EVENTOUT/ADC3_IN8_22") (pintype "passive"))
    )
    (net (code "388") (name "unconnected-(U9B-PF11{slash}DCMI_12{slash}EVENTOUT-Pad49)") (class "Default")
      (node (ref "U9") (pin "49") (pinfunction "PF11/DCMI_12/EVENTOUT_49") (pintype "passive"))
    )
    (net (code "389") (name "unconnected-(U9B-PG9{slash}USART6_RX{slash}FSMC_NE2{slash}FSMC_NCE3{slash}EVENTOUT-Pad124)") (class "Default")
      (node (ref "U9") (pin "124") (pinfunction "PG9/USART6_RX/FSMC_NE2/FSMC_NCE3/EVENTOUT_124") (pintype "passive"))
    )
    (net (code "390") (name "unconnected-(U9B-PG10{slash}FSMC_NCE4_1{slash}FSMC_NE3{slash}EVENTOUT-Pad125)") (class "Default")
      (node (ref "U9") (pin "125") (pinfunction "PG10/FSMC_NCE4_1/FSMC_NE3/EVENTOUT_125") (pintype "passive"))
    )
    (net (code "391") (name "unconnected-(U9B-PG15{slash}USART6_CTS{slash}DCMI_D13{slash}EVENTOUT-Pad132)") (class "Default")
      (node (ref "U9") (pin "132") (pinfunction "PG15/USART6_CTS/DCMI_D13/EVENTOUT_132") (pintype "passive"))
    )
    (net (code "392") (name "unconnected-(U9C-VBAT-Pad6)") (class "Default")
      (node (ref "U9") (pin "6") (pinfunction "VBAT_6") (pintype "passive"))
    )
    (net (code "393") (name "unconnected-(Z1-REF-Pad4)") (class "Default")
      (node (ref "Z1") (pin "4") (pinfunction "REF_4") (pintype "passive"))
    )
    (net (code "394") (name "unconnected-(Z2-REF-Pad4)") (class "Default")
      (node (ref "Z2") (pin "4") (pinfunction "REF_4") (pintype "passive"))
    )
    (net (code "395") (name "unconnected-(Z3-REF-Pad4)") (class "Default")
      (node (ref "Z3") (pin "4") (pinfunction "REF_4") (pintype "passive"))
    )
    (net (code "396") (name "~{ETH_INT}") (class "Default")
      (node (ref "R53") (pin "2") (pinfunction "2_2") (pintype "passive"))
      (node (ref "U1") (pin "14") (pinfunction "~{INT/REFCLK0}_14") (pintype "passive"))
      (node (ref "U9") (pin "37") (pinfunction "PA3/USART2_RX/TIM5_CH4/TIM9_CH2/TIM2_CH4/OTG_HS_ULPI_D0/ETH_MII_COL/EVENTOUT/ADC123_IN3_37") (pintype "passive"))
    )
    (net (code "397") (name "~{RESET}") (class "Default")
      (node (ref "JP1") (pin "5") (pinfunction "5_5") (pintype "passive"))
      (node (ref "R56") (pin "2") (pinfunction "2_2") (pintype "passive"))
      (node (ref "SW3") (pin "2") (pinfunction "2_2") (pintype "passive"))
      (node (ref "SW3") (pin "3") (pinfunction "3_3") (pintype "passive"))
      (node (ref "U1") (pin "15") (pinfunction "~{RST}_15") (pintype "passive"))
      (node (ref "U9") (pin "25") (pinfunction "NRST_25") (pintype "passive"))
      (node (ref "Z3") (pin "2") (pinfunction "I/O_2") (pintype "passive"))
      (node (ref "Z3") (pin "3") (pinfunction "I/O_3") (pintype "passive"))
    )
    (net (code "398") (name "~{RUN_BOOTL}") (class "Default")
      (node (ref "JP3") (pin "1") (pinfunction "1_1") (pintype "passive"))
      (node (ref "R63") (pin "2") (pinfunction "2_2") (pintype "passive"))
      (node (ref "U9") (pin "4") (pinfunction "PE5/TRACED2/FSMC_A21/TIM9_CH1/DCMI_D6/EVENTOUT_4") (pintype "passive"))
    )
  )
)
